# 96_Parallelism_Yamaichi_Rev1_2.net
KiCad netlist of a schematic drawn in EAGLE
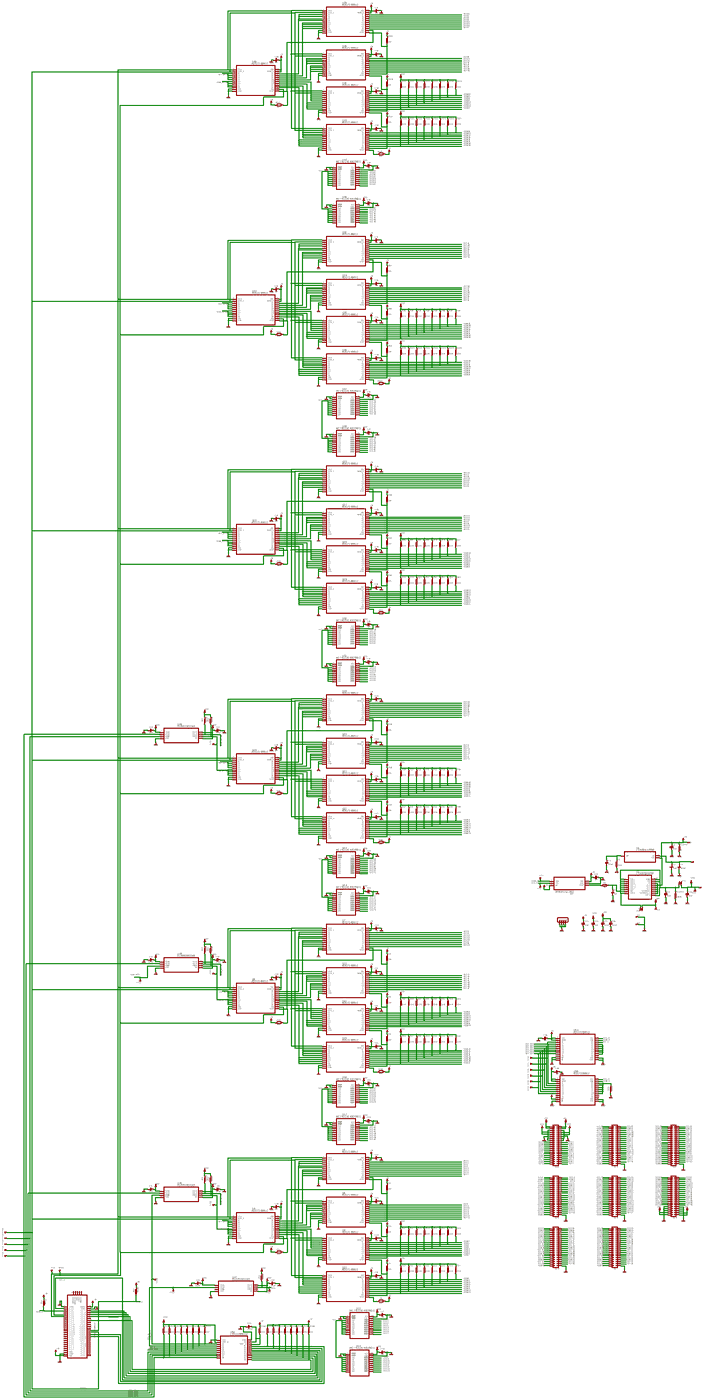
[diagram p0: schematic, sheet 1, overview]
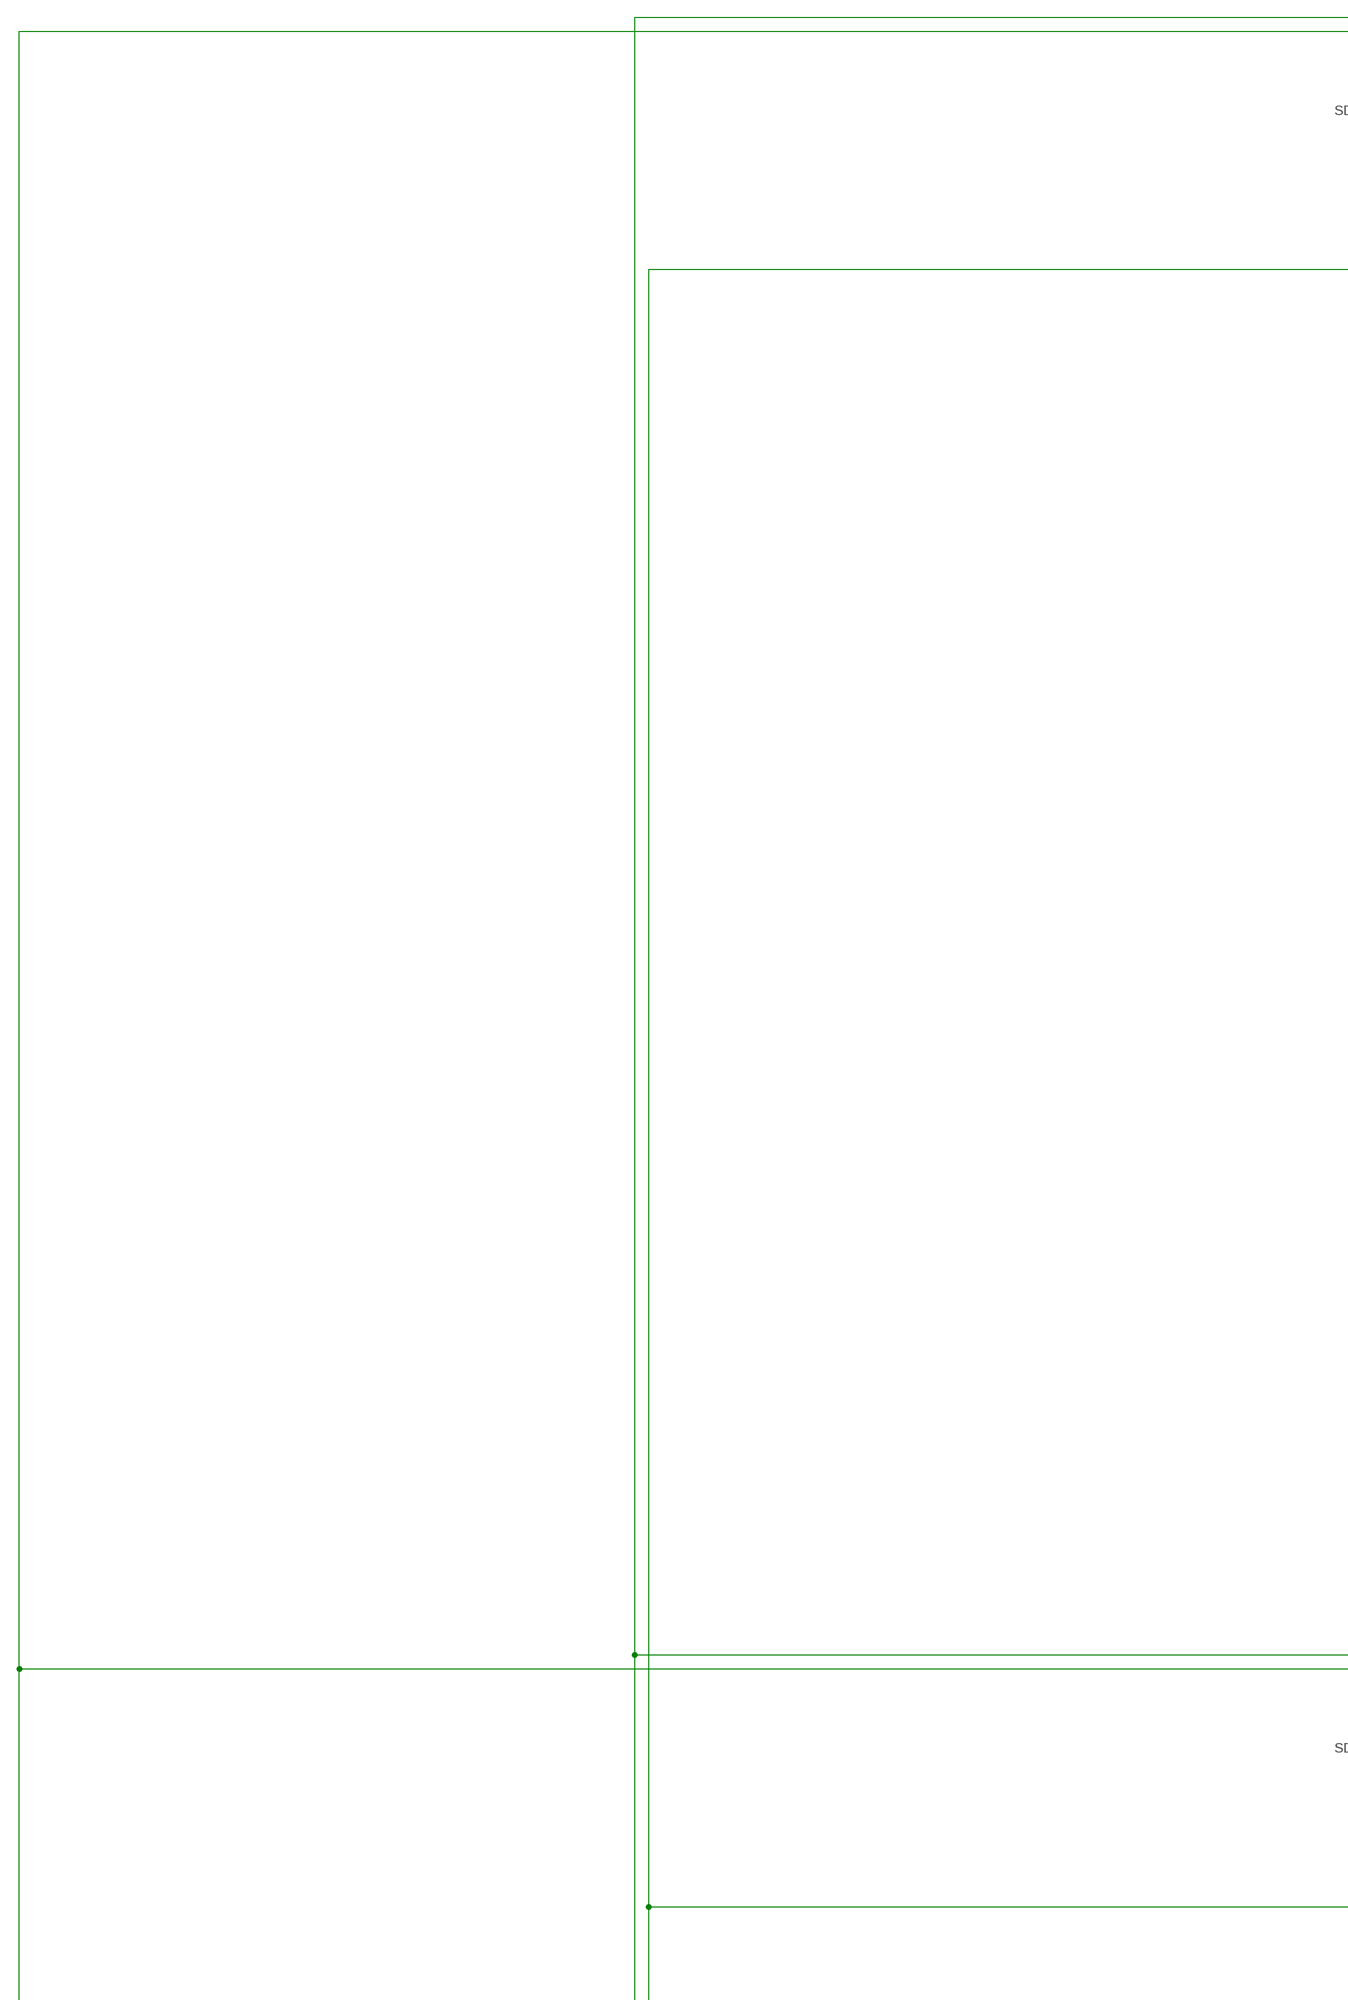
[diagram p1: schematic, sheet 1, part 1 of 8]
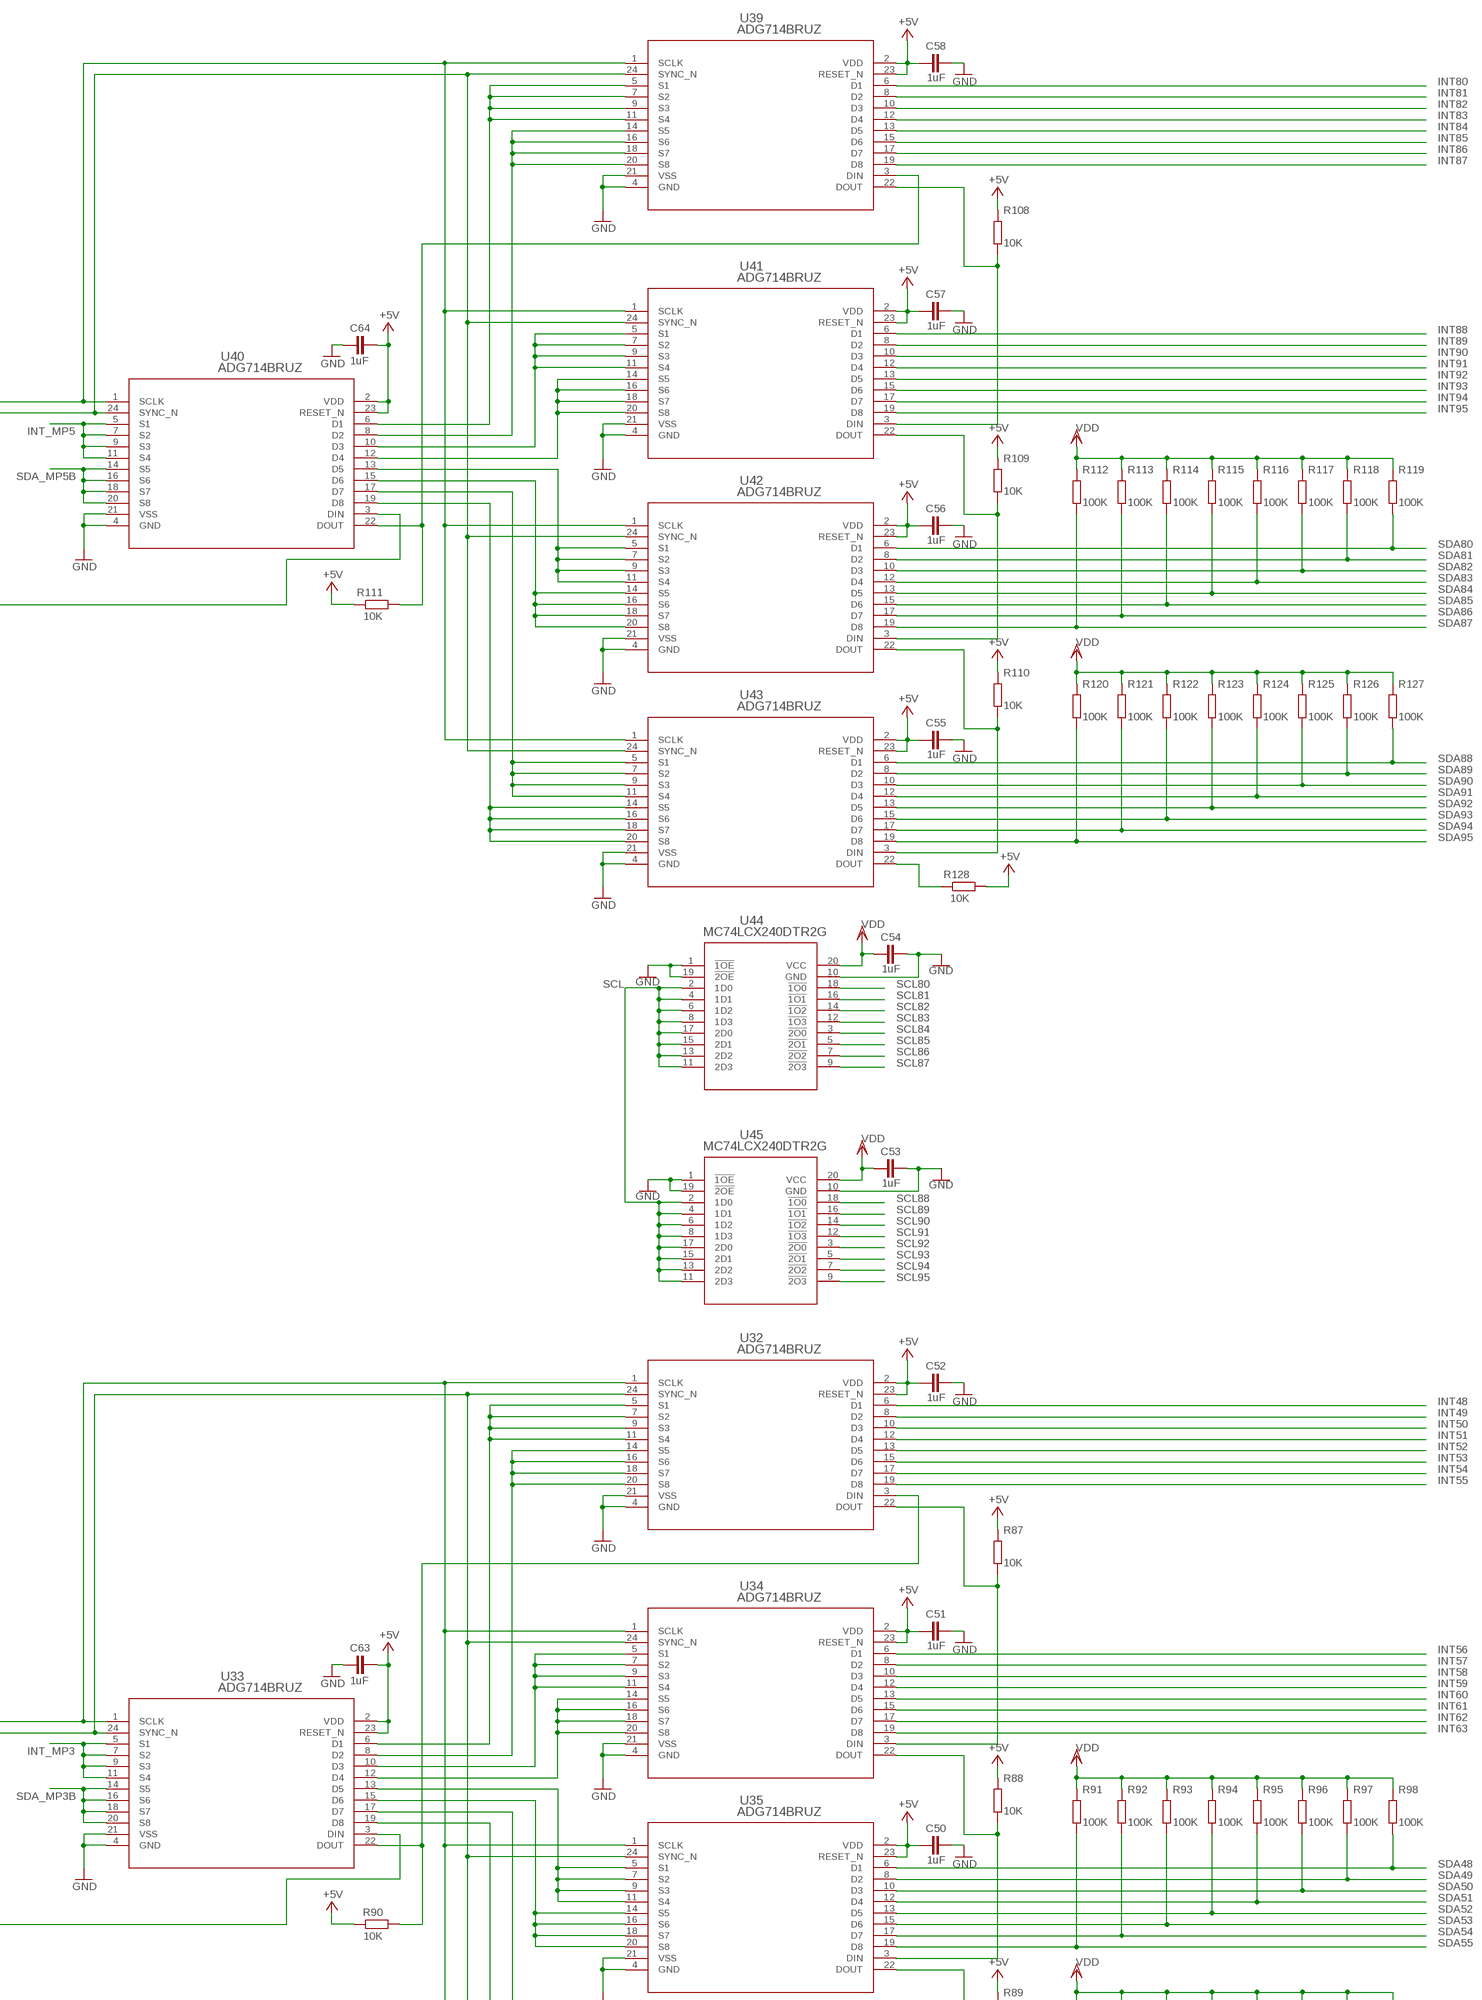
[diagram p2: schematic, sheet 1, part 2 of 8]
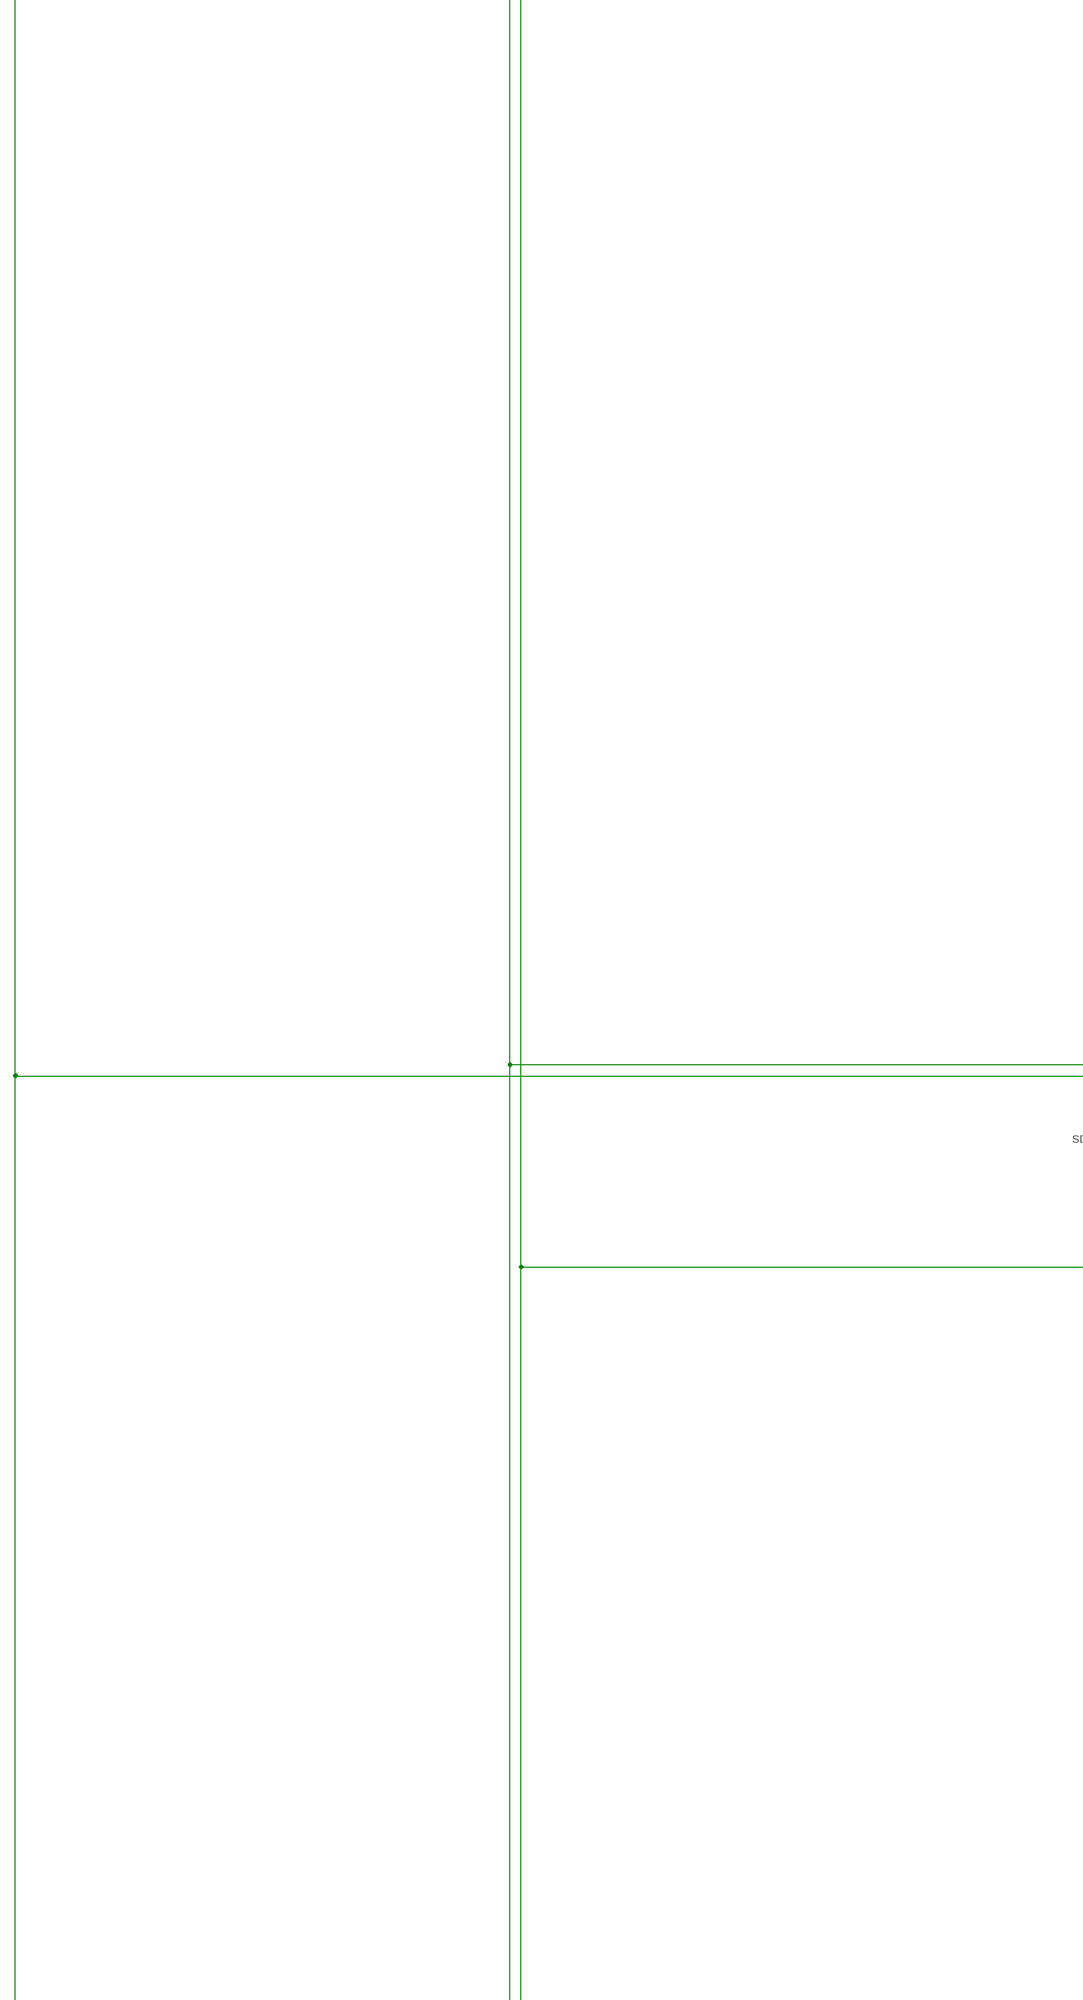
[diagram p3: schematic, sheet 1, part 3 of 8]
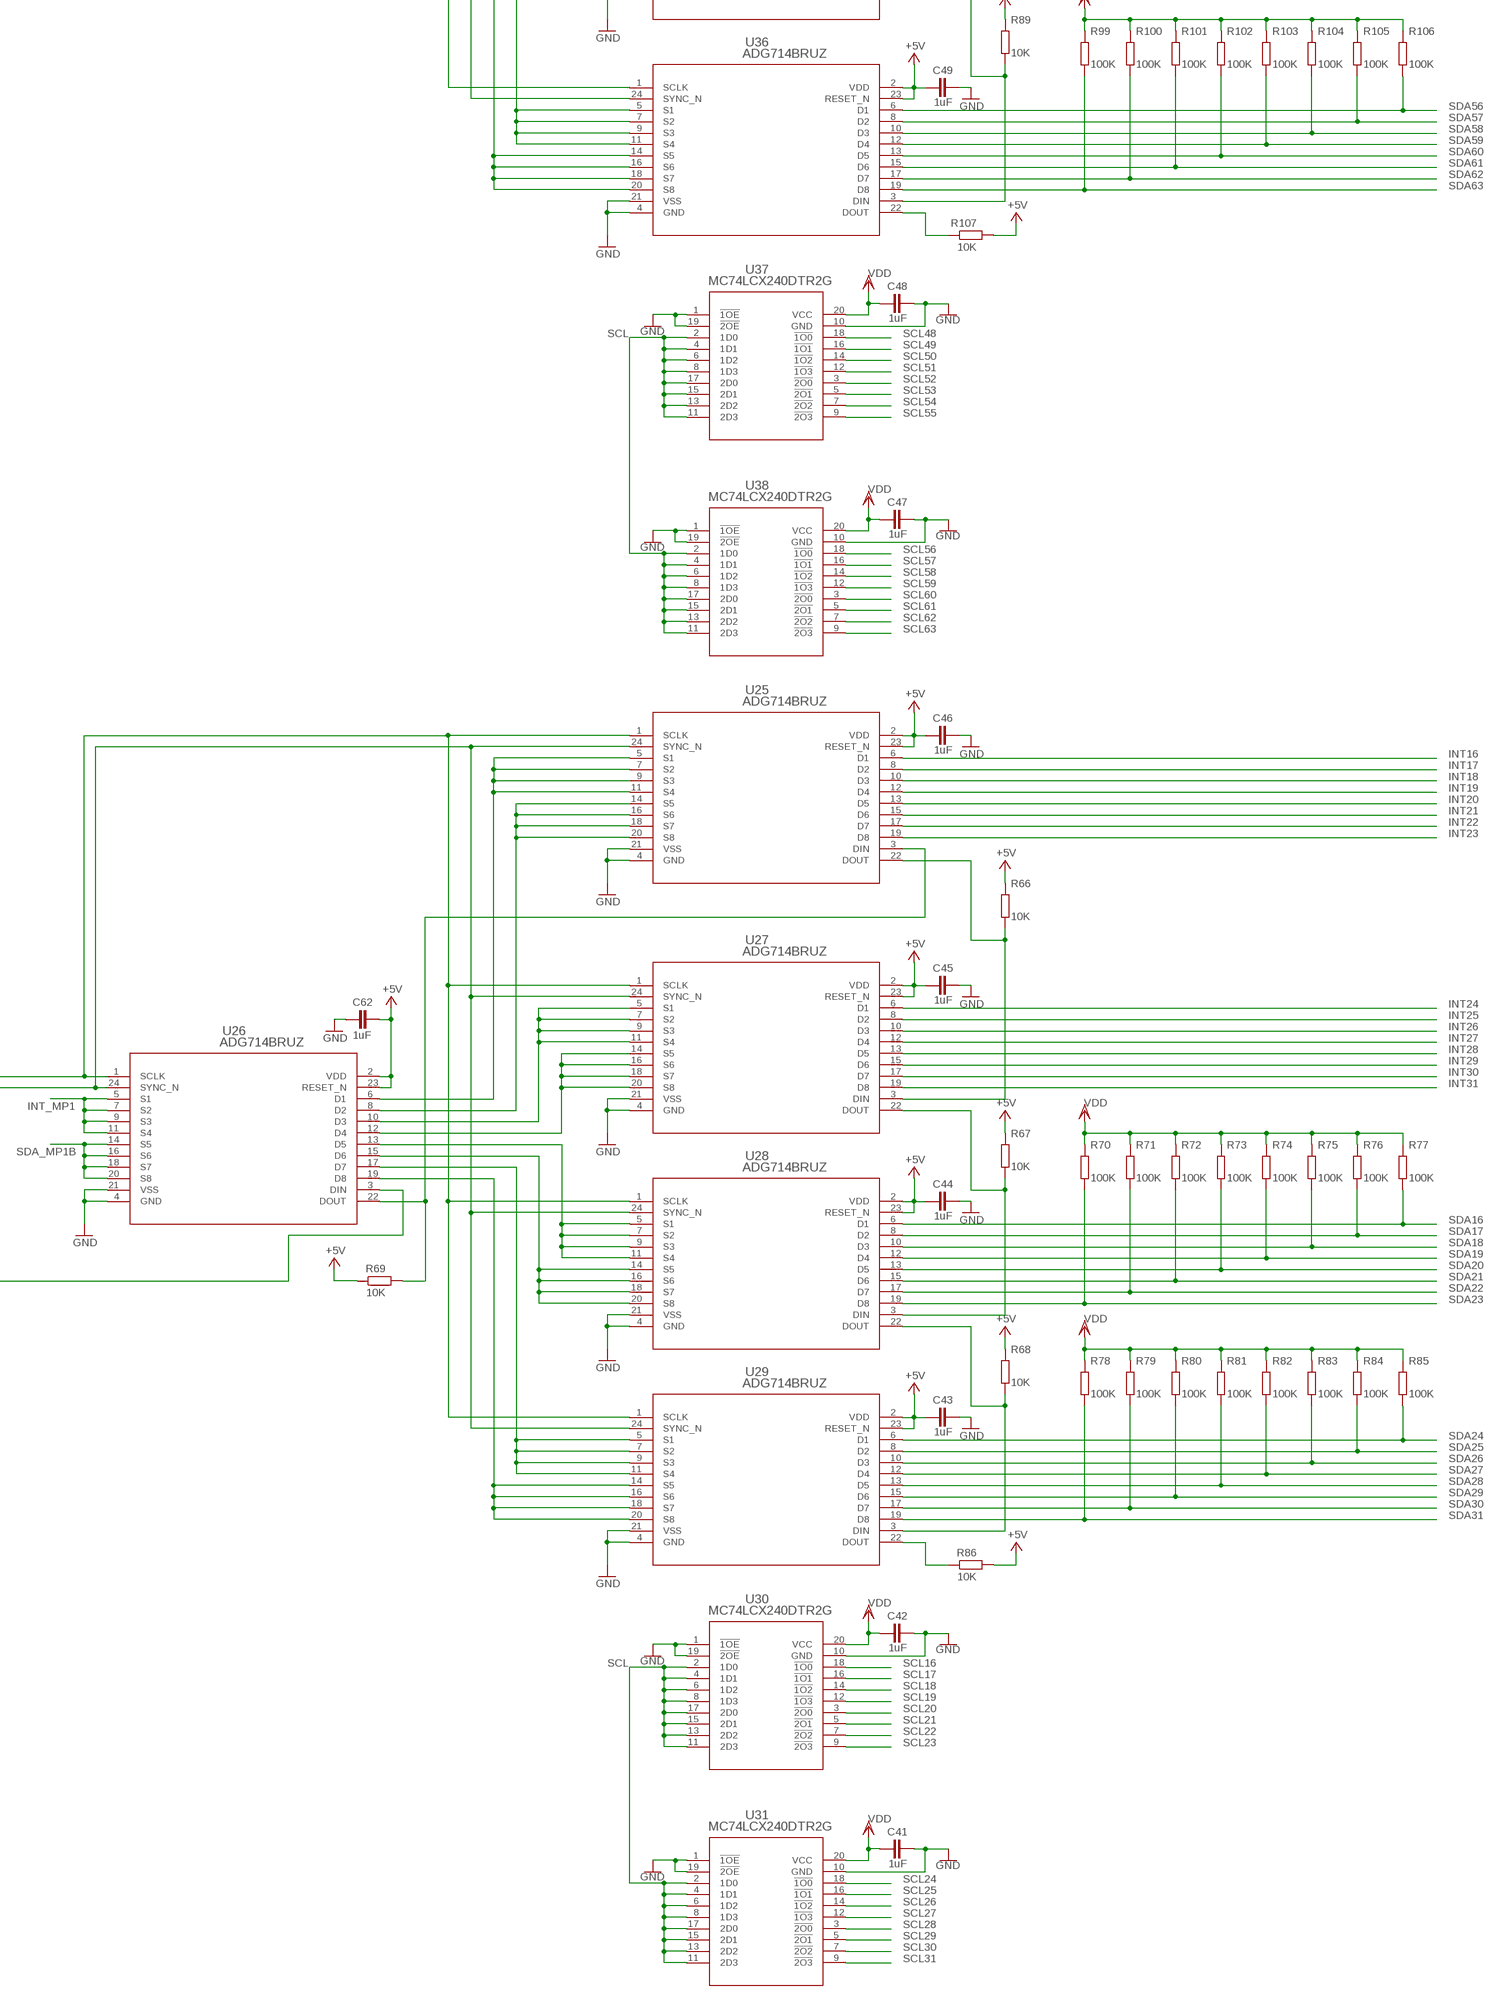
[diagram p4: schematic, sheet 1, part 4 of 8]
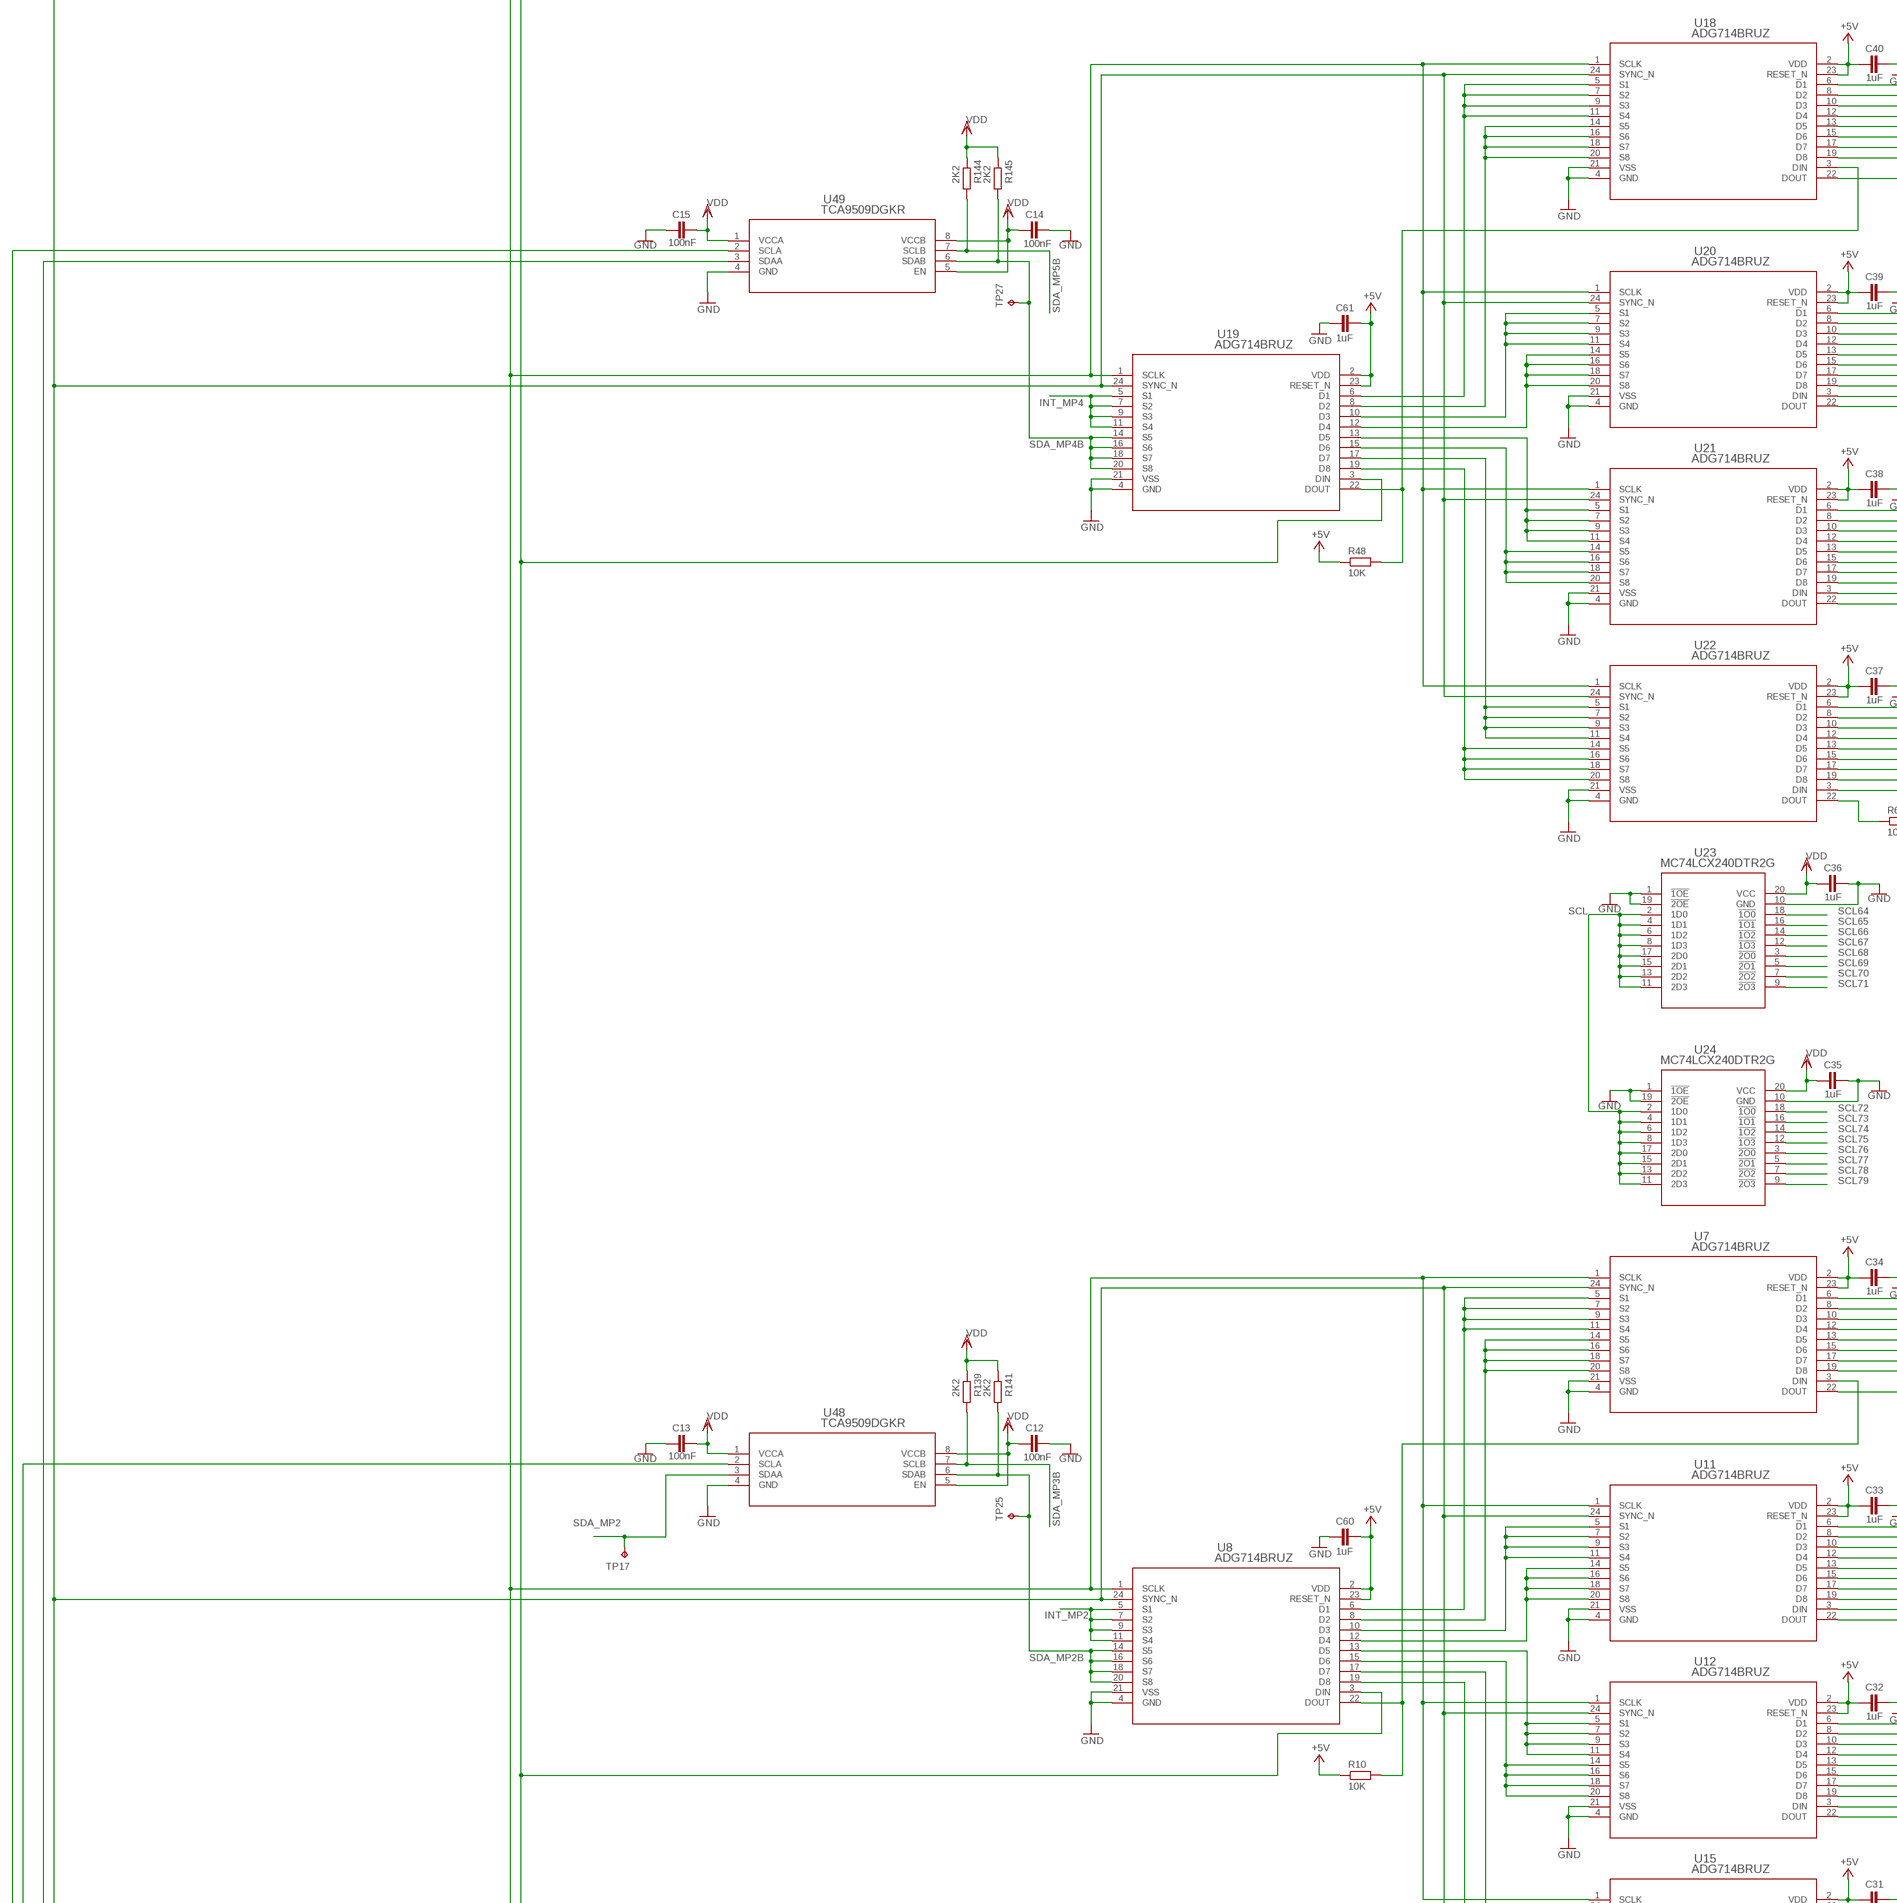
[diagram p5: schematic, sheet 1, part 5 of 8]
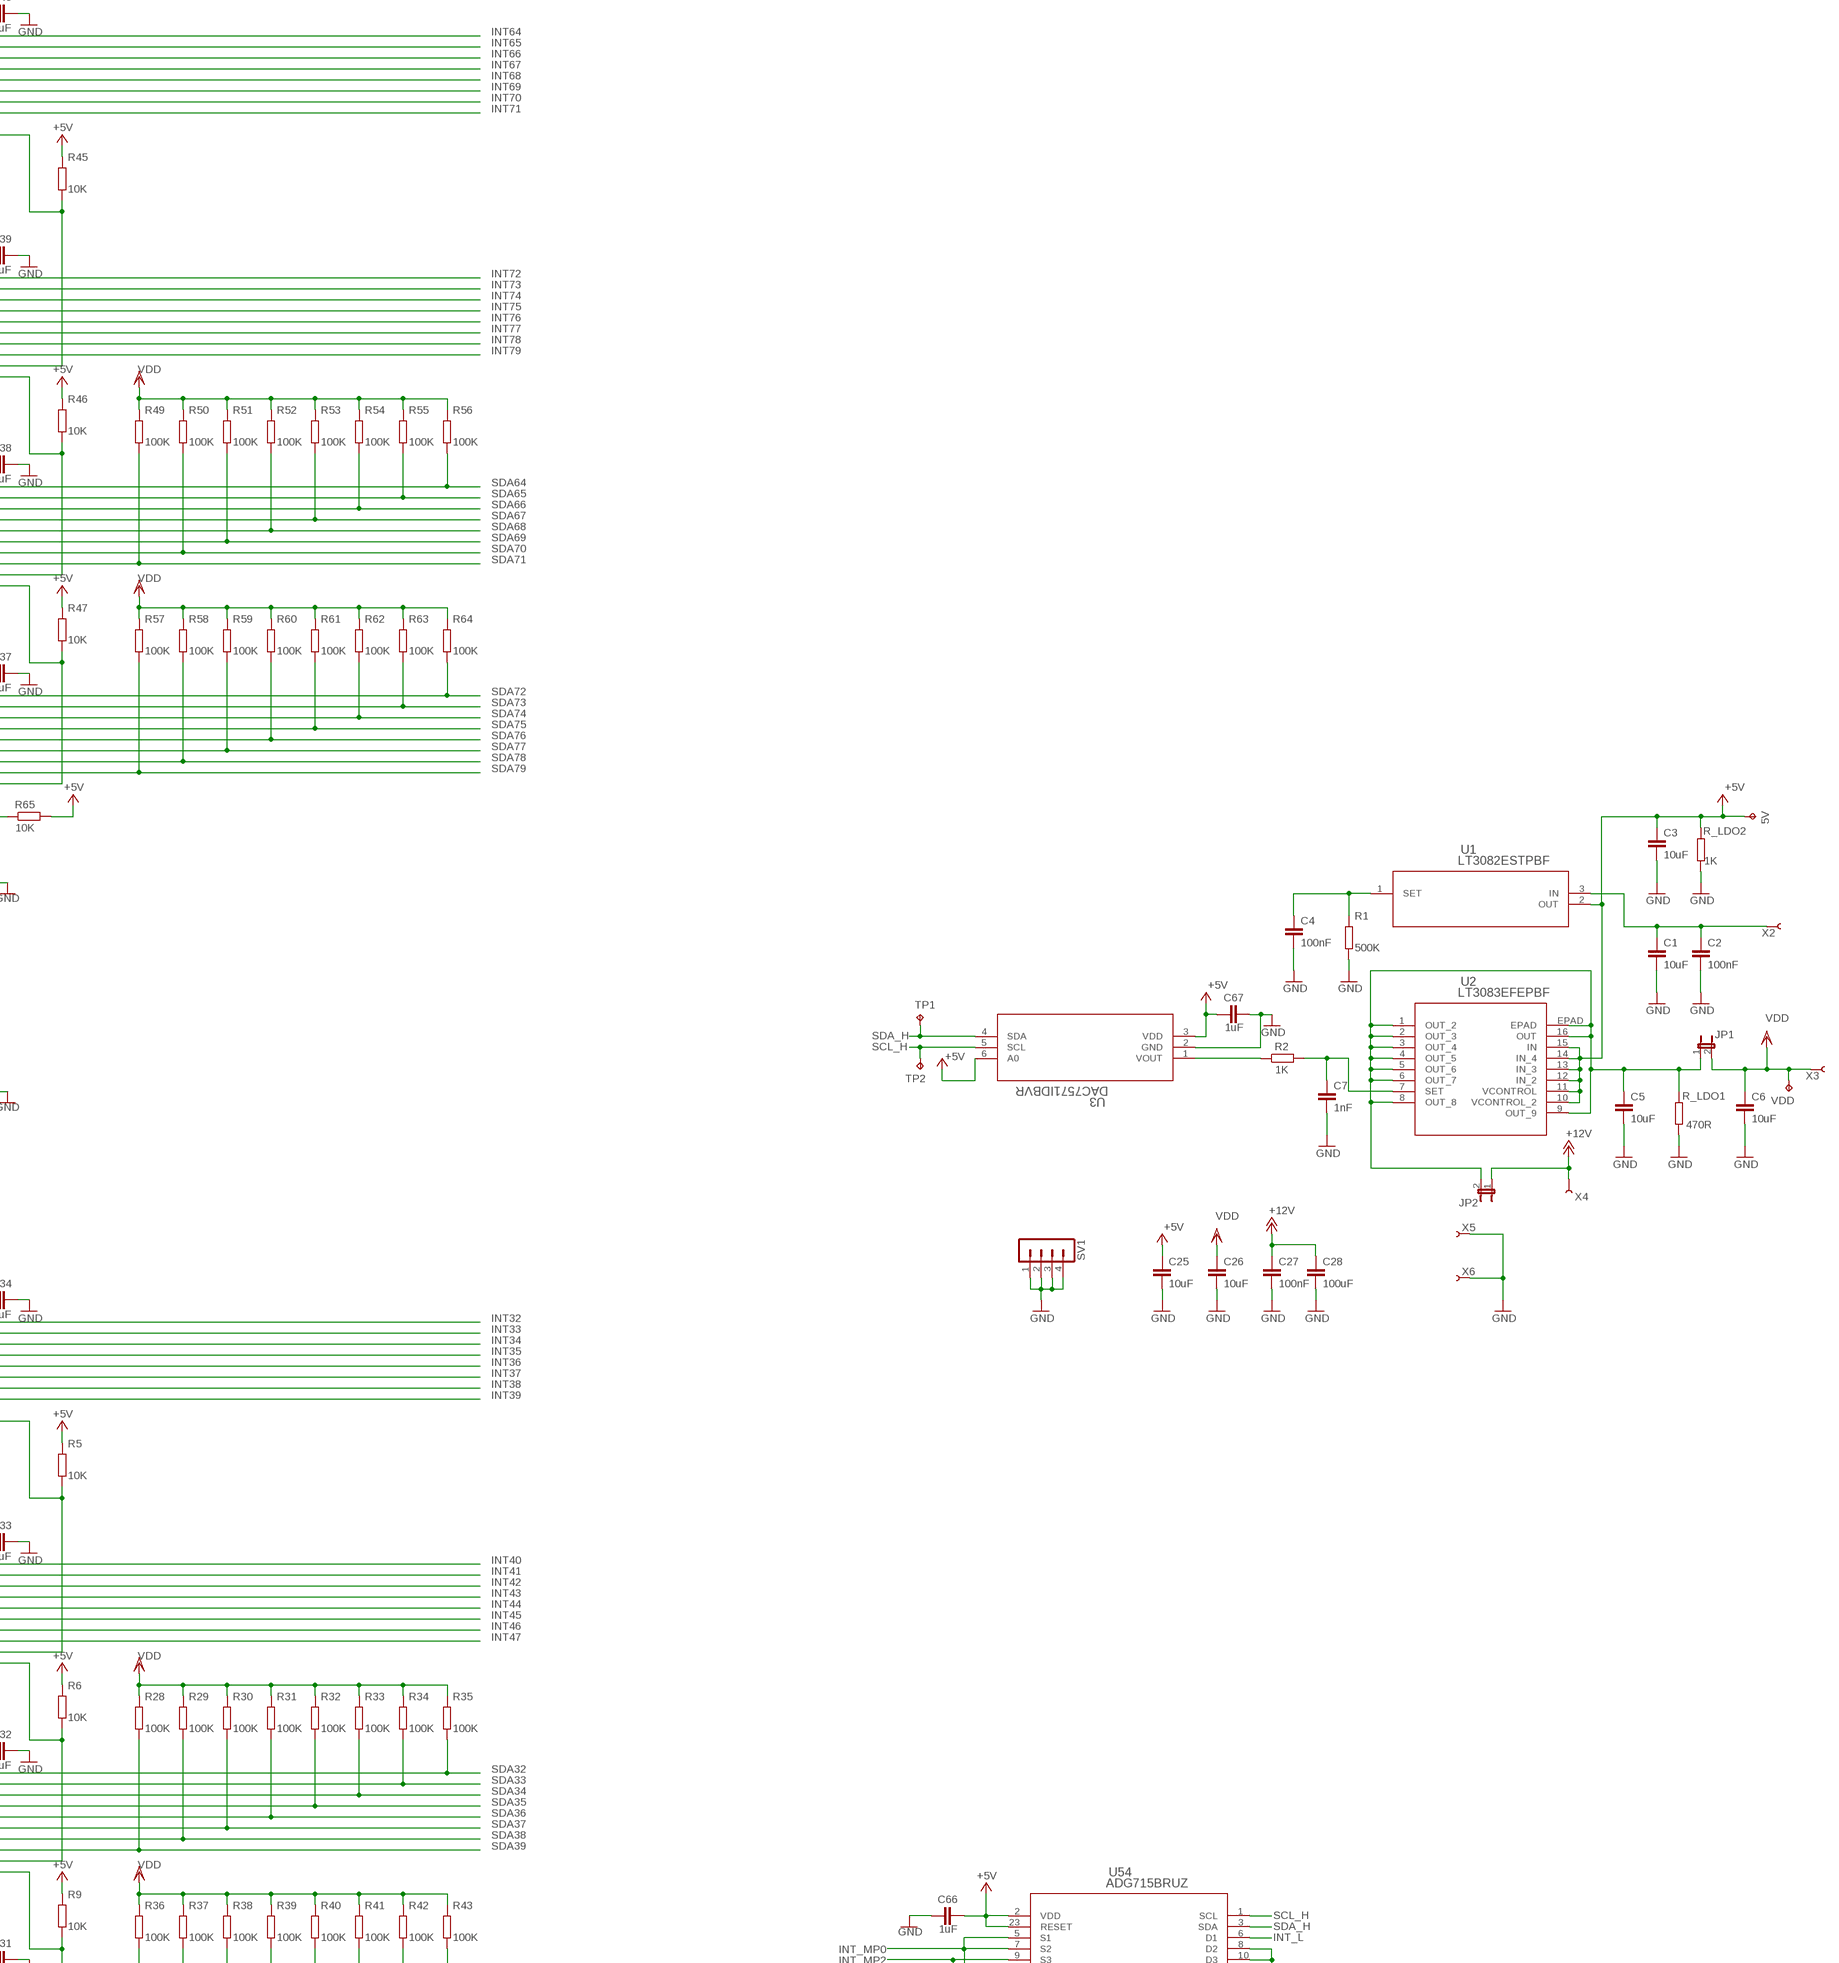
[diagram p6: schematic, sheet 1, part 6 of 8]
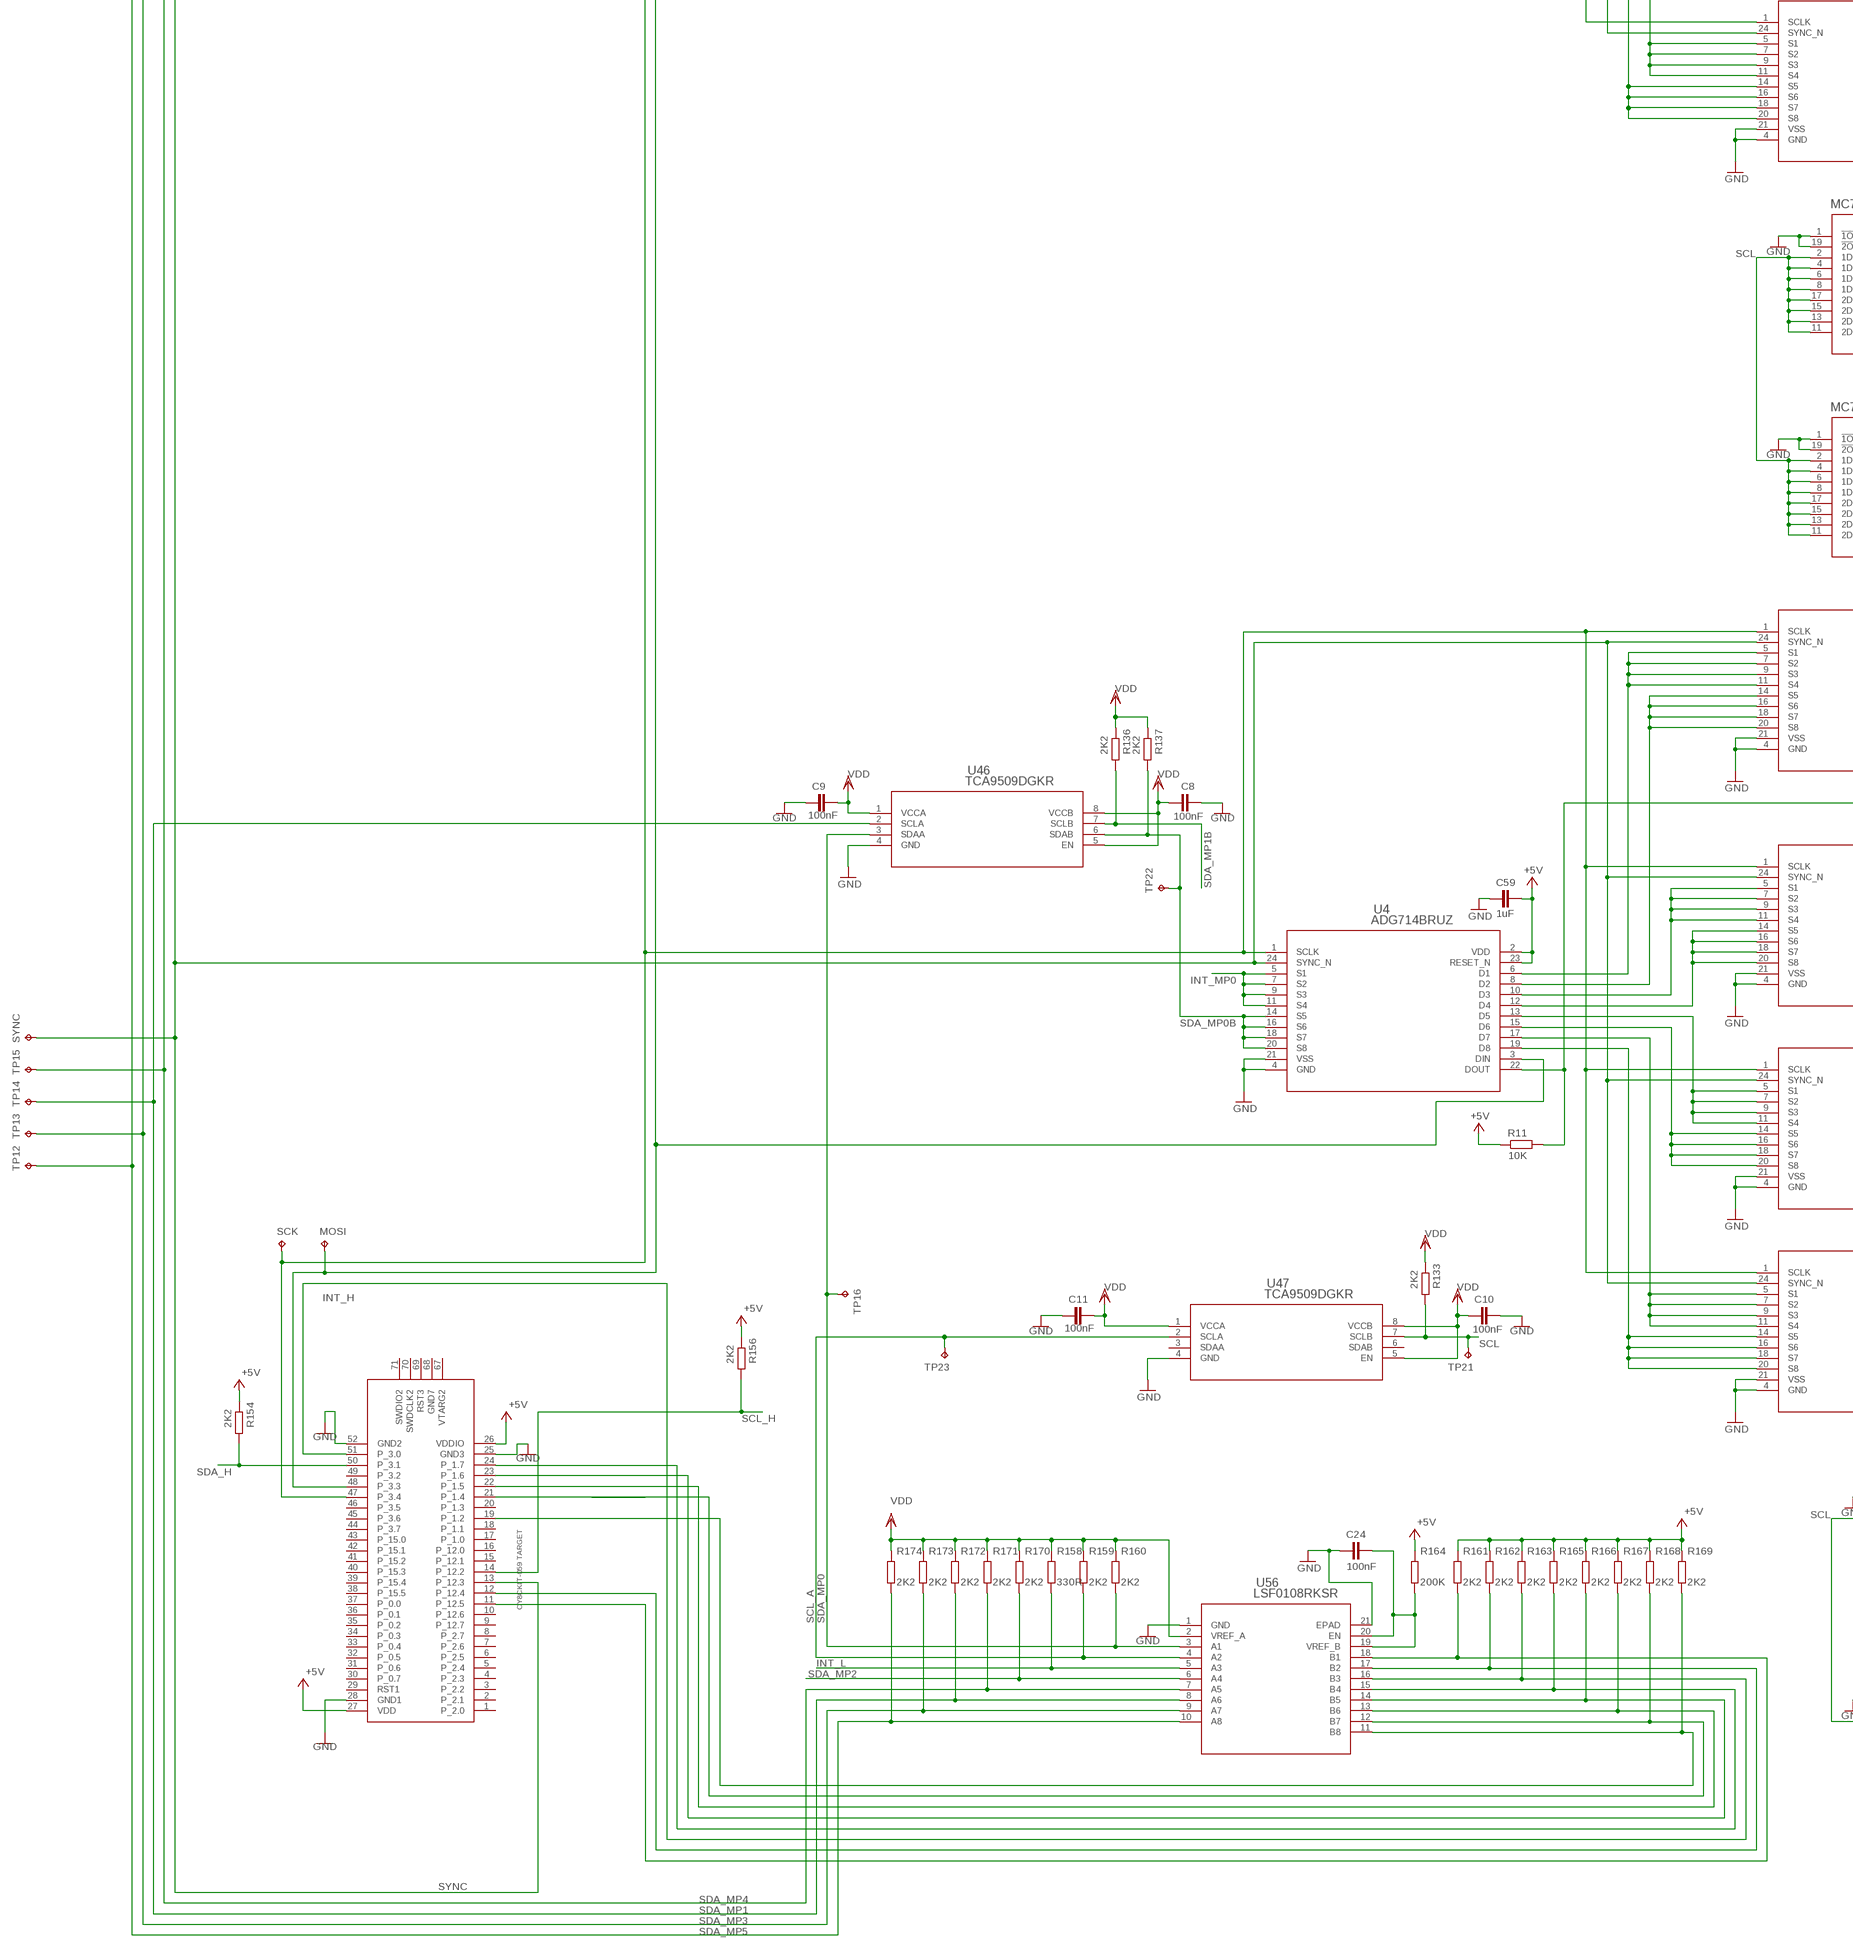
[diagram p7: schematic, sheet 1, part 7 of 8]
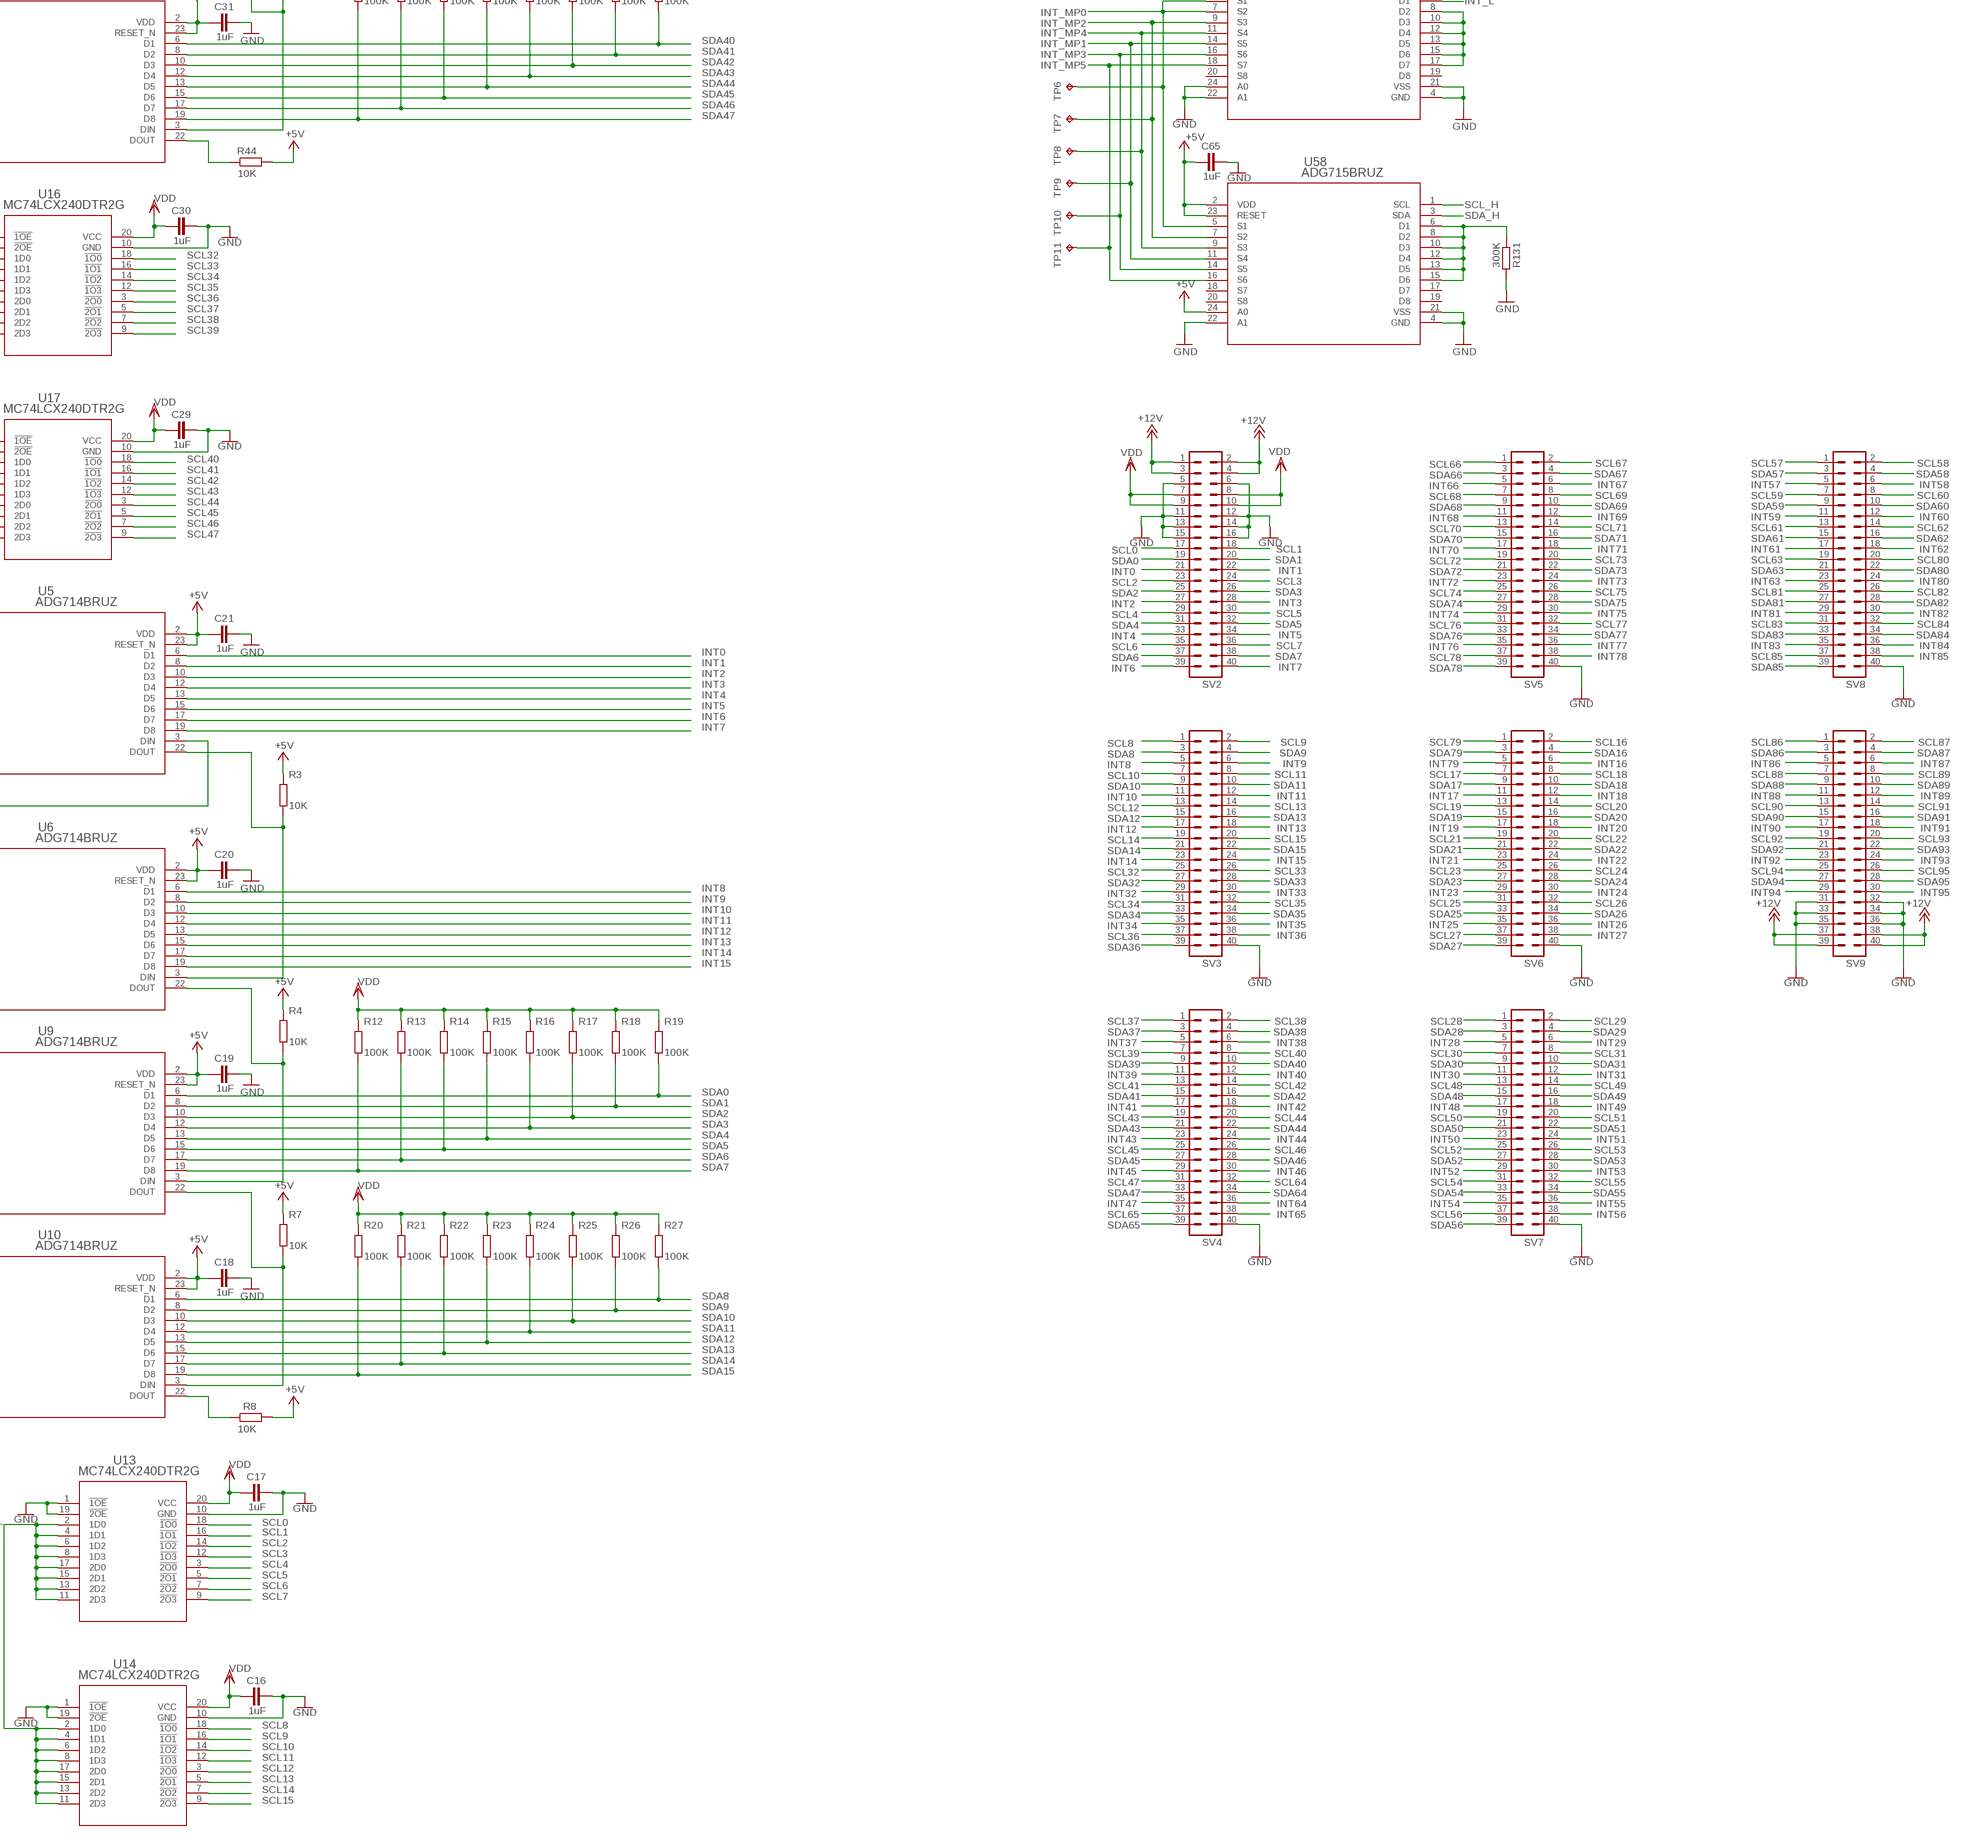
[diagram p8: schematic, sheet 1, part 8 of 8]

(export (version "E")
  (design (tool "Eeschema 10.0.6"))
  (components
    (comp (ref "5V")
      (value "TPB1,27")
      (footprint "eagle-import:B1,27")
      (libsource (lib "eagle-import") (part "TPB1,27"))
    )
    (comp (ref "C1")
      (value "10uF")
      (footprint "eagle-import:C0805")
      (libsource (lib "eagle-import") (part "C-EUC0805"))
    )
    (comp (ref "C2")
      (value "100nF")
      (footprint "eagle-import:C0805")
      (libsource (lib "eagle-import") (part "C-EUC0805"))
    )
    (comp (ref "C3")
      (value "10uF")
      (footprint "eagle-import:C0805")
      (libsource (lib "eagle-import") (part "C-EUC0805"))
    )
    (comp (ref "C4")
      (value "100nF")
      (footprint "eagle-import:C0805")
      (libsource (lib "eagle-import") (part "C-EUC0805"))
    )
    (comp (ref "C5")
      (value "10uF")
      (footprint "eagle-import:C0805")
      (libsource (lib "eagle-import") (part "C-EUC0805"))
    )
    (comp (ref "C6")
      (value "10uF")
      (footprint "eagle-import:C0805")
      (libsource (lib "eagle-import") (part "C-EUC0805"))
    )
    (comp (ref "C7")
      (value "1nF")
      (footprint "eagle-import:C0805")
      (libsource (lib "eagle-import") (part "C-EUC0805"))
    )
    (comp (ref "C8")
      (value "100nF")
      (footprint "eagle-import:C0805")
      (libsource (lib "eagle-import") (part "C-EUC0805"))
    )
    (comp (ref "C9")
      (value "100nF")
      (footprint "eagle-import:C0805")
      (libsource (lib "eagle-import") (part "C-EUC0805"))
    )
    (comp (ref "C10")
      (value "100nF")
      (footprint "eagle-import:C0805")
      (libsource (lib "eagle-import") (part "C-EUC0805"))
    )
    (comp (ref "C11")
      (value "100nF")
      (footprint "eagle-import:C0805")
      (libsource (lib "eagle-import") (part "C-EUC0805"))
    )
    (comp (ref "C12")
      (value "100nF")
      (footprint "eagle-import:C0805")
      (libsource (lib "eagle-import") (part "C-EUC0805"))
    )
    (comp (ref "C13")
      (value "100nF")
      (footprint "eagle-import:C0805")
      (libsource (lib "eagle-import") (part "C-EUC0805"))
    )
    (comp (ref "C14")
      (value "100nF")
      (footprint "eagle-import:C0805")
      (libsource (lib "eagle-import") (part "C-EUC0805"))
    )
    (comp (ref "C15")
      (value "100nF")
      (footprint "eagle-import:C0805")
      (libsource (lib "eagle-import") (part "C-EUC0805"))
    )
    (comp (ref "C16")
      (value "1uF")
      (footprint "eagle-import:C0805")
      (libsource (lib "eagle-import") (part "C-EUC0805"))
    )
    (comp (ref "C17")
      (value "1uF")
      (footprint "eagle-import:C0805")
      (libsource (lib "eagle-import") (part "C-EUC0805"))
    )
    (comp (ref "C18")
      (value "1uF")
      (footprint "eagle-import:C0805")
      (libsource (lib "eagle-import") (part "C-EUC0805"))
    )
    (comp (ref "C19")
      (value "1uF")
      (footprint "eagle-import:C0805")
      (libsource (lib "eagle-import") (part "C-EUC0805"))
    )
    (comp (ref "C20")
      (value "1uF")
      (footprint "eagle-import:C0805")
      (libsource (lib "eagle-import") (part "C-EUC0805"))
    )
    (comp (ref "C21")
      (value "1uF")
      (footprint "eagle-import:C0805")
      (libsource (lib "eagle-import") (part "C-EUC0805"))
    )
    (comp (ref "C24")
      (value "100nF")
      (footprint "eagle-import:C0805")
      (libsource (lib "eagle-import") (part "C-EUC0805"))
    )
    (comp (ref "C25")
      (value "10uF")
      (footprint "eagle-import:C0805")
      (libsource (lib "eagle-import") (part "C-EUC0805"))
    )
    (comp (ref "C26")
      (value "10uF")
      (footprint "eagle-import:C0805")
      (libsource (lib "eagle-import") (part "C-EUC0805"))
    )
    (comp (ref "C27")
      (value "100nF")
      (footprint "eagle-import:C0805")
      (libsource (lib "eagle-import") (part "C-EUC0805"))
    )
    (comp (ref "C28")
      (value "100uF")
      (footprint "eagle-import:C1210")
      (libsource (lib "eagle-import") (part "C-EUC1210"))
    )
    (comp (ref "C29")
      (value "1uF")
      (footprint "eagle-import:C0805")
      (libsource (lib "eagle-import") (part "C-EUC0805"))
    )
    (comp (ref "C30")
      (value "1uF")
      (footprint "eagle-import:C0805")
      (libsource (lib "eagle-import") (part "C-EUC0805"))
    )
    (comp (ref "C31")
      (value "1uF")
      (footprint "eagle-import:C0805")
      (libsource (lib "eagle-import") (part "C-EUC0805"))
    )
    (comp (ref "C32")
      (value "1uF")
      (footprint "eagle-import:C0805")
      (libsource (lib "eagle-import") (part "C-EUC0805"))
    )
    (comp (ref "C33")
      (value "1uF")
      (footprint "eagle-import:C0805")
      (libsource (lib "eagle-import") (part "C-EUC0805"))
    )
    (comp (ref "C34")
      (value "1uF")
      (footprint "eagle-import:C0805")
      (libsource (lib "eagle-import") (part "C-EUC0805"))
    )
    (comp (ref "C35")
      (value "1uF")
      (footprint "eagle-import:C0805")
      (libsource (lib "eagle-import") (part "C-EUC0805"))
    )
    (comp (ref "C36")
      (value "1uF")
      (footprint "eagle-import:C0805")
      (libsource (lib "eagle-import") (part "C-EUC0805"))
    )
    (comp (ref "C37")
      (value "1uF")
      (footprint "eagle-import:C0805")
      (libsource (lib "eagle-import") (part "C-EUC0805"))
    )
    (comp (ref "C38")
      (value "1uF")
      (footprint "eagle-import:C0805")
      (libsource (lib "eagle-import") (part "C-EUC0805"))
    )
    (comp (ref "C39")
      (value "1uF")
      (footprint "eagle-import:C0805")
      (libsource (lib "eagle-import") (part "C-EUC0805"))
    )
    (comp (ref "C40")
      (value "1uF")
      (footprint "eagle-import:C0805")
      (libsource (lib "eagle-import") (part "C-EUC0805"))
    )
    (comp (ref "C41")
      (value "1uF")
      (footprint "eagle-import:C0805")
      (libsource (lib "eagle-import") (part "C-EUC0805"))
    )
    (comp (ref "C42")
      (value "1uF")
      (footprint "eagle-import:C0805")
      (libsource (lib "eagle-import") (part "C-EUC0805"))
    )
    (comp (ref "C43")
      (value "1uF")
      (footprint "eagle-import:C0805")
      (libsource (lib "eagle-import") (part "C-EUC0805"))
    )
    (comp (ref "C44")
      (value "1uF")
      (footprint "eagle-import:C0805")
      (libsource (lib "eagle-import") (part "C-EUC0805"))
    )
    (comp (ref "C45")
      (value "1uF")
      (footprint "eagle-import:C0805")
      (libsource (lib "eagle-import") (part "C-EUC0805"))
    )
    (comp (ref "C46")
      (value "1uF")
      (footprint "eagle-import:C0805")
      (libsource (lib "eagle-import") (part "C-EUC0805"))
    )
    (comp (ref "C47")
      (value "1uF")
      (footprint "eagle-import:C0805")
      (libsource (lib "eagle-import") (part "C-EUC0805"))
    )
    (comp (ref "C48")
      (value "1uF")
      (footprint "eagle-import:C0805")
      (libsource (lib "eagle-import") (part "C-EUC0805"))
    )
    (comp (ref "C49")
      (value "1uF")
      (footprint "eagle-import:C0805")
      (libsource (lib "eagle-import") (part "C-EUC0805"))
    )
    (comp (ref "C50")
      (value "1uF")
      (footprint "eagle-import:C0805")
      (libsource (lib "eagle-import") (part "C-EUC0805"))
    )
    (comp (ref "C51")
      (value "1uF")
      (footprint "eagle-import:C0805")
      (libsource (lib "eagle-import") (part "C-EUC0805"))
    )
    (comp (ref "C52")
      (value "1uF")
      (footprint "eagle-import:C0805")
      (libsource (lib "eagle-import") (part "C-EUC0805"))
    )
    (comp (ref "C53")
      (value "1uF")
      (footprint "eagle-import:C0805")
      (libsource (lib "eagle-import") (part "C-EUC0805"))
    )
    (comp (ref "C54")
      (value "1uF")
      (footprint "eagle-import:C0805")
      (libsource (lib "eagle-import") (part "C-EUC0805"))
    )
    (comp (ref "C55")
      (value "1uF")
      (footprint "eagle-import:C0805")
      (libsource (lib "eagle-import") (part "C-EUC0805"))
    )
    (comp (ref "C56")
      (value "1uF")
      (footprint "eagle-import:C0805")
      (libsource (lib "eagle-import") (part "C-EUC0805"))
    )
    (comp (ref "C57")
      (value "1uF")
      (footprint "eagle-import:C0805")
      (libsource (lib "eagle-import") (part "C-EUC0805"))
    )
    (comp (ref "C58")
      (value "1uF")
      (footprint "eagle-import:C0805")
      (libsource (lib "eagle-import") (part "C-EUC0805"))
    )
    (comp (ref "C59")
      (value "1uF")
      (footprint "eagle-import:C0805")
      (libsource (lib "eagle-import") (part "C-EUC0805"))
    )
    (comp (ref "C60")
      (value "1uF")
      (footprint "eagle-import:C0805")
      (libsource (lib "eagle-import") (part "C-EUC0805"))
    )
    (comp (ref "C61")
      (value "1uF")
      (footprint "eagle-import:C0805")
      (libsource (lib "eagle-import") (part "C-EUC0805"))
    )
    (comp (ref "C62")
      (value "1uF")
      (footprint "eagle-import:C0805")
      (libsource (lib "eagle-import") (part "C-EUC0805"))
    )
    (comp (ref "C63")
      (value "1uF")
      (footprint "eagle-import:C0805")
      (libsource (lib "eagle-import") (part "C-EUC0805"))
    )
    (comp (ref "C64")
      (value "1uF")
      (footprint "eagle-import:C0805")
      (libsource (lib "eagle-import") (part "C-EUC0805"))
    )
    (comp (ref "C65")
      (value "1uF")
      (footprint "eagle-import:C0805")
      (libsource (lib "eagle-import") (part "C-EUC0805"))
    )
    (comp (ref "C66")
      (value "1uF")
      (footprint "eagle-import:C0805")
      (libsource (lib "eagle-import") (part "C-EUC0805"))
    )
    (comp (ref "C67")
      (value "1uF")
      (footprint "eagle-import:C0805")
      (libsource (lib "eagle-import") (part "C-EUC0805"))
    )
    (comp (ref "JP1")
      (value "JP1E")
      (footprint "eagle-import:JP1")
      (libsource (lib "eagle-import") (part "JP1E"))
    )
    (comp (ref "JP2")
      (value "JP1E")
      (footprint "eagle-import:JP1")
      (libsource (lib "eagle-import") (part "JP1E"))
    )
    (comp (ref "MOSI")
      (value "TPB1,27")
      (footprint "eagle-import:B1,27")
      (libsource (lib "eagle-import") (part "TPB1,27"))
    )
    (comp (ref "R1")
      (value "500K")
      (footprint "eagle-import:R0805")
      (libsource (lib "eagle-import") (part "R-EU_R0805"))
    )
    (comp (ref "R2")
      (value "1K")
      (footprint "eagle-import:R0805")
      (libsource (lib "eagle-import") (part "R-EU_R0805"))
    )
    (comp (ref "R3")
      (value "10K")
      (footprint "eagle-import:R0805")
      (libsource (lib "eagle-import") (part "R-EU_R0805"))
    )
    (comp (ref "R4")
      (value "10K")
      (footprint "eagle-import:R0805")
      (libsource (lib "eagle-import") (part "R-EU_R0805"))
    )
    (comp (ref "R5")
      (value "10K")
      (footprint "eagle-import:R0805")
      (libsource (lib "eagle-import") (part "R-EU_R0805"))
    )
    (comp (ref "R6")
      (value "10K")
      (footprint "eagle-import:R0805")
      (libsource (lib "eagle-import") (part "R-EU_R0805"))
    )
    (comp (ref "R7")
      (value "10K")
      (footprint "eagle-import:R0805")
      (libsource (lib "eagle-import") (part "R-EU_R0805"))
    )
    (comp (ref "R8")
      (value "10K")
      (footprint "eagle-import:R0805")
      (libsource (lib "eagle-import") (part "R-EU_R0805"))
    )
    (comp (ref "R9")
      (value "10K")
      (footprint "eagle-import:R0805")
      (libsource (lib "eagle-import") (part "R-EU_R0805"))
    )
    (comp (ref "R10")
      (value "10K")
      (footprint "eagle-import:R0805")
      (libsource (lib "eagle-import") (part "R-EU_R0805"))
    )
    (comp (ref "R11")
      (value "10K")
      (footprint "eagle-import:R0805")
      (libsource (lib "eagle-import") (part "R-EU_R0805"))
    )
    (comp (ref "R12")
      (value "100K")
      (footprint "eagle-import:R0805")
      (libsource (lib "eagle-import") (part "R-EU_R0805"))
    )
    (comp (ref "R13")
      (value "100K")
      (footprint "eagle-import:R0805")
      (libsource (lib "eagle-import") (part "R-EU_R0805"))
    )
    (comp (ref "R14")
      (value "100K")
      (footprint "eagle-import:R0805")
      (libsource (lib "eagle-import") (part "R-EU_R0805"))
    )
    (comp (ref "R15")
      (value "100K")
      (footprint "eagle-import:R0805")
      (libsource (lib "eagle-import") (part "R-EU_R0805"))
    )
    (comp (ref "R16")
      (value "100K")
      (footprint "eagle-import:R0805")
      (libsource (lib "eagle-import") (part "R-EU_R0805"))
    )
    (comp (ref "R17")
      (value "100K")
      (footprint "eagle-import:R0805")
      (libsource (lib "eagle-import") (part "R-EU_R0805"))
    )
    (comp (ref "R18")
      (value "100K")
      (footprint "eagle-import:R0805")
      (libsource (lib "eagle-import") (part "R-EU_R0805"))
    )
    (comp (ref "R19")
      (value "100K")
      (footprint "eagle-import:R0805")
      (libsource (lib "eagle-import") (part "R-EU_R0805"))
    )
    (comp (ref "R20")
      (value "100K")
      (footprint "eagle-import:R0805")
      (libsource (lib "eagle-import") (part "R-EU_R0805"))
    )
    (comp (ref "R21")
      (value "100K")
      (footprint "eagle-import:R0805")
      (libsource (lib "eagle-import") (part "R-EU_R0805"))
    )
    (comp (ref "R22")
      (value "100K")
      (footprint "eagle-import:R0805")
      (libsource (lib "eagle-import") (part "R-EU_R0805"))
    )
    (comp (ref "R23")
      (value "100K")
      (footprint "eagle-import:R0805")
      (libsource (lib "eagle-import") (part "R-EU_R0805"))
    )
    (comp (ref "R24")
      (value "100K")
      (footprint "eagle-import:R0805")
      (libsource (lib "eagle-import") (part "R-EU_R0805"))
    )
    (comp (ref "R25")
      (value "100K")
      (footprint "eagle-import:R0805")
      (libsource (lib "eagle-import") (part "R-EU_R0805"))
    )
    (comp (ref "R26")
      (value "100K")
      (footprint "eagle-import:R0805")
      (libsource (lib "eagle-import") (part "R-EU_R0805"))
    )
    (comp (ref "R27")
      (value "100K")
      (footprint "eagle-import:R0805")
      (libsource (lib "eagle-import") (part "R-EU_R0805"))
    )
    (comp (ref "R28")
      (value "100K")
      (footprint "eagle-import:R0805")
      (libsource (lib "eagle-import") (part "R-EU_R0805"))
    )
    (comp (ref "R29")
      (value "100K")
      (footprint "eagle-import:R0805")
      (libsource (lib "eagle-import") (part "R-EU_R0805"))
    )
    (comp (ref "R30")
      (value "100K")
      (footprint "eagle-import:R0805")
      (libsource (lib "eagle-import") (part "R-EU_R0805"))
    )
    (comp (ref "R31")
      (value "100K")
      (footprint "eagle-import:R0805")
      (libsource (lib "eagle-import") (part "R-EU_R0805"))
    )
    (comp (ref "R32")
      (value "100K")
      (footprint "eagle-import:R0805")
      (libsource (lib "eagle-import") (part "R-EU_R0805"))
    )
    (comp (ref "R33")
      (value "100K")
      (footprint "eagle-import:R0805")
      (libsource (lib "eagle-import") (part "R-EU_R0805"))
    )
    (comp (ref "R34")
      (value "100K")
      (footprint "eagle-import:R0805")
      (libsource (lib "eagle-import") (part "R-EU_R0805"))
    )
    (comp (ref "R35")
      (value "100K")
      (footprint "eagle-import:R0805")
      (libsource (lib "eagle-import") (part "R-EU_R0805"))
    )
    (comp (ref "R36")
      (value "100K")
      (footprint "eagle-import:R0805")
      (libsource (lib "eagle-import") (part "R-EU_R0805"))
    )
    (comp (ref "R37")
      (value "100K")
      (footprint "eagle-import:R0805")
      (libsource (lib "eagle-import") (part "R-EU_R0805"))
    )
    (comp (ref "R38")
      (value "100K")
      (footprint "eagle-import:R0805")
      (libsource (lib "eagle-import") (part "R-EU_R0805"))
    )
    (comp (ref "R39")
      (value "100K")
      (footprint "eagle-import:R0805")
      (libsource (lib "eagle-import") (part "R-EU_R0805"))
    )
    (comp (ref "R40")
      (value "100K")
      (footprint "eagle-import:R0805")
      (libsource (lib "eagle-import") (part "R-EU_R0805"))
    )
    (comp (ref "R41")
      (value "100K")
      (footprint "eagle-import:R0805")
      (libsource (lib "eagle-import") (part "R-EU_R0805"))
    )
    (comp (ref "R42")
      (value "100K")
      (footprint "eagle-import:R0805")
      (libsource (lib "eagle-import") (part "R-EU_R0805"))
    )
    (comp (ref "R43")
      (value "100K")
      (footprint "eagle-import:R0805")
      (libsource (lib "eagle-import") (part "R-EU_R0805"))
    )
    (comp (ref "R44")
      (value "10K")
      (footprint "eagle-import:R0805")
      (libsource (lib "eagle-import") (part "R-EU_R0805"))
    )
    (comp (ref "R45")
      (value "10K")
      (footprint "eagle-import:R0805")
      (libsource (lib "eagle-import") (part "R-EU_R0805"))
    )
    (comp (ref "R46")
      (value "10K")
      (footprint "eagle-import:R0805")
      (libsource (lib "eagle-import") (part "R-EU_R0805"))
    )
    (comp (ref "R47")
      (value "10K")
      (footprint "eagle-import:R0805")
      (libsource (lib "eagle-import") (part "R-EU_R0805"))
    )
    (comp (ref "R48")
      (value "10K")
      (footprint "eagle-import:R0805")
      (libsource (lib "eagle-import") (part "R-EU_R0805"))
    )
    (comp (ref "R49")
      (value "100K")
      (footprint "eagle-import:R0805")
      (libsource (lib "eagle-import") (part "R-EU_R0805"))
    )
    (comp (ref "R50")
      (value "100K")
      (footprint "eagle-import:R0805")
      (libsource (lib "eagle-import") (part "R-EU_R0805"))
    )
    (comp (ref "R51")
      (value "100K")
      (footprint "eagle-import:R0805")
      (libsource (lib "eagle-import") (part "R-EU_R0805"))
    )
    (comp (ref "R52")
      (value "100K")
      (footprint "eagle-import:R0805")
      (libsource (lib "eagle-import") (part "R-EU_R0805"))
    )
    (comp (ref "R53")
      (value "100K")
      (footprint "eagle-import:R0805")
      (libsource (lib "eagle-import") (part "R-EU_R0805"))
    )
    (comp (ref "R54")
      (value "100K")
      (footprint "eagle-import:R0805")
      (libsource (lib "eagle-import") (part "R-EU_R0805"))
    )
    (comp (ref "R55")
      (value "100K")
      (footprint "eagle-import:R0805")
      (libsource (lib "eagle-import") (part "R-EU_R0805"))
    )
    (comp (ref "R56")
      (value "100K")
      (footprint "eagle-import:R0805")
      (libsource (lib "eagle-import") (part "R-EU_R0805"))
    )
    (comp (ref "R57")
      (value "100K")
      (footprint "eagle-import:R0805")
      (libsource (lib "eagle-import") (part "R-EU_R0805"))
    )
    (comp (ref "R58")
      (value "100K")
      (footprint "eagle-import:R0805")
      (libsource (lib "eagle-import") (part "R-EU_R0805"))
    )
    (comp (ref "R59")
      (value "100K")
      (footprint "eagle-import:R0805")
      (libsource (lib "eagle-import") (part "R-EU_R0805"))
    )
    (comp (ref "R60")
      (value "100K")
      (footprint "eagle-import:R0805")
      (libsource (lib "eagle-import") (part "R-EU_R0805"))
    )
    (comp (ref "R61")
      (value "100K")
      (footprint "eagle-import:R0805")
      (libsource (lib "eagle-import") (part "R-EU_R0805"))
    )
    (comp (ref "R62")
      (value "100K")
      (footprint "eagle-import:R0805")
      (libsource (lib "eagle-import") (part "R-EU_R0805"))
    )
    (comp (ref "R63")
      (value "100K")
      (footprint "eagle-import:R0805")
      (libsource (lib "eagle-import") (part "R-EU_R0805"))
    )
    (comp (ref "R64")
      (value "100K")
      (footprint "eagle-import:R0805")
      (libsource (lib "eagle-import") (part "R-EU_R0805"))
    )
    (comp (ref "R65")
      (value "10K")
      (footprint "eagle-import:R0805")
      (libsource (lib "eagle-import") (part "R-EU_R0805"))
    )
    (comp (ref "R66")
      (value "10K")
      (footprint "eagle-import:R0805")
      (libsource (lib "eagle-import") (part "R-EU_R0805"))
    )
    (comp (ref "R67")
      (value "10K")
      (footprint "eagle-import:R0805")
      (libsource (lib "eagle-import") (part "R-EU_R0805"))
    )
    (comp (ref "R68")
      (value "10K")
      (footprint "eagle-import:R0805")
      (libsource (lib "eagle-import") (part "R-EU_R0805"))
    )
    (comp (ref "R69")
      (value "10K")
      (footprint "eagle-import:R0805")
      (libsource (lib "eagle-import") (part "R-EU_R0805"))
    )
    (comp (ref "R70")
      (value "100K")
      (footprint "eagle-import:R0805")
      (libsource (lib "eagle-import") (part "R-EU_R0805"))
    )
    (comp (ref "R71")
      (value "100K")
      (footprint "eagle-import:R0805")
      (libsource (lib "eagle-import") (part "R-EU_R0805"))
    )
    (comp (ref "R72")
      (value "100K")
      (footprint "eagle-import:R0805")
      (libsource (lib "eagle-import") (part "R-EU_R0805"))
    )
    (comp (ref "R73")
      (value "100K")
      (footprint "eagle-import:R0805")
      (libsource (lib "eagle-import") (part "R-EU_R0805"))
    )
    (comp (ref "R74")
      (value "100K")
      (footprint "eagle-import:R0805")
      (libsource (lib "eagle-import") (part "R-EU_R0805"))
    )
    (comp (ref "R75")
      (value "100K")
      (footprint "eagle-import:R0805")
      (libsource (lib "eagle-import") (part "R-EU_R0805"))
    )
    (comp (ref "R76")
      (value "100K")
      (footprint "eagle-import:R0805")
      (libsource (lib "eagle-import") (part "R-EU_R0805"))
    )
    (comp (ref "R77")
      (value "100K")
      (footprint "eagle-import:R0805")
      (libsource (lib "eagle-import") (part "R-EU_R0805"))
    )
    (comp (ref "R78")
      (value "100K")
      (footprint "eagle-import:R0805")
      (libsource (lib "eagle-import") (part "R-EU_R0805"))
    )
    (comp (ref "R79")
      (value "100K")
      (footprint "eagle-import:R0805")
      (libsource (lib "eagle-import") (part "R-EU_R0805"))
    )
    (comp (ref "R80")
      (value "100K")
      (footprint "eagle-import:R0805")
      (libsource (lib "eagle-import") (part "R-EU_R0805"))
    )
    (comp (ref "R81")
      (value "100K")
      (footprint "eagle-import:R0805")
      (libsource (lib "eagle-import") (part "R-EU_R0805"))
    )
    (comp (ref "R82")
      (value "100K")
      (footprint "eagle-import:R0805")
      (libsource (lib "eagle-import") (part "R-EU_R0805"))
    )
    (comp (ref "R83")
      (value "100K")
      (footprint "eagle-import:R0805")
      (libsource (lib "eagle-import") (part "R-EU_R0805"))
    )
    (comp (ref "R84")
      (value "100K")
      (footprint "eagle-import:R0805")
      (libsource (lib "eagle-import") (part "R-EU_R0805"))
    )
    (comp (ref "R85")
      (value "100K")
      (footprint "eagle-import:R0805")
      (libsource (lib "eagle-import") (part "R-EU_R0805"))
    )
    (comp (ref "R86")
      (value "10K")
      (footprint "eagle-import:R0805")
      (libsource (lib "eagle-import") (part "R-EU_R0805"))
    )
    (comp (ref "R87")
      (value "10K")
      (footprint "eagle-import:R0805")
      (libsource (lib "eagle-import") (part "R-EU_R0805"))
    )
    (comp (ref "R88")
      (value "10K")
      (footprint "eagle-import:R0805")
      (libsource (lib "eagle-import") (part "R-EU_R0805"))
    )
    (comp (ref "R89")
      (value "10K")
      (footprint "eagle-import:R0805")
      (libsource (lib "eagle-import") (part "R-EU_R0805"))
    )
    (comp (ref "R90")
      (value "10K")
      (footprint "eagle-import:R0805")
      (libsource (lib "eagle-import") (part "R-EU_R0805"))
    )
    (comp (ref "R91")
      (value "100K")
      (footprint "eagle-import:R0805")
      (libsource (lib "eagle-import") (part "R-EU_R0805"))
    )
    (comp (ref "R92")
      (value "100K")
      (footprint "eagle-import:R0805")
      (libsource (lib "eagle-import") (part "R-EU_R0805"))
    )
    (comp (ref "R93")
      (value "100K")
      (footprint "eagle-import:R0805")
      (libsource (lib "eagle-import") (part "R-EU_R0805"))
    )
    (comp (ref "R94")
      (value "100K")
      (footprint "eagle-import:R0805")
      (libsource (lib "eagle-import") (part "R-EU_R0805"))
    )
    (comp (ref "R95")
      (value "100K")
      (footprint "eagle-import:R0805")
      (libsource (lib "eagle-import") (part "R-EU_R0805"))
    )
    (comp (ref "R96")
      (value "100K")
      (footprint "eagle-import:R0805")
      (libsource (lib "eagle-import") (part "R-EU_R0805"))
    )
    (comp (ref "R97")
      (value "100K")
      (footprint "eagle-import:R0805")
      (libsource (lib "eagle-import") (part "R-EU_R0805"))
    )
    (comp (ref "R98")
      (value "100K")
      (footprint "eagle-import:R0805")
      (libsource (lib "eagle-import") (part "R-EU_R0805"))
    )
    (comp (ref "R99")
      (value "100K")
      (footprint "eagle-import:R0805")
      (libsource (lib "eagle-import") (part "R-EU_R0805"))
    )
    (comp (ref "R100")
      (value "100K")
      (footprint "eagle-import:R0805")
      (libsource (lib "eagle-import") (part "R-EU_R0805"))
    )
    (comp (ref "R101")
      (value "100K")
      (footprint "eagle-import:R0805")
      (libsource (lib "eagle-import") (part "R-EU_R0805"))
    )
    (comp (ref "R102")
      (value "100K")
      (footprint "eagle-import:R0805")
      (libsource (lib "eagle-import") (part "R-EU_R0805"))
    )
    (comp (ref "R103")
      (value "100K")
      (footprint "eagle-import:R0805")
      (libsource (lib "eagle-import") (part "R-EU_R0805"))
    )
    (comp (ref "R104")
      (value "100K")
      (footprint "eagle-import:R0805")
      (libsource (lib "eagle-import") (part "R-EU_R0805"))
    )
    (comp (ref "R105")
      (value "100K")
      (footprint "eagle-import:R0805")
      (libsource (lib "eagle-import") (part "R-EU_R0805"))
    )
    (comp (ref "R106")
      (value "100K")
      (footprint "eagle-import:R0805")
      (libsource (lib "eagle-import") (part "R-EU_R0805"))
    )
    (comp (ref "R107")
      (value "10K")
      (footprint "eagle-import:R0805")
      (libsource (lib "eagle-import") (part "R-EU_R0805"))
    )
    (comp (ref "R108")
      (value "10K")
      (footprint "eagle-import:R0805")
      (libsource (lib "eagle-import") (part "R-EU_R0805"))
    )
    (comp (ref "R109")
      (value "10K")
      (footprint "eagle-import:R0805")
      (libsource (lib "eagle-import") (part "R-EU_R0805"))
    )
    (comp (ref "R110")
      (value "10K")
      (footprint "eagle-import:R0805")
      (libsource (lib "eagle-import") (part "R-EU_R0805"))
    )
    (comp (ref "R111")
      (value "10K")
      (footprint "eagle-import:R0805")
      (libsource (lib "eagle-import") (part "R-EU_R0805"))
    )
    (comp (ref "R112")
      (value "100K")
      (footprint "eagle-import:R0805")
      (libsource (lib "eagle-import") (part "R-EU_R0805"))
    )
    (comp (ref "R113")
      (value "100K")
      (footprint "eagle-import:R0805")
      (libsource (lib "eagle-import") (part "R-EU_R0805"))
    )
    (comp (ref "R114")
      (value "100K")
      (footprint "eagle-import:R0805")
      (libsource (lib "eagle-import") (part "R-EU_R0805"))
    )
    (comp (ref "R115")
      (value "100K")
      (footprint "eagle-import:R0805")
      (libsource (lib "eagle-import") (part "R-EU_R0805"))
    )
    (comp (ref "R116")
      (value "100K")
      (footprint "eagle-import:R0805")
      (libsource (lib "eagle-import") (part "R-EU_R0805"))
    )
    (comp (ref "R117")
      (value "100K")
      (footprint "eagle-import:R0805")
      (libsource (lib "eagle-import") (part "R-EU_R0805"))
    )
    (comp (ref "R118")
      (value "100K")
      (footprint "eagle-import:R0805")
      (libsource (lib "eagle-import") (part "R-EU_R0805"))
    )
    (comp (ref "R119")
      (value "100K")
      (footprint "eagle-import:R0805")
      (libsource (lib "eagle-import") (part "R-EU_R0805"))
    )
    (comp (ref "R120")
      (value "100K")
      (footprint "eagle-import:R0805")
      (libsource (lib "eagle-import") (part "R-EU_R0805"))
    )
    (comp (ref "R121")
      (value "100K")
      (footprint "eagle-import:R0805")
      (libsource (lib "eagle-import") (part "R-EU_R0805"))
    )
    (comp (ref "R122")
      (value "100K")
      (footprint "eagle-import:R0805")
      (libsource (lib "eagle-import") (part "R-EU_R0805"))
    )
    (comp (ref "R123")
      (value "100K")
      (footprint "eagle-import:R0805")
      (libsource (lib "eagle-import") (part "R-EU_R0805"))
    )
    (comp (ref "R124")
      (value "100K")
      (footprint "eagle-import:R0805")
      (libsource (lib "eagle-import") (part "R-EU_R0805"))
    )
    (comp (ref "R125")
      (value "100K")
      (footprint "eagle-import:R0805")
      (libsource (lib "eagle-import") (part "R-EU_R0805"))
    )
    (comp (ref "R126")
      (value "100K")
      (footprint "eagle-import:R0805")
      (libsource (lib "eagle-import") (part "R-EU_R0805"))
    )
    (comp (ref "R127")
      (value "100K")
      (footprint "eagle-import:R0805")
      (libsource (lib "eagle-import") (part "R-EU_R0805"))
    )
    (comp (ref "R128")
      (value "10K")
      (footprint "eagle-import:R0805")
      (libsource (lib "eagle-import") (part "R-EU_R0805"))
    )
    (comp (ref "R131")
      (value "300K")
      (footprint "eagle-import:R0805")
      (libsource (lib "eagle-import") (part "R-EU_R0805"))
    )
    (comp (ref "R133")
      (value "2K2")
      (footprint "eagle-import:R0805")
      (libsource (lib "eagle-import") (part "R-EU_R0805"))
    )
    (comp (ref "R136")
      (value "2K2")
      (footprint "eagle-import:R0805")
      (libsource (lib "eagle-import") (part "R-EU_R0805"))
    )
    (comp (ref "R137")
      (value "2K2")
      (footprint "eagle-import:R0805")
      (libsource (lib "eagle-import") (part "R-EU_R0805"))
    )
    (comp (ref "R139")
      (value "2K2")
      (footprint "eagle-import:R0805")
      (libsource (lib "eagle-import") (part "R-EU_R0805"))
    )
    (comp (ref "R141")
      (value "2K2")
      (footprint "eagle-import:R0805")
      (libsource (lib "eagle-import") (part "R-EU_R0805"))
    )
    (comp (ref "R144")
      (value "2K2")
      (footprint "eagle-import:R0805")
      (libsource (lib "eagle-import") (part "R-EU_R0805"))
    )
    (comp (ref "R145")
      (value "2K2")
      (footprint "eagle-import:R0805")
      (libsource (lib "eagle-import") (part "R-EU_R0805"))
    )
    (comp (ref "R154")
      (value "2K2")
      (footprint "eagle-import:R0805")
      (libsource (lib "eagle-import") (part "R-EU_R0805"))
    )
    (comp (ref "R156")
      (value "2K2")
      (footprint "eagle-import:R0805")
      (libsource (lib "eagle-import") (part "R-EU_R0805"))
    )
    (comp (ref "R158")
      (value "330R")
      (footprint "eagle-import:R0805")
      (libsource (lib "eagle-import") (part "R-EU_R0805"))
    )
    (comp (ref "R159")
      (value "2K2")
      (footprint "eagle-import:R0805")
      (libsource (lib "eagle-import") (part "R-EU_R0805"))
    )
    (comp (ref "R160")
      (value "2K2")
      (footprint "eagle-import:R0805")
      (libsource (lib "eagle-import") (part "R-EU_R0805"))
    )
    (comp (ref "R161")
      (value "2K2")
      (footprint "eagle-import:R0805")
      (libsource (lib "eagle-import") (part "R-EU_R0805"))
    )
    (comp (ref "R162")
      (value "2K2")
      (footprint "eagle-import:R0805")
      (libsource (lib "eagle-import") (part "R-EU_R0805"))
    )
    (comp (ref "R163")
      (value "2K2")
      (footprint "eagle-import:R0805")
      (libsource (lib "eagle-import") (part "R-EU_R0805"))
    )
    (comp (ref "R164")
      (value "200K")
      (footprint "eagle-import:R0805")
      (libsource (lib "eagle-import") (part "R-EU_R0805"))
    )
    (comp (ref "R165")
      (value "2K2")
      (footprint "eagle-import:R0805")
      (libsource (lib "eagle-import") (part "R-EU_R0805"))
    )
    (comp (ref "R166")
      (value "2K2")
      (footprint "eagle-import:R0805")
      (libsource (lib "eagle-import") (part "R-EU_R0805"))
    )
    (comp (ref "R167")
      (value "2K2")
      (footprint "eagle-import:R0805")
      (libsource (lib "eagle-import") (part "R-EU_R0805"))
    )
    (comp (ref "R168")
      (value "2K2")
      (footprint "eagle-import:R0805")
      (libsource (lib "eagle-import") (part "R-EU_R0805"))
    )
    (comp (ref "R169")
      (value "2K2")
      (footprint "eagle-import:R0805")
      (libsource (lib "eagle-import") (part "R-EU_R0805"))
    )
    (comp (ref "R170")
      (value "2K2")
      (footprint "eagle-import:R0805")
      (libsource (lib "eagle-import") (part "R-EU_R0805"))
    )
    (comp (ref "R171")
      (value "2K2")
      (footprint "eagle-import:R0805")
      (libsource (lib "eagle-import") (part "R-EU_R0805"))
    )
    (comp (ref "R172")
      (value "2K2")
      (footprint "eagle-import:R0805")
      (libsource (lib "eagle-import") (part "R-EU_R0805"))
    )
    (comp (ref "R173")
      (value "2K2")
      (footprint "eagle-import:R0805")
      (libsource (lib "eagle-import") (part "R-EU_R0805"))
    )
    (comp (ref "R174")
      (value "2K2")
      (footprint "eagle-import:R0805")
      (libsource (lib "eagle-import") (part "R-EU_R0805"))
    )
    (comp (ref "R_LDO1")
      (value "470R")
      (footprint "eagle-import:R0805")
      (libsource (lib "eagle-import") (part "R-EU_R0805"))
    )
    (comp (ref "R_LDO2")
      (value "1K")
      (footprint "eagle-import:R0805")
      (libsource (lib "eagle-import") (part "R-EU_R0805"))
    )
    (comp (ref "SCK")
      (value "TPB1,27")
      (footprint "eagle-import:B1,27")
      (libsource (lib "eagle-import") (part "TPB1,27"))
    )
    (comp (ref "SV1")
      (value "MA04-1")
      (footprint "eagle-import:MA04-1")
      (libsource (lib "eagle-import") (part "MA04-1"))
    )
    (comp (ref "SV2")
      (value "MA20-2")
      (footprint "eagle-import:MA20-2")
      (libsource (lib "eagle-import") (part "MA20-2"))
    )
    (comp (ref "SV3")
      (value "MA20-2")
      (footprint "eagle-import:MA20-2")
      (libsource (lib "eagle-import") (part "MA20-2"))
    )
    (comp (ref "SV4")
      (value "MA20-2")
      (footprint "eagle-import:MA20-2")
      (libsource (lib "eagle-import") (part "MA20-2"))
    )
    (comp (ref "SV5")
      (value "MA20-2")
      (footprint "eagle-import:MA20-2")
      (libsource (lib "eagle-import") (part "MA20-2"))
    )
    (comp (ref "SV6")
      (value "MA20-2")
      (footprint "eagle-import:MA20-2")
      (libsource (lib "eagle-import") (part "MA20-2"))
    )
    (comp (ref "SV7")
      (value "MA20-2")
      (footprint "eagle-import:MA20-2")
      (libsource (lib "eagle-import") (part "MA20-2"))
    )
    (comp (ref "SV8")
      (value "MA20-2")
      (footprint "eagle-import:MA20-2")
      (libsource (lib "eagle-import") (part "MA20-2"))
    )
    (comp (ref "SV9")
      (value "MA20-2")
      (footprint "eagle-import:MA20-2")
      (libsource (lib "eagle-import") (part "MA20-2"))
    )
    (comp (ref "SYNC")
      (value "TPB1,27")
      (footprint "eagle-import:B1,27")
      (libsource (lib "eagle-import") (part "TPB1,27"))
    )
    (comp (ref "TP1")
      (value "TPB1,27")
      (footprint "eagle-import:B1,27")
      (libsource (lib "eagle-import") (part "TPB1,27"))
    )
    (comp (ref "TP2")
      (value "TPB1,27")
      (footprint "eagle-import:B1,27")
      (libsource (lib "eagle-import") (part "TPB1,27"))
    )
    (comp (ref "TP6")
      (value "TPB1,27")
      (footprint "eagle-import:B1,27")
      (libsource (lib "eagle-import") (part "TPB1,27"))
    )
    (comp (ref "TP7")
      (value "TPB1,27")
      (footprint "eagle-import:B1,27")
      (libsource (lib "eagle-import") (part "TPB1,27"))
    )
    (comp (ref "TP8")
      (value "TPB1,27")
      (footprint "eagle-import:B1,27")
      (libsource (lib "eagle-import") (part "TPB1,27"))
    )
    (comp (ref "TP9")
      (value "TPB1,27")
      (footprint "eagle-import:B1,27")
      (libsource (lib "eagle-import") (part "TPB1,27"))
    )
    (comp (ref "TP10")
      (value "TPB1,27")
      (footprint "eagle-import:B1,27")
      (libsource (lib "eagle-import") (part "TPB1,27"))
    )
    (comp (ref "TP11")
      (value "TPB1,27")
      (footprint "eagle-import:B1,27")
      (libsource (lib "eagle-import") (part "TPB1,27"))
    )
    (comp (ref "TP12")
      (value "TPB1,27")
      (footprint "eagle-import:B1,27")
      (libsource (lib "eagle-import") (part "TPB1,27"))
    )
    (comp (ref "TP13")
      (value "TPB1,27")
      (footprint "eagle-import:B1,27")
      (libsource (lib "eagle-import") (part "TPB1,27"))
    )
    (comp (ref "TP14")
      (value "TPB1,27")
      (footprint "eagle-import:B1,27")
      (libsource (lib "eagle-import") (part "TPB1,27"))
    )
    (comp (ref "TP15")
      (value "TPB1,27")
      (footprint "eagle-import:B1,27")
      (libsource (lib "eagle-import") (part "TPB1,27"))
    )
    (comp (ref "TP16")
      (value "TPB1,27")
      (footprint "eagle-import:B1,27")
      (libsource (lib "eagle-import") (part "TPB1,27"))
    )
    (comp (ref "TP17")
      (value "TPB1,27")
      (footprint "eagle-import:B1,27")
      (libsource (lib "eagle-import") (part "TPB1,27"))
    )
    (comp (ref "TP21")
      (value "TPB1,27")
      (footprint "eagle-import:B1,27")
      (libsource (lib "eagle-import") (part "TPB1,27"))
    )
    (comp (ref "TP22")
      (value "TPB1,27")
      (footprint "eagle-import:B1,27")
      (libsource (lib "eagle-import") (part "TPB1,27"))
    )
    (comp (ref "TP23")
      (value "TPB1,27")
      (footprint "eagle-import:B1,27")
      (libsource (lib "eagle-import") (part "TPB1,27"))
    )
    (comp (ref "TP25")
      (value "TPB1,27")
      (footprint "eagle-import:B1,27")
      (libsource (lib "eagle-import") (part "TPB1,27"))
    )
    (comp (ref "TP27")
      (value "TPB1,27")
      (footprint "eagle-import:B1,27")
      (libsource (lib "eagle-import") (part "TPB1,27"))
    )
    (comp (ref "U$1")
      (value "CY8CKIT-059_TARGET")
      (footprint "eagle-import:CY8CKIT-059_TARGET")
      (libsource (lib "eagle-import") (part "CY8CKIT-059_TARGET"))
    )
    (comp (ref "U1")
      (value "LT3082ESTPBF")
      (footprint "eagle-import:SOT-223_ST_LIT")
      (fields (field (name "MANUFACTURER_PART_NUMBER") "LT3082EST#PBF"))
      (libsource (lib "eagle-import") (part "LT3082ESTPBF"))
    )
    (comp (ref "U2")
      (value "LT3083EFEPBF")
      (footprint "eagle-import:TSSOP-16_FE_BB_LIT")
      (fields (field (name "MANUFACTURER_PART_NUMBER") "LT3083EFE#PBF"))
      (libsource (lib "eagle-import") (part "LT3083EFEPBF"))
    )
    (comp (ref "U3")
      (value "DAC7571IDBVR")
      (footprint "eagle-import:DBV6")
      (fields
        (field (name "GENERIC_PART_NUMBER") "DAC7571")
        (field (name "MANUFACTURER") "Texas Instruments")
      )
      (libsource (lib "eagle-import") (part "DAC7571IDBVR"))
    )
    (comp (ref "U4")
      (value "ADG714BRUZ")
      (footprint "eagle-import:RU_24_ADI")
      (libsource (lib "eagle-import") (part "ADG714BRUZ"))
    )
    (comp (ref "U5")
      (value "ADG714BRUZ")
      (footprint "eagle-import:RU_24_ADI")
      (libsource (lib "eagle-import") (part "ADG714BRUZ"))
    )
    (comp (ref "U6")
      (value "ADG714BRUZ")
      (footprint "eagle-import:RU_24_ADI")
      (libsource (lib "eagle-import") (part "ADG714BRUZ"))
    )
    (comp (ref "U7")
      (value "ADG714BRUZ")
      (footprint "eagle-import:RU_24_ADI")
      (libsource (lib "eagle-import") (part "ADG714BRUZ"))
    )
    (comp (ref "U8")
      (value "ADG714BRUZ")
      (footprint "eagle-import:RU_24_ADI")
      (libsource (lib "eagle-import") (part "ADG714BRUZ"))
    )
    (comp (ref "U9")
      (value "ADG714BRUZ")
      (footprint "eagle-import:RU_24_ADI")
      (libsource (lib "eagle-import") (part "ADG714BRUZ"))
    )
    (comp (ref "U10")
      (value "ADG714BRUZ")
      (footprint "eagle-import:RU_24_ADI")
      (libsource (lib "eagle-import") (part "ADG714BRUZ"))
    )
    (comp (ref "U11")
      (value "ADG714BRUZ")
      (footprint "eagle-import:RU_24_ADI")
      (libsource (lib "eagle-import") (part "ADG714BRUZ"))
    )
    (comp (ref "U12")
      (value "ADG714BRUZ")
      (footprint "eagle-import:RU_24_ADI")
      (libsource (lib "eagle-import") (part "ADG714BRUZ"))
    )
    (comp (ref "U13")
      (value "MC74LCX240DTR2G")
      (footprint "eagle-import:TSSOP20_4P50X6P60_ONS")
      (fields (field (name "COPYRIGHT") "Copyright (C) 2016 Accelerated Designs. All rights reserved"))
      (libsource (lib "eagle-import") (part "MC74LCX240DTR2G"))
    )
    (comp (ref "U14")
      (value "MC74LCX240DTR2G")
      (footprint "eagle-import:TSSOP20_4P50X6P60_ONS")
      (fields (field (name "COPYRIGHT") "Copyright (C) 2016 Accelerated Designs. All rights reserved"))
      (libsource (lib "eagle-import") (part "MC74LCX240DTR2G"))
    )
    (comp (ref "U15")
      (value "ADG714BRUZ")
      (footprint "eagle-import:RU_24_ADI")
      (libsource (lib "eagle-import") (part "ADG714BRUZ"))
    )
    (comp (ref "U16")
      (value "MC74LCX240DTR2G")
      (footprint "eagle-import:TSSOP20_4P50X6P60_ONS")
      (fields (field (name "COPYRIGHT") "Copyright (C) 2016 Accelerated Designs. All rights reserved"))
      (libsource (lib "eagle-import") (part "MC74LCX240DTR2G"))
    )
    (comp (ref "U17")
      (value "MC74LCX240DTR2G")
      (footprint "eagle-import:TSSOP20_4P50X6P60_ONS")
      (fields (field (name "COPYRIGHT") "Copyright (C) 2016 Accelerated Designs. All rights reserved"))
      (libsource (lib "eagle-import") (part "MC74LCX240DTR2G"))
    )
    (comp (ref "U18")
      (value "ADG714BRUZ")
      (footprint "eagle-import:RU_24_ADI")
      (libsource (lib "eagle-import") (part "ADG714BRUZ"))
    )
    (comp (ref "U19")
      (value "ADG714BRUZ")
      (footprint "eagle-import:RU_24_ADI")
      (libsource (lib "eagle-import") (part "ADG714BRUZ"))
    )
    (comp (ref "U20")
      (value "ADG714BRUZ")
      (footprint "eagle-import:RU_24_ADI")
      (libsource (lib "eagle-import") (part "ADG714BRUZ"))
    )
    (comp (ref "U21")
      (value "ADG714BRUZ")
      (footprint "eagle-import:RU_24_ADI")
      (libsource (lib "eagle-import") (part "ADG714BRUZ"))
    )
    (comp (ref "U22")
      (value "ADG714BRUZ")
      (footprint "eagle-import:RU_24_ADI")
      (libsource (lib "eagle-import") (part "ADG714BRUZ"))
    )
    (comp (ref "U23")
      (value "MC74LCX240DTR2G")
      (footprint "eagle-import:TSSOP20_4P50X6P60_ONS")
      (fields (field (name "COPYRIGHT") "Copyright (C) 2016 Accelerated Designs. All rights reserved"))
      (libsource (lib "eagle-import") (part "MC74LCX240DTR2G"))
    )
    (comp (ref "U24")
      (value "MC74LCX240DTR2G")
      (footprint "eagle-import:TSSOP20_4P50X6P60_ONS")
      (fields (field (name "COPYRIGHT") "Copyright (C) 2016 Accelerated Designs. All rights reserved"))
      (libsource (lib "eagle-import") (part "MC74LCX240DTR2G"))
    )
    (comp (ref "U25")
      (value "ADG714BRUZ")
      (footprint "eagle-import:RU_24_ADI")
      (libsource (lib "eagle-import") (part "ADG714BRUZ"))
    )
    (comp (ref "U26")
      (value "ADG714BRUZ")
      (footprint "eagle-import:RU_24_ADI")
      (libsource (lib "eagle-import") (part "ADG714BRUZ"))
    )
    (comp (ref "U27")
      (value "ADG714BRUZ")
      (footprint "eagle-import:RU_24_ADI")
      (libsource (lib "eagle-import") (part "ADG714BRUZ"))
    )
    (comp (ref "U28")
      (value "ADG714BRUZ")
      (footprint "eagle-import:RU_24_ADI")
      (libsource (lib "eagle-import") (part "ADG714BRUZ"))
    )
    (comp (ref "U29")
      (value "ADG714BRUZ")
      (footprint "eagle-import:RU_24_ADI")
      (libsource (lib "eagle-import") (part "ADG714BRUZ"))
    )
    (comp (ref "U30")
      (value "MC74LCX240DTR2G")
      (footprint "eagle-import:TSSOP20_4P50X6P60_ONS")
      (fields (field (name "COPYRIGHT") "Copyright (C) 2016 Accelerated Designs. All rights reserved"))
      (libsource (lib "eagle-import") (part "MC74LCX240DTR2G"))
    )
    (comp (ref "U31")
      (value "MC74LCX240DTR2G")
      (footprint "eagle-import:TSSOP20_4P50X6P60_ONS")
      (fields (field (name "COPYRIGHT") "Copyright (C) 2016 Accelerated Designs. All rights reserved"))
      (libsource (lib "eagle-import") (part "MC74LCX240DTR2G"))
    )
    (comp (ref "U32")
      (value "ADG714BRUZ")
      (footprint "eagle-import:RU_24_ADI")
      (libsource (lib "eagle-import") (part "ADG714BRUZ"))
    )
    (comp (ref "U33")
      (value "ADG714BRUZ")
      (footprint "eagle-import:RU_24_ADI")
      (libsource (lib "eagle-import") (part "ADG714BRUZ"))
    )
    (comp (ref "U34")
      (value "ADG714BRUZ")
      (footprint "eagle-import:RU_24_ADI")
      (libsource (lib "eagle-import") (part "ADG714BRUZ"))
    )
    (comp (ref "U35")
      (value "ADG714BRUZ")
      (footprint "eagle-import:RU_24_ADI")
      (libsource (lib "eagle-import") (part "ADG714BRUZ"))
    )
    (comp (ref "U36")
      (value "ADG714BRUZ")
      (footprint "eagle-import:RU_24_ADI")
      (libsource (lib "eagle-import") (part "ADG714BRUZ"))
    )
    (comp (ref "U37")
      (value "MC74LCX240DTR2G")
      (footprint "eagle-import:TSSOP20_4P50X6P60_ONS")
      (fields (field (name "COPYRIGHT") "Copyright (C) 2016 Accelerated Designs. All rights reserved"))
      (libsource (lib "eagle-import") (part "MC74LCX240DTR2G"))
    )
    (comp (ref "U38")
      (value "MC74LCX240DTR2G")
      (footprint "eagle-import:TSSOP20_4P50X6P60_ONS")
      (fields (field (name "COPYRIGHT") "Copyright (C) 2016 Accelerated Designs. All rights reserved"))
      (libsource (lib "eagle-import") (part "MC74LCX240DTR2G"))
    )
    (comp (ref "U39")
      (value "ADG714BRUZ")
      (footprint "eagle-import:RU_24_ADI")
      (libsource (lib "eagle-import") (part "ADG714BRUZ"))
    )
    (comp (ref "U40")
      (value "ADG714BRUZ")
      (footprint "eagle-import:RU_24_ADI")
      (libsource (lib "eagle-import") (part "ADG714BRUZ"))
    )
    (comp (ref "U41")
      (value "ADG714BRUZ")
      (footprint "eagle-import:RU_24_ADI")
      (libsource (lib "eagle-import") (part "ADG714BRUZ"))
    )
    (comp (ref "U42")
      (value "ADG714BRUZ")
      (footprint "eagle-import:RU_24_ADI")
      (libsource (lib "eagle-import") (part "ADG714BRUZ"))
    )
    (comp (ref "U43")
      (value "ADG714BRUZ")
      (footprint "eagle-import:RU_24_ADI")
      (libsource (lib "eagle-import") (part "ADG714BRUZ"))
    )
    (comp (ref "U44")
      (value "MC74LCX240DTR2G")
      (footprint "eagle-import:TSSOP20_4P50X6P60_ONS")
      (fields (field (name "COPYRIGHT") "Copyright (C) 2016 Accelerated Designs. All rights reserved"))
      (libsource (lib "eagle-import") (part "MC74LCX240DTR2G"))
    )
    (comp (ref "U45")
      (value "MC74LCX240DTR2G")
      (footprint "eagle-import:TSSOP20_4P50X6P60_ONS")
      (fields (field (name "COPYRIGHT") "Copyright (C) 2016 Accelerated Designs. All rights reserved"))
      (libsource (lib "eagle-import") (part "MC74LCX240DTR2G"))
    )
    (comp (ref "U46")
      (value "TCA9509DGKR")
      (footprint "eagle-import:DGK8")
      (fields
        (field (name "GENERIC_PART_NUMBER") "TCA9509")
        (field (name "MANUFACTURER") "Texas Instruments")
      )
      (libsource (lib "eagle-import") (part "TCA9509DGKR"))
    )
    (comp (ref "U47")
      (value "TCA9509DGKR")
      (footprint "eagle-import:DGK8")
      (fields
        (field (name "GENERIC_PART_NUMBER") "TCA9509")
        (field (name "MANUFACTURER") "Texas Instruments")
      )
      (libsource (lib "eagle-import") (part "TCA9509DGKR"))
    )
    (comp (ref "U48")
      (value "TCA9509DGKR")
      (footprint "eagle-import:DGK8")
      (fields
        (field (name "GENERIC_PART_NUMBER") "TCA9509")
        (field (name "MANUFACTURER") "Texas Instruments")
      )
      (libsource (lib "eagle-import") (part "TCA9509DGKR"))
    )
    (comp (ref "U49")
      (value "TCA9509DGKR")
      (footprint "eagle-import:DGK8")
      (fields
        (field (name "GENERIC_PART_NUMBER") "TCA9509")
        (field (name "MANUFACTURER") "Texas Instruments")
      )
      (libsource (lib "eagle-import") (part "TCA9509DGKR"))
    )
    (comp (ref "U54")
      (value "ADG715BRUZ")
      (footprint "eagle-import:RU_24_ADI")
      (libsource (lib "eagle-import") (part "ADG715BRUZ"))
    )
    (comp (ref "U56")
      (value "LSF0108RKSR")
      (footprint "eagle-import:RKS20_1P1X3P1_TEX")
      (libsource (lib "eagle-import") (part "LSF0108RKSR"))
    )
    (comp (ref "U58")
      (value "ADG715BRUZ")
      (footprint "eagle-import:RU_24_ADI")
      (libsource (lib "eagle-import") (part "ADG715BRUZ"))
    )
    (comp (ref "VDD")
      (value "TPB1,27")
      (footprint "eagle-import:B1,27")
      (libsource (lib "eagle-import") (part "TPB1,27"))
    )
    (comp (ref "X2")
      (value "MPB2M")
      (footprint "eagle-import:MPB2M")
      (libsource (lib "eagle-import") (part "MPB2M"))
    )
    (comp (ref "X3")
      (value "MPB2M")
      (footprint "eagle-import:MPB2M")
      (libsource (lib "eagle-import") (part "MPB2M"))
    )
    (comp (ref "X4")
      (value "MPB2M")
      (footprint "eagle-import:MPB2M")
      (libsource (lib "eagle-import") (part "MPB2M"))
    )
    (comp (ref "X5")
      (value "MPB2M")
      (footprint "eagle-import:MPB2M")
      (libsource (lib "eagle-import") (part "MPB2M"))
    )
    (comp (ref "X6")
      (value "MPB2M")
      (footprint "eagle-import:MPB2M")
      (libsource (lib "eagle-import") (part "MPB2M"))
    )
  )
  (nets
    (net (code "1") (name "+5V") (class "Default")
      (node (ref "5V") (pin "TP") (pinfunction "TP_TP") (pintype "input"))
      (node (ref "C18") (pin "1") (pinfunction "1_1") (pintype "passive"))
      (node (ref "C19") (pin "1") (pinfunction "1_1") (pintype "passive"))
      (node (ref "C20") (pin "1") (pinfunction "1_1") (pintype "passive"))
      (node (ref "C21") (pin "1") (pinfunction "1_1") (pintype "passive"))
      (node (ref "C25") (pin "1") (pinfunction "1_1") (pintype "passive"))
      (node (ref "C3") (pin "1") (pinfunction "1_1") (pintype "passive"))
      (node (ref "C31") (pin "1") (pinfunction "1_1") (pintype "passive"))
      (node (ref "C32") (pin "1") (pinfunction "1_1") (pintype "passive"))
      (node (ref "C33") (pin "1") (pinfunction "1_1") (pintype "passive"))
      (node (ref "C34") (pin "1") (pinfunction "1_1") (pintype "passive"))
      (node (ref "C37") (pin "1") (pinfunction "1_1") (pintype "passive"))
      (node (ref "C38") (pin "1") (pinfunction "1_1") (pintype "passive"))
      (node (ref "C39") (pin "1") (pinfunction "1_1") (pintype "passive"))
      (node (ref "C40") (pin "1") (pinfunction "1_1") (pintype "passive"))
      (node (ref "C43") (pin "1") (pinfunction "1_1") (pintype "passive"))
      (node (ref "C44") (pin "1") (pinfunction "1_1") (pintype "passive"))
      (node (ref "C45") (pin "1") (pinfunction "1_1") (pintype "passive"))
      (node (ref "C46") (pin "1") (pinfunction "1_1") (pintype "passive"))
      (node (ref "C49") (pin "1") (pinfunction "1_1") (pintype "passive"))
      (node (ref "C50") (pin "1") (pinfunction "1_1") (pintype "passive"))
      (node (ref "C51") (pin "1") (pinfunction "1_1") (pintype "passive"))
      (node (ref "C52") (pin "1") (pinfunction "1_1") (pintype "passive"))
      (node (ref "C55") (pin "1") (pinfunction "1_1") (pintype "passive"))
      (node (ref "C56") (pin "1") (pinfunction "1_1") (pintype "passive"))
      (node (ref "C57") (pin "1") (pinfunction "1_1") (pintype "passive"))
      (node (ref "C58") (pin "1") (pinfunction "1_1") (pintype "passive"))
      (node (ref "C59") (pin "1") (pinfunction "1_1") (pintype "passive"))
      (node (ref "C60") (pin "1") (pinfunction "1_1") (pintype "passive"))
      (node (ref "C61") (pin "1") (pinfunction "1_1") (pintype "passive"))
      (node (ref "C62") (pin "1") (pinfunction "1_1") (pintype "passive"))
      (node (ref "C63") (pin "1") (pinfunction "1_1") (pintype "passive"))
      (node (ref "C64") (pin "1") (pinfunction "1_1") (pintype "passive"))
      (node (ref "C65") (pin "1") (pinfunction "1_1") (pintype "passive"))
      (node (ref "C66") (pin "1") (pinfunction "1_1") (pintype "passive"))
      (node (ref "C67") (pin "2") (pinfunction "2_2") (pintype "passive"))
      (node (ref "R10") (pin "1") (pinfunction "1_1") (pintype "passive"))
      (node (ref "R107") (pin "2") (pinfunction "2_2") (pintype "passive"))
      (node (ref "R108") (pin "1") (pinfunction "1_1") (pintype "passive"))
      (node (ref "R109") (pin "1") (pinfunction "1_1") (pintype "passive"))
      (node (ref "R11") (pin "1") (pinfunction "1_1") (pintype "passive"))
      (node (ref "R110") (pin "1") (pinfunction "1_1") (pintype "passive"))
      (node (ref "R111") (pin "1") (pinfunction "1_1") (pintype "passive"))
      (node (ref "R128") (pin "2") (pinfunction "2_2") (pintype "passive"))
      (node (ref "R154") (pin "1") (pinfunction "1_1") (pintype "passive"))
      (node (ref "R156") (pin "1") (pinfunction "1_1") (pintype "passive"))
      (node (ref "R161") (pin "1") (pinfunction "1_1") (pintype "passive"))
      (node (ref "R162") (pin "1") (pinfunction "1_1") (pintype "passive"))
      (node (ref "R163") (pin "1") (pinfunction "1_1") (pintype "passive"))
      (node (ref "R164") (pin "1") (pinfunction "1_1") (pintype "passive"))
      (node (ref "R165") (pin "1") (pinfunction "1_1") (pintype "passive"))
      (node (ref "R166") (pin "1") (pinfunction "1_1") (pintype "passive"))
      (node (ref "R167") (pin "1") (pinfunction "1_1") (pintype "passive"))
      (node (ref "R168") (pin "1") (pinfunction "1_1") (pintype "passive"))
      (node (ref "R169") (pin "1") (pinfunction "1_1") (pintype "passive"))
      (node (ref "R3") (pin "1") (pinfunction "1_1") (pintype "passive"))
      (node (ref "R4") (pin "1") (pinfunction "1_1") (pintype "passive"))
      (node (ref "R44") (pin "2") (pinfunction "2_2") (pintype "passive"))
      (node (ref "R45") (pin "1") (pinfunction "1_1") (pintype "passive"))
      (node (ref "R46") (pin "1") (pinfunction "1_1") (pintype "passive"))
      (node (ref "R47") (pin "1") (pinfunction "1_1") (pintype "passive"))
      (node (ref "R48") (pin "1") (pinfunction "1_1") (pintype "passive"))
      (node (ref "R5") (pin "1") (pinfunction "1_1") (pintype "passive"))
      (node (ref "R6") (pin "1") (pinfunction "1_1") (pintype "passive"))
      (node (ref "R65") (pin "2") (pinfunction "2_2") (pintype "passive"))
      (node (ref "R66") (pin "1") (pinfunction "1_1") (pintype "passive"))
      (node (ref "R67") (pin "1") (pinfunction "1_1") (pintype "passive"))
      (node (ref "R68") (pin "1") (pinfunction "1_1") (pintype "passive"))
      (node (ref "R69") (pin "1") (pinfunction "1_1") (pintype "passive"))
      (node (ref "R7") (pin "1") (pinfunction "1_1") (pintype "passive"))
      (node (ref "R8") (pin "2") (pinfunction "2_2") (pintype "passive"))
      (node (ref "R86") (pin "2") (pinfunction "2_2") (pintype "passive"))
      (node (ref "R87") (pin "1") (pinfunction "1_1") (pintype "passive"))
      (node (ref "R88") (pin "1") (pinfunction "1_1") (pintype "passive"))
      (node (ref "R89") (pin "1") (pinfunction "1_1") (pintype "passive"))
      (node (ref "R9") (pin "1") (pinfunction "1_1") (pintype "passive"))
      (node (ref "R90") (pin "1") (pinfunction "1_1") (pintype "passive"))
      (node (ref "R_LDO2") (pin "1") (pinfunction "1_1") (pintype "passive"))
      (node (ref "U$1") (pin "26") (pinfunction "VDDIO_26") (pintype "bidirectional"))
      (node (ref "U$1") (pin "27") (pinfunction "VDD_27") (pintype "bidirectional"))
      (node (ref "U1") (pin "2") (pinfunction "OUT_2") (pintype "output"))
      (node (ref "U10") (pin "2") (pinfunction "VDD_2") (pintype "power_in"))
      (node (ref "U10") (pin "23") (pinfunction "RESET_N_23") (pintype "passive"))
      (node (ref "U11") (pin "2") (pinfunction "VDD_2") (pintype "power_in"))
      (node (ref "U11") (pin "23") (pinfunction "RESET_N_23") (pintype "passive"))
      (node (ref "U12") (pin "2") (pinfunction "VDD_2") (pintype "power_in"))
      (node (ref "U12") (pin "23") (pinfunction "RESET_N_23") (pintype "passive"))
      (node (ref "U15") (pin "2") (pinfunction "VDD_2") (pintype "power_in"))
      (node (ref "U15") (pin "23") (pinfunction "RESET_N_23") (pintype "passive"))
      (node (ref "U18") (pin "2") (pinfunction "VDD_2") (pintype "power_in"))
      (node (ref "U18") (pin "23") (pinfunction "RESET_N_23") (pintype "passive"))
      (node (ref "U19") (pin "2") (pinfunction "VDD_2") (pintype "power_in"))
      (node (ref "U19") (pin "23") (pinfunction "RESET_N_23") (pintype "passive"))
      (node (ref "U2") (pin "10") (pinfunction "VCONTROL_2_10") (pintype "passive"))
      (node (ref "U2") (pin "11") (pinfunction "VCONTROL_11") (pintype "passive"))
      (node (ref "U2") (pin "12") (pinfunction "IN_2_12") (pintype "input"))
      (node (ref "U2") (pin "13") (pinfunction "IN_3_13") (pintype "input"))
      (node (ref "U2") (pin "14") (pinfunction "IN_4_14") (pintype "input"))
      (node (ref "U2") (pin "15") (pinfunction "IN_15") (pintype "input"))
      (node (ref "U20") (pin "2") (pinfunction "VDD_2") (pintype "power_in"))
      (node (ref "U20") (pin "23") (pinfunction "RESET_N_23") (pintype "passive"))
      (node (ref "U21") (pin "2") (pinfunction "VDD_2") (pintype "power_in"))
      (node (ref "U21") (pin "23") (pinfunction "RESET_N_23") (pintype "passive"))
      (node (ref "U22") (pin "2") (pinfunction "VDD_2") (pintype "power_in"))
      (node (ref "U22") (pin "23") (pinfunction "RESET_N_23") (pintype "passive"))
      (node (ref "U25") (pin "2") (pinfunction "VDD_2") (pintype "power_in"))
      (node (ref "U25") (pin "23") (pinfunction "RESET_N_23") (pintype "passive"))
      (node (ref "U26") (pin "2") (pinfunction "VDD_2") (pintype "power_in"))
      (node (ref "U26") (pin "23") (pinfunction "RESET_N_23") (pintype "passive"))
      (node (ref "U27") (pin "2") (pinfunction "VDD_2") (pintype "power_in"))
      (node (ref "U27") (pin "23") (pinfunction "RESET_N_23") (pintype "passive"))
      (node (ref "U28") (pin "2") (pinfunction "VDD_2") (pintype "power_in"))
      (node (ref "U28") (pin "23") (pinfunction "RESET_N_23") (pintype "passive"))
      (node (ref "U29") (pin "2") (pinfunction "VDD_2") (pintype "power_in"))
      (node (ref "U29") (pin "23") (pinfunction "RESET_N_23") (pintype "passive"))
      (node (ref "U3") (pin "3") (pinfunction "VDD_3") (pintype "power_in"))
      (node (ref "U3") (pin "6") (pinfunction "A0_6") (pintype "passive"))
      (node (ref "U32") (pin "2") (pinfunction "VDD_2") (pintype "power_in"))
      (node (ref "U32") (pin "23") (pinfunction "RESET_N_23") (pintype "passive"))
      (node (ref "U33") (pin "2") (pinfunction "VDD_2") (pintype "power_in"))
      (node (ref "U33") (pin "23") (pinfunction "RESET_N_23") (pintype "passive"))
      (node (ref "U34") (pin "2") (pinfunction "VDD_2") (pintype "power_in"))
      (node (ref "U34") (pin "23") (pinfunction "RESET_N_23") (pintype "passive"))
      (node (ref "U35") (pin "2") (pinfunction "VDD_2") (pintype "power_in"))
      (node (ref "U35") (pin "23") (pinfunction "RESET_N_23") (pintype "passive"))
      (node (ref "U36") (pin "2") (pinfunction "VDD_2") (pintype "power_in"))
      (node (ref "U36") (pin "23") (pinfunction "RESET_N_23") (pintype "passive"))
      (node (ref "U39") (pin "2") (pinfunction "VDD_2") (pintype "power_in"))
      (node (ref "U39") (pin "23") (pinfunction "RESET_N_23") (pintype "passive"))
      (node (ref "U4") (pin "2") (pinfunction "VDD_2") (pintype "power_in"))
      (node (ref "U4") (pin "23") (pinfunction "RESET_N_23") (pintype "passive"))
      (node (ref "U40") (pin "2") (pinfunction "VDD_2") (pintype "power_in"))
      (node (ref "U40") (pin "23") (pinfunction "RESET_N_23") (pintype "passive"))
      (node (ref "U41") (pin "2") (pinfunction "VDD_2") (pintype "power_in"))
      (node (ref "U41") (pin "23") (pinfunction "RESET_N_23") (pintype "passive"))
      (node (ref "U42") (pin "2") (pinfunction "VDD_2") (pintype "power_in"))
      (node (ref "U42") (pin "23") (pinfunction "RESET_N_23") (pintype "passive"))
      (node (ref "U43") (pin "2") (pinfunction "VDD_2") (pintype "power_in"))
      (node (ref "U43") (pin "23") (pinfunction "RESET_N_23") (pintype "passive"))
      (node (ref "U5") (pin "2") (pinfunction "VDD_2") (pintype "power_in"))
      (node (ref "U5") (pin "23") (pinfunction "RESET_N_23") (pintype "passive"))
      (node (ref "U54") (pin "2") (pinfunction "VDD_2") (pintype "power_in"))
      (node (ref "U54") (pin "23") (pinfunction "RESET_23") (pintype "passive"))
      (node (ref "U58") (pin "2") (pinfunction "VDD_2") (pintype "power_in"))
      (node (ref "U58") (pin "23") (pinfunction "RESET_23") (pintype "passive"))
      (node (ref "U58") (pin "24") (pinfunction "A0_24") (pintype "passive"))
      (node (ref "U6") (pin "2") (pinfunction "VDD_2") (pintype "power_in"))
      (node (ref "U6") (pin "23") (pinfunction "RESET_N_23") (pintype "passive"))
      (node (ref "U7") (pin "2") (pinfunction "VDD_2") (pintype "power_in"))
      (node (ref "U7") (pin "23") (pinfunction "RESET_N_23") (pintype "passive"))
      (node (ref "U8") (pin "2") (pinfunction "VDD_2") (pintype "power_in"))
      (node (ref "U8") (pin "23") (pinfunction "RESET_N_23") (pintype "passive"))
      (node (ref "U9") (pin "2") (pinfunction "VDD_2") (pintype "power_in"))
      (node (ref "U9") (pin "23") (pinfunction "RESET_N_23") (pintype "passive"))
    )
    (net (code "2") (name "+12V") (class "Default")
      (node (ref "C27") (pin "1") (pinfunction "1_1") (pintype "passive"))
      (node (ref "C28") (pin "1") (pinfunction "1_1") (pintype "passive"))
      (node (ref "JP2") (pin "1") (pinfunction "1_1") (pintype "passive"))
      (node (ref "SV2") (pin "1") (pinfunction "1_1") (pintype "passive"))
      (node (ref "SV2") (pin "2") (pinfunction "2_2") (pintype "passive"))
      (node (ref "SV2") (pin "3") (pinfunction "3_3") (pintype "passive"))
      (node (ref "SV2") (pin "4") (pinfunction "4_4") (pintype "passive"))
      (node (ref "SV9") (pin "37") (pinfunction "37_37") (pintype "passive"))
      (node (ref "SV9") (pin "38") (pinfunction "38_38") (pintype "passive"))
      (node (ref "SV9") (pin "39") (pinfunction "39_39") (pintype "passive"))
      (node (ref "SV9") (pin "40") (pinfunction "40_40") (pintype "passive"))
      (node (ref "X4") (pin "1") (pinfunction "1_1") (pintype "passive"))
      (node (ref "X4") (pin "1@1") (pinfunction "1_1@1") (pintype "passive"))
    )
    (net (code "3") (name "/INT0") (class "Default")
      (node (ref "SV2") (pin "21") (pinfunction "21_21") (pintype "passive"))
      (node (ref "U5") (pin "6") (pinfunction "D1_6") (pintype "passive"))
    )
    (net (code "4") (name "/INT1") (class "Default")
      (node (ref "SV2") (pin "22") (pinfunction "22_22") (pintype "passive"))
      (node (ref "U5") (pin "8") (pinfunction "D2_8") (pintype "passive"))
    )
    (net (code "5") (name "/INT2") (class "Default")
      (node (ref "SV2") (pin "27") (pinfunction "27_27") (pintype "passive"))
      (node (ref "U5") (pin "10") (pinfunction "D3_10") (pintype "passive"))
    )
    (net (code "6") (name "/INT3") (class "Default")
      (node (ref "SV2") (pin "28") (pinfunction "28_28") (pintype "passive"))
      (node (ref "U5") (pin "12") (pinfunction "D4_12") (pintype "passive"))
    )
    (net (code "7") (name "/INT4") (class "Default")
      (node (ref "SV2") (pin "33") (pinfunction "33_33") (pintype "passive"))
      (node (ref "U5") (pin "13") (pinfunction "D5_13") (pintype "passive"))
    )
    (net (code "8") (name "/INT5") (class "Default")
      (node (ref "SV2") (pin "34") (pinfunction "34_34") (pintype "passive"))
      (node (ref "U5") (pin "15") (pinfunction "D6_15") (pintype "passive"))
    )
    (net (code "9") (name "/INT6") (class "Default")
      (node (ref "SV2") (pin "39") (pinfunction "39_39") (pintype "passive"))
      (node (ref "U5") (pin "17") (pinfunction "D7_17") (pintype "passive"))
    )
    (net (code "10") (name "/INT7") (class "Default")
      (node (ref "SV2") (pin "40") (pinfunction "40_40") (pintype "passive"))
      (node (ref "U5") (pin "19") (pinfunction "D8_19") (pintype "passive"))
    )
    (net (code "11") (name "/INT8") (class "Default")
      (node (ref "SV3") (pin "5") (pinfunction "5_5") (pintype "passive"))
      (node (ref "U6") (pin "6") (pinfunction "D1_6") (pintype "passive"))
    )
    (net (code "12") (name "/INT9") (class "Default")
      (node (ref "SV3") (pin "6") (pinfunction "6_6") (pintype "passive"))
      (node (ref "U6") (pin "8") (pinfunction "D2_8") (pintype "passive"))
    )
    (net (code "13") (name "/INT10") (class "Default")
      (node (ref "SV3") (pin "11") (pinfunction "11_11") (pintype "passive"))
      (node (ref "U6") (pin "10") (pinfunction "D3_10") (pintype "passive"))
    )
    (net (code "14") (name "/INT11") (class "Default")
      (node (ref "SV3") (pin "12") (pinfunction "12_12") (pintype "passive"))
      (node (ref "U6") (pin "12") (pinfunction "D4_12") (pintype "passive"))
    )
    (net (code "15") (name "/INT12") (class "Default")
      (node (ref "SV3") (pin "17") (pinfunction "17_17") (pintype "passive"))
      (node (ref "U6") (pin "13") (pinfunction "D5_13") (pintype "passive"))
    )
    (net (code "16") (name "/INT13") (class "Default")
      (node (ref "SV3") (pin "18") (pinfunction "18_18") (pintype "passive"))
      (node (ref "U6") (pin "15") (pinfunction "D6_15") (pintype "passive"))
    )
    (net (code "17") (name "/INT14") (class "Default")
      (node (ref "SV3") (pin "23") (pinfunction "23_23") (pintype "passive"))
      (node (ref "U6") (pin "17") (pinfunction "D7_17") (pintype "passive"))
    )
    (net (code "18") (name "/INT15") (class "Default")
      (node (ref "SV3") (pin "24") (pinfunction "24_24") (pintype "passive"))
      (node (ref "U6") (pin "19") (pinfunction "D8_19") (pintype "passive"))
    )
    (net (code "19") (name "/INT16") (class "Default")
      (node (ref "SV6") (pin "6") (pinfunction "6_6") (pintype "passive"))
      (node (ref "U25") (pin "6") (pinfunction "D1_6") (pintype "passive"))
    )
    (net (code "20") (name "/INT17") (class "Default")
      (node (ref "SV6") (pin "11") (pinfunction "11_11") (pintype "passive"))
      (node (ref "U25") (pin "8") (pinfunction "D2_8") (pintype "passive"))
    )
    (net (code "21") (name "/INT18") (class "Default")
      (node (ref "SV6") (pin "12") (pinfunction "12_12") (pintype "passive"))
      (node (ref "U25") (pin "10") (pinfunction "D3_10") (pintype "passive"))
    )
    (net (code "22") (name "/INT19") (class "Default")
      (node (ref "SV6") (pin "17") (pinfunction "17_17") (pintype "passive"))
      (node (ref "U25") (pin "12") (pinfunction "D4_12") (pintype "passive"))
    )
    (net (code "23") (name "/INT20") (class "Default")
      (node (ref "SV6") (pin "18") (pinfunction "18_18") (pintype "passive"))
      (node (ref "U25") (pin "13") (pinfunction "D5_13") (pintype "passive"))
    )
    (net (code "24") (name "/INT21") (class "Default")
      (node (ref "SV6") (pin "23") (pinfunction "23_23") (pintype "passive"))
      (node (ref "U25") (pin "15") (pinfunction "D6_15") (pintype "passive"))
    )
    (net (code "25") (name "/INT22") (class "Default")
      (node (ref "SV6") (pin "24") (pinfunction "24_24") (pintype "passive"))
      (node (ref "U25") (pin "17") (pinfunction "D7_17") (pintype "passive"))
    )
    (net (code "26") (name "/INT23") (class "Default")
      (node (ref "SV6") (pin "29") (pinfunction "29_29") (pintype "passive"))
      (node (ref "U25") (pin "19") (pinfunction "D8_19") (pintype "passive"))
    )
    (net (code "27") (name "/INT24") (class "Default")
      (node (ref "SV6") (pin "30") (pinfunction "30_30") (pintype "passive"))
      (node (ref "U27") (pin "6") (pinfunction "D1_6") (pintype "passive"))
    )
    (net (code "28") (name "/INT25") (class "Default")
      (node (ref "SV6") (pin "35") (pinfunction "35_35") (pintype "passive"))
      (node (ref "U27") (pin "8") (pinfunction "D2_8") (pintype "passive"))
    )
    (net (code "29") (name "/INT26") (class "Default")
      (node (ref "SV6") (pin "36") (pinfunction "36_36") (pintype "passive"))
      (node (ref "U27") (pin "10") (pinfunction "D3_10") (pintype "passive"))
    )
    (net (code "30") (name "/INT27") (class "Default")
      (node (ref "SV6") (pin "38") (pinfunction "38_38") (pintype "passive"))
      (node (ref "U27") (pin "12") (pinfunction "D4_12") (pintype "passive"))
    )
    (net (code "31") (name "/INT28") (class "Default")
      (node (ref "SV7") (pin "5") (pinfunction "5_5") (pintype "passive"))
      (node (ref "U27") (pin "13") (pinfunction "D5_13") (pintype "passive"))
    )
    (net (code "32") (name "/INT29") (class "Default")
      (node (ref "SV7") (pin "6") (pinfunction "6_6") (pintype "passive"))
      (node (ref "U27") (pin "15") (pinfunction "D6_15") (pintype "passive"))
    )
    (net (code "33") (name "/INT30") (class "Default")
      (node (ref "SV7") (pin "11") (pinfunction "11_11") (pintype "passive"))
      (node (ref "U27") (pin "17") (pinfunction "D7_17") (pintype "passive"))
    )
    (net (code "34") (name "/INT31") (class "Default")
      (node (ref "SV7") (pin "12") (pinfunction "12_12") (pintype "passive"))
      (node (ref "U27") (pin "19") (pinfunction "D8_19") (pintype "passive"))
    )
    (net (code "35") (name "/INT32") (class "Default")
      (node (ref "SV3") (pin "29") (pinfunction "29_29") (pintype "passive"))
      (node (ref "U7") (pin "6") (pinfunction "D1_6") (pintype "passive"))
    )
    (net (code "36") (name "/INT33") (class "Default")
      (node (ref "SV3") (pin "30") (pinfunction "30_30") (pintype "passive"))
      (node (ref "U7") (pin "8") (pinfunction "D2_8") (pintype "passive"))
    )
    (net (code "37") (name "/INT34") (class "Default")
      (node (ref "SV3") (pin "35") (pinfunction "35_35") (pintype "passive"))
      (node (ref "U7") (pin "10") (pinfunction "D3_10") (pintype "passive"))
    )
    (net (code "38") (name "/INT35") (class "Default")
      (node (ref "SV3") (pin "36") (pinfunction "36_36") (pintype "passive"))
      (node (ref "U7") (pin "12") (pinfunction "D4_12") (pintype "passive"))
    )
    (net (code "39") (name "/INT36") (class "Default")
      (node (ref "SV3") (pin "38") (pinfunction "38_38") (pintype "passive"))
      (node (ref "U7") (pin "13") (pinfunction "D5_13") (pintype "passive"))
    )
    (net (code "40") (name "/INT37") (class "Default")
      (node (ref "SV4") (pin "5") (pinfunction "5_5") (pintype "passive"))
      (node (ref "U7") (pin "15") (pinfunction "D6_15") (pintype "passive"))
    )
    (net (code "41") (name "/INT38") (class "Default")
      (node (ref "SV4") (pin "6") (pinfunction "6_6") (pintype "passive"))
      (node (ref "U7") (pin "17") (pinfunction "D7_17") (pintype "passive"))
    )
    (net (code "42") (name "/INT39") (class "Default")
      (node (ref "SV4") (pin "11") (pinfunction "11_11") (pintype "passive"))
      (node (ref "U7") (pin "19") (pinfunction "D8_19") (pintype "passive"))
    )
    (net (code "43") (name "/INT40") (class "Default")
      (node (ref "SV4") (pin "12") (pinfunction "12_12") (pintype "passive"))
      (node (ref "U11") (pin "6") (pinfunction "D1_6") (pintype "passive"))
    )
    (net (code "44") (name "/INT41") (class "Default")
      (node (ref "SV4") (pin "17") (pinfunction "17_17") (pintype "passive"))
      (node (ref "U11") (pin "8") (pinfunction "D2_8") (pintype "passive"))
    )
    (net (code "45") (name "/INT42") (class "Default")
      (node (ref "SV4") (pin "18") (pinfunction "18_18") (pintype "passive"))
      (node (ref "U11") (pin "10") (pinfunction "D3_10") (pintype "passive"))
    )
    (net (code "46") (name "/INT43") (class "Default")
      (node (ref "SV4") (pin "23") (pinfunction "23_23") (pintype "passive"))
      (node (ref "U11") (pin "12") (pinfunction "D4_12") (pintype "passive"))
    )
    (net (code "47") (name "/INT44") (class "Default")
      (node (ref "SV4") (pin "24") (pinfunction "24_24") (pintype "passive"))
      (node (ref "U11") (pin "13") (pinfunction "D5_13") (pintype "passive"))
    )
    (net (code "48") (name "/INT45") (class "Default")
      (node (ref "SV4") (pin "29") (pinfunction "29_29") (pintype "passive"))
      (node (ref "U11") (pin "15") (pinfunction "D6_15") (pintype "passive"))
    )
    (net (code "49") (name "/INT46") (class "Default")
      (node (ref "SV4") (pin "30") (pinfunction "30_30") (pintype "passive"))
      (node (ref "U11") (pin "17") (pinfunction "D7_17") (pintype "passive"))
    )
    (net (code "50") (name "/INT47") (class "Default")
      (node (ref "SV4") (pin "35") (pinfunction "35_35") (pintype "passive"))
      (node (ref "U11") (pin "19") (pinfunction "D8_19") (pintype "passive"))
    )
    (net (code "51") (name "/INT48") (class "Default")
      (node (ref "SV7") (pin "17") (pinfunction "17_17") (pintype "passive"))
      (node (ref "U32") (pin "6") (pinfunction "D1_6") (pintype "passive"))
    )
    (net (code "52") (name "/INT49") (class "Default")
      (node (ref "SV7") (pin "18") (pinfunction "18_18") (pintype "passive"))
      (node (ref "U32") (pin "8") (pinfunction "D2_8") (pintype "passive"))
    )
    (net (code "53") (name "/INT50") (class "Default")
      (node (ref "SV7") (pin "23") (pinfunction "23_23") (pintype "passive"))
      (node (ref "U32") (pin "10") (pinfunction "D3_10") (pintype "passive"))
    )
    (net (code "54") (name "/INT51") (class "Default")
      (node (ref "SV7") (pin "24") (pinfunction "24_24") (pintype "passive"))
      (node (ref "U32") (pin "12") (pinfunction "D4_12") (pintype "passive"))
    )
    (net (code "55") (name "/INT52") (class "Default")
      (node (ref "SV7") (pin "29") (pinfunction "29_29") (pintype "passive"))
      (node (ref "U32") (pin "13") (pinfunction "D5_13") (pintype "passive"))
    )
    (net (code "56") (name "/INT53") (class "Default")
      (node (ref "SV7") (pin "30") (pinfunction "30_30") (pintype "passive"))
      (node (ref "U32") (pin "15") (pinfunction "D6_15") (pintype "passive"))
    )
    (net (code "57") (name "/INT54") (class "Default")
      (node (ref "SV7") (pin "35") (pinfunction "35_35") (pintype "passive"))
      (node (ref "U32") (pin "17") (pinfunction "D7_17") (pintype "passive"))
    )
    (net (code "58") (name "/INT55") (class "Default")
      (node (ref "SV7") (pin "36") (pinfunction "36_36") (pintype "passive"))
      (node (ref "U32") (pin "19") (pinfunction "D8_19") (pintype "passive"))
    )
    (net (code "59") (name "/INT56") (class "Default")
      (node (ref "SV7") (pin "38") (pinfunction "38_38") (pintype "passive"))
      (node (ref "U34") (pin "6") (pinfunction "D1_6") (pintype "passive"))
    )
    (net (code "60") (name "/INT57") (class "Default")
      (node (ref "SV8") (pin "5") (pinfunction "5_5") (pintype "passive"))
      (node (ref "U34") (pin "8") (pinfunction "D2_8") (pintype "passive"))
    )
    (net (code "61") (name "/INT58") (class "Default")
      (node (ref "SV8") (pin "6") (pinfunction "6_6") (pintype "passive"))
      (node (ref "U34") (pin "10") (pinfunction "D3_10") (pintype "passive"))
    )
    (net (code "62") (name "/INT59") (class "Default")
      (node (ref "SV8") (pin "11") (pinfunction "11_11") (pintype "passive"))
      (node (ref "U34") (pin "12") (pinfunction "D4_12") (pintype "passive"))
    )
    (net (code "63") (name "/INT60") (class "Default")
      (node (ref "SV8") (pin "12") (pinfunction "12_12") (pintype "passive"))
      (node (ref "U34") (pin "13") (pinfunction "D5_13") (pintype "passive"))
    )
    (net (code "64") (name "/INT61") (class "Default")
      (node (ref "SV8") (pin "17") (pinfunction "17_17") (pintype "passive"))
      (node (ref "U34") (pin "15") (pinfunction "D6_15") (pintype "passive"))
    )
    (net (code "65") (name "/INT62") (class "Default")
      (node (ref "SV8") (pin "18") (pinfunction "18_18") (pintype "passive"))
      (node (ref "U34") (pin "17") (pinfunction "D7_17") (pintype "passive"))
    )
    (net (code "66") (name "/INT63") (class "Default")
      (node (ref "SV8") (pin "23") (pinfunction "23_23") (pintype "passive"))
      (node (ref "U34") (pin "19") (pinfunction "D8_19") (pintype "passive"))
    )
    (net (code "67") (name "/INT64") (class "Default")
      (node (ref "SV4") (pin "36") (pinfunction "36_36") (pintype "passive"))
      (node (ref "U18") (pin "6") (pinfunction "D1_6") (pintype "passive"))
    )
    (net (code "68") (name "/INT65") (class "Default")
      (node (ref "SV4") (pin "38") (pinfunction "38_38") (pintype "passive"))
      (node (ref "U18") (pin "8") (pinfunction "D2_8") (pintype "passive"))
    )
    (net (code "69") (name "/INT66") (class "Default")
      (node (ref "SV5") (pin "5") (pinfunction "5_5") (pintype "passive"))
      (node (ref "U18") (pin "10") (pinfunction "D3_10") (pintype "passive"))
    )
    (net (code "70") (name "/INT67") (class "Default")
      (node (ref "SV5") (pin "6") (pinfunction "6_6") (pintype "passive"))
      (node (ref "U18") (pin "12") (pinfunction "D4_12") (pintype "passive"))
    )
    (net (code "71") (name "/INT68") (class "Default")
      (node (ref "SV5") (pin "11") (pinfunction "11_11") (pintype "passive"))
      (node (ref "U18") (pin "13") (pinfunction "D5_13") (pintype "passive"))
    )
    (net (code "72") (name "/INT69") (class "Default")
      (node (ref "SV5") (pin "12") (pinfunction "12_12") (pintype "passive"))
      (node (ref "U18") (pin "15") (pinfunction "D6_15") (pintype "passive"))
    )
    (net (code "73") (name "/INT70") (class "Default")
      (node (ref "SV5") (pin "17") (pinfunction "17_17") (pintype "passive"))
      (node (ref "U18") (pin "17") (pinfunction "D7_17") (pintype "passive"))
    )
    (net (code "74") (name "/INT71") (class "Default")
      (node (ref "SV5") (pin "18") (pinfunction "18_18") (pintype "passive"))
      (node (ref "U18") (pin "19") (pinfunction "D8_19") (pintype "passive"))
    )
    (net (code "75") (name "/INT72") (class "Default")
      (node (ref "SV5") (pin "23") (pinfunction "23_23") (pintype "passive"))
      (node (ref "U20") (pin "6") (pinfunction "D1_6") (pintype "passive"))
    )
    (net (code "76") (name "/INT73") (class "Default")
      (node (ref "SV5") (pin "24") (pinfunction "24_24") (pintype "passive"))
      (node (ref "U20") (pin "8") (pinfunction "D2_8") (pintype "passive"))
    )
    (net (code "77") (name "/INT74") (class "Default")
      (node (ref "SV5") (pin "29") (pinfunction "29_29") (pintype "passive"))
      (node (ref "U20") (pin "10") (pinfunction "D3_10") (pintype "passive"))
    )
    (net (code "78") (name "/INT75") (class "Default")
      (node (ref "SV5") (pin "30") (pinfunction "30_30") (pintype "passive"))
      (node (ref "U20") (pin "12") (pinfunction "D4_12") (pintype "passive"))
    )
    (net (code "79") (name "/INT76") (class "Default")
      (node (ref "SV5") (pin "35") (pinfunction "35_35") (pintype "passive"))
      (node (ref "U20") (pin "13") (pinfunction "D5_13") (pintype "passive"))
    )
    (net (code "80") (name "/INT77") (class "Default")
      (node (ref "SV5") (pin "36") (pinfunction "36_36") (pintype "passive"))
      (node (ref "U20") (pin "15") (pinfunction "D6_15") (pintype "passive"))
    )
    (net (code "81") (name "/INT78") (class "Default")
      (node (ref "SV5") (pin "38") (pinfunction "38_38") (pintype "passive"))
      (node (ref "U20") (pin "17") (pinfunction "D7_17") (pintype "passive"))
    )
    (net (code "82") (name "/INT79") (class "Default")
      (node (ref "SV6") (pin "5") (pinfunction "5_5") (pintype "passive"))
      (node (ref "U20") (pin "19") (pinfunction "D8_19") (pintype "passive"))
    )
    (net (code "83") (name "/INT80") (class "Default")
      (node (ref "SV8") (pin "24") (pinfunction "24_24") (pintype "passive"))
      (node (ref "U39") (pin "6") (pinfunction "D1_6") (pintype "passive"))
    )
    (net (code "84") (name "/INT81") (class "Default")
      (node (ref "SV8") (pin "29") (pinfunction "29_29") (pintype "passive"))
      (node (ref "U39") (pin "8") (pinfunction "D2_8") (pintype "passive"))
    )
    (net (code "85") (name "/INT82") (class "Default")
      (node (ref "SV8") (pin "30") (pinfunction "30_30") (pintype "passive"))
      (node (ref "U39") (pin "10") (pinfunction "D3_10") (pintype "passive"))
    )
    (net (code "86") (name "/INT83") (class "Default")
      (node (ref "SV8") (pin "35") (pinfunction "35_35") (pintype "passive"))
      (node (ref "U39") (pin "12") (pinfunction "D4_12") (pintype "passive"))
    )
    (net (code "87") (name "/INT84") (class "Default")
      (node (ref "SV8") (pin "36") (pinfunction "36_36") (pintype "passive"))
      (node (ref "U39") (pin "13") (pinfunction "D5_13") (pintype "passive"))
    )
    (net (code "88") (name "/INT85") (class "Default")
      (node (ref "SV8") (pin "38") (pinfunction "38_38") (pintype "passive"))
      (node (ref "U39") (pin "15") (pinfunction "D6_15") (pintype "passive"))
    )
    (net (code "89") (name "/INT86") (class "Default")
      (node (ref "SV9") (pin "5") (pinfunction "5_5") (pintype "passive"))
      (node (ref "U39") (pin "17") (pinfunction "D7_17") (pintype "passive"))
    )
    (net (code "90") (name "/INT87") (class "Default")
      (node (ref "SV9") (pin "6") (pinfunction "6_6") (pintype "passive"))
      (node (ref "U39") (pin "19") (pinfunction "D8_19") (pintype "passive"))
    )
    (net (code "91") (name "/INT88") (class "Default")
      (node (ref "SV9") (pin "11") (pinfunction "11_11") (pintype "passive"))
      (node (ref "U41") (pin "6") (pinfunction "D1_6") (pintype "passive"))
    )
    (net (code "92") (name "/INT89") (class "Default")
      (node (ref "SV9") (pin "12") (pinfunction "12_12") (pintype "passive"))
      (node (ref "U41") (pin "8") (pinfunction "D2_8") (pintype "passive"))
    )
    (net (code "93") (name "/INT90") (class "Default")
      (node (ref "SV9") (pin "17") (pinfunction "17_17") (pintype "passive"))
      (node (ref "U41") (pin "10") (pinfunction "D3_10") (pintype "passive"))
    )
    (net (code "94") (name "/INT91") (class "Default")
      (node (ref "SV9") (pin "18") (pinfunction "18_18") (pintype "passive"))
      (node (ref "U41") (pin "12") (pinfunction "D4_12") (pintype "passive"))
    )
    (net (code "95") (name "/INT92") (class "Default")
      (node (ref "SV9") (pin "23") (pinfunction "23_23") (pintype "passive"))
      (node (ref "U41") (pin "13") (pinfunction "D5_13") (pintype "passive"))
    )
    (net (code "96") (name "/INT93") (class "Default")
      (node (ref "SV9") (pin "24") (pinfunction "24_24") (pintype "passive"))
      (node (ref "U41") (pin "15") (pinfunction "D6_15") (pintype "passive"))
    )
    (net (code "97") (name "/INT94") (class "Default")
      (node (ref "SV9") (pin "29") (pinfunction "29_29") (pintype "passive"))
      (node (ref "U41") (pin "17") (pinfunction "D7_17") (pintype "passive"))
    )
    (net (code "98") (name "/INT95") (class "Default")
      (node (ref "SV9") (pin "30") (pinfunction "30_30") (pintype "passive"))
      (node (ref "U41") (pin "19") (pinfunction "D8_19") (pintype "passive"))
    )
    (net (code "99") (name "/INT_H") (class "Default")
      (node (ref "R163") (pin "2") (pinfunction "2_2") (pintype "passive"))
      (node (ref "U$1") (pin "51") (pinfunction "P_3.0_51") (pintype "bidirectional"))
      (node (ref "U56") (pin "16") (pinfunction "B3_16") (pintype "passive"))
    )
    (net (code "100") (name "/INT_L") (class "Default")
      (node (ref "R158") (pin "2") (pinfunction "2_2") (pintype "passive"))
      (node (ref "U54") (pin "6") (pinfunction "D1_6") (pintype "passive"))
      (node (ref "U56") (pin "5") (pinfunction "A3_5") (pintype "passive"))
    )
    (net (code "101") (name "/INT_MP0") (class "Default")
      (node (ref "TP6") (pin "TP") (pinfunction "TP_TP") (pintype "input"))
      (node (ref "U4") (pin "11") (pinfunction "S4_11") (pintype "passive"))
      (node (ref "U4") (pin "5") (pinfunction "S1_5") (pintype "passive"))
      (node (ref "U4") (pin "7") (pinfunction "S2_7") (pintype "passive"))
      (node (ref "U4") (pin "9") (pinfunction "S3_9") (pintype "passive"))
      (node (ref "U54") (pin "5") (pinfunction "S1_5") (pintype "passive"))
      (node (ref "U54") (pin "7") (pinfunction "S2_7") (pintype "passive"))
      (node (ref "U58") (pin "5") (pinfunction "S1_5") (pintype "passive"))
    )
    (net (code "102") (name "/INT_MP1") (class "Default")
      (node (ref "TP9") (pin "TP") (pinfunction "TP_TP") (pintype "input"))
      (node (ref "U26") (pin "11") (pinfunction "S4_11") (pintype "passive"))
      (node (ref "U26") (pin "5") (pinfunction "S1_5") (pintype "passive"))
      (node (ref "U26") (pin "7") (pinfunction "S2_7") (pintype "passive"))
      (node (ref "U26") (pin "9") (pinfunction "S3_9") (pintype "passive"))
      (node (ref "U54") (pin "14") (pinfunction "S5_14") (pintype "passive"))
      (node (ref "U58") (pin "11") (pinfunction "S4_11") (pintype "passive"))
    )
    (net (code "103") (name "/INT_MP2") (class "Default")
      (node (ref "TP7") (pin "TP") (pinfunction "TP_TP") (pintype "input"))
      (node (ref "U54") (pin "9") (pinfunction "S3_9") (pintype "passive"))
      (node (ref "U58") (pin "7") (pinfunction "S2_7") (pintype "passive"))
      (node (ref "U8") (pin "11") (pinfunction "S4_11") (pintype "passive"))
      (node (ref "U8") (pin "5") (pinfunction "S1_5") (pintype "passive"))
      (node (ref "U8") (pin "7") (pinfunction "S2_7") (pintype "passive"))
      (node (ref "U8") (pin "9") (pinfunction "S3_9") (pintype "passive"))
    )
    (net (code "104") (name "/INT_MP3") (class "Default")
      (node (ref "TP10") (pin "TP") (pinfunction "TP_TP") (pintype "input"))
      (node (ref "U33") (pin "11") (pinfunction "S4_11") (pintype "passive"))
      (node (ref "U33") (pin "5") (pinfunction "S1_5") (pintype "passive"))
      (node (ref "U33") (pin "7") (pinfunction "S2_7") (pintype "passive"))
      (node (ref "U33") (pin "9") (pinfunction "S3_9") (pintype "passive"))
      (node (ref "U54") (pin "16") (pinfunction "S6_16") (pintype "passive"))
      (node (ref "U58") (pin "14") (pinfunction "S5_14") (pintype "passive"))
    )
    (net (code "105") (name "/INT_MP4") (class "Default")
      (node (ref "TP8") (pin "TP") (pinfunction "TP_TP") (pintype "input"))
      (node (ref "U19") (pin "11") (pinfunction "S4_11") (pintype "passive"))
      (node (ref "U19") (pin "5") (pinfunction "S1_5") (pintype "passive"))
      (node (ref "U19") (pin "7") (pinfunction "S2_7") (pintype "passive"))
      (node (ref "U19") (pin "9") (pinfunction "S3_9") (pintype "passive"))
      (node (ref "U54") (pin "11") (pinfunction "S4_11") (pintype "passive"))
      (node (ref "U58") (pin "9") (pinfunction "S3_9") (pintype "passive"))
    )
    (net (code "106") (name "/INT_MP5") (class "Default")
      (node (ref "TP11") (pin "TP") (pinfunction "TP_TP") (pintype "input"))
      (node (ref "U40") (pin "11") (pinfunction "S4_11") (pintype "passive"))
      (node (ref "U40") (pin "5") (pinfunction "S1_5") (pintype "passive"))
      (node (ref "U40") (pin "7") (pinfunction "S2_7") (pintype "passive"))
      (node (ref "U40") (pin "9") (pinfunction "S3_9") (pintype "passive"))
      (node (ref "U54") (pin "18") (pinfunction "S7_18") (pintype "passive"))
      (node (ref "U58") (pin "16") (pinfunction "S6_16") (pintype "passive"))
    )
    (net (code "107") (name "/SCL") (class "Default")
      (node (ref "R133") (pin "2") (pinfunction "2_2") (pintype "passive"))
      (node (ref "TP21") (pin "TP") (pinfunction "TP_TP") (pintype "input"))
      (node (ref "U13") (pin "11") (pinfunction "2D3_11") (pintype "input"))
      (node (ref "U13") (pin "13") (pinfunction "2D2_13") (pintype "input"))
      (node (ref "U13") (pin "15") (pinfunction "2D1_15") (pintype "input"))
      (node (ref "U13") (pin "17") (pinfunction "2D0_17") (pintype "input"))
      (node (ref "U13") (pin "2") (pinfunction "1D0_2") (pintype "input"))
      (node (ref "U13") (pin "4") (pinfunction "1D1_4") (pintype "input"))
      (node (ref "U13") (pin "6") (pinfunction "1D2_6") (pintype "input"))
      (node (ref "U13") (pin "8") (pinfunction "1D3_8") (pintype "input"))
      (node (ref "U14") (pin "11") (pinfunction "2D3_11") (pintype "input"))
      (node (ref "U14") (pin "13") (pinfunction "2D2_13") (pintype "input"))
      (node (ref "U14") (pin "15") (pinfunction "2D1_15") (pintype "input"))
      (node (ref "U14") (pin "17") (pinfunction "2D0_17") (pintype "input"))
      (node (ref "U14") (pin "2") (pinfunction "1D0_2") (pintype "input"))
      (node (ref "U14") (pin "4") (pinfunction "1D1_4") (pintype "input"))
      (node (ref "U14") (pin "6") (pinfunction "1D2_6") (pintype "input"))
      (node (ref "U14") (pin "8") (pinfunction "1D3_8") (pintype "input"))
      (node (ref "U16") (pin "11") (pinfunction "2D3_11") (pintype "input"))
      (node (ref "U16") (pin "13") (pinfunction "2D2_13") (pintype "input"))
      (node (ref "U16") (pin "15") (pinfunction "2D1_15") (pintype "input"))
      (node (ref "U16") (pin "17") (pinfunction "2D0_17") (pintype "input"))
      (node (ref "U16") (pin "2") (pinfunction "1D0_2") (pintype "input"))
      (node (ref "U16") (pin "4") (pinfunction "1D1_4") (pintype "input"))
      (node (ref "U16") (pin "6") (pinfunction "1D2_6") (pintype "input"))
      (node (ref "U16") (pin "8") (pinfunction "1D3_8") (pintype "input"))
      (node (ref "U17") (pin "11") (pinfunction "2D3_11") (pintype "input"))
      (node (ref "U17") (pin "13") (pinfunction "2D2_13") (pintype "input"))
      (node (ref "U17") (pin "15") (pinfunction "2D1_15") (pintype "input"))
      (node (ref "U17") (pin "17") (pinfunction "2D0_17") (pintype "input"))
      (node (ref "U17") (pin "2") (pinfunction "1D0_2") (pintype "input"))
      (node (ref "U17") (pin "4") (pinfunction "1D1_4") (pintype "input"))
      (node (ref "U17") (pin "6") (pinfunction "1D2_6") (pintype "input"))
      (node (ref "U17") (pin "8") (pinfunction "1D3_8") (pintype "input"))
      (node (ref "U23") (pin "11") (pinfunction "2D3_11") (pintype "input"))
      (node (ref "U23") (pin "13") (pinfunction "2D2_13") (pintype "input"))
      (node (ref "U23") (pin "15") (pinfunction "2D1_15") (pintype "input"))
      (node (ref "U23") (pin "17") (pinfunction "2D0_17") (pintype "input"))
      (node (ref "U23") (pin "2") (pinfunction "1D0_2") (pintype "input"))
      (node (ref "U23") (pin "4") (pinfunction "1D1_4") (pintype "input"))
      (node (ref "U23") (pin "6") (pinfunction "1D2_6") (pintype "input"))
      (node (ref "U23") (pin "8") (pinfunction "1D3_8") (pintype "input"))
      (node (ref "U24") (pin "11") (pinfunction "2D3_11") (pintype "input"))
      (node (ref "U24") (pin "13") (pinfunction "2D2_13") (pintype "input"))
      (node (ref "U24") (pin "15") (pinfunction "2D1_15") (pintype "input"))
      (node (ref "U24") (pin "17") (pinfunction "2D0_17") (pintype "input"))
      (node (ref "U24") (pin "2") (pinfunction "1D0_2") (pintype "input"))
      (node (ref "U24") (pin "4") (pinfunction "1D1_4") (pintype "input"))
      (node (ref "U24") (pin "6") (pinfunction "1D2_6") (pintype "input"))
      (node (ref "U24") (pin "8") (pinfunction "1D3_8") (pintype "input"))
      (node (ref "U30") (pin "11") (pinfunction "2D3_11") (pintype "input"))
      (node (ref "U30") (pin "13") (pinfunction "2D2_13") (pintype "input"))
      (node (ref "U30") (pin "15") (pinfunction "2D1_15") (pintype "input"))
      (node (ref "U30") (pin "17") (pinfunction "2D0_17") (pintype "input"))
      (node (ref "U30") (pin "2") (pinfunction "1D0_2") (pintype "input"))
      (node (ref "U30") (pin "4") (pinfunction "1D1_4") (pintype "input"))
      (node (ref "U30") (pin "6") (pinfunction "1D2_6") (pintype "input"))
      (node (ref "U30") (pin "8") (pinfunction "1D3_8") (pintype "input"))
      (node (ref "U31") (pin "11") (pinfunction "2D3_11") (pintype "input"))
      (node (ref "U31") (pin "13") (pinfunction "2D2_13") (pintype "input"))
      (node (ref "U31") (pin "15") (pinfunction "2D1_15") (pintype "input"))
      (node (ref "U31") (pin "17") (pinfunction "2D0_17") (pintype "input"))
      (node (ref "U31") (pin "2") (pinfunction "1D0_2") (pintype "input"))
      (node (ref "U31") (pin "4") (pinfunction "1D1_4") (pintype "input"))
      (node (ref "U31") (pin "6") (pinfunction "1D2_6") (pintype "input"))
      (node (ref "U31") (pin "8") (pinfunction "1D3_8") (pintype "input"))
      (node (ref "U37") (pin "11") (pinfunction "2D3_11") (pintype "input"))
      (node (ref "U37") (pin "13") (pinfunction "2D2_13") (pintype "input"))
      (node (ref "U37") (pin "15") (pinfunction "2D1_15") (pintype "input"))
      (node (ref "U37") (pin "17") (pinfunction "2D0_17") (pintype "input"))
      (node (ref "U37") (pin "2") (pinfunction "1D0_2") (pintype "input"))
      (node (ref "U37") (pin "4") (pinfunction "1D1_4") (pintype "input"))
      (node (ref "U37") (pin "6") (pinfunction "1D2_6") (pintype "input"))
      (node (ref "U37") (pin "8") (pinfunction "1D3_8") (pintype "input"))
      (node (ref "U38") (pin "11") (pinfunction "2D3_11") (pintype "input"))
      (node (ref "U38") (pin "13") (pinfunction "2D2_13") (pintype "input"))
      (node (ref "U38") (pin "15") (pinfunction "2D1_15") (pintype "input"))
      (node (ref "U38") (pin "17") (pinfunction "2D0_17") (pintype "input"))
      (node (ref "U38") (pin "2") (pinfunction "1D0_2") (pintype "input"))
      (node (ref "U38") (pin "4") (pinfunction "1D1_4") (pintype "input"))
      (node (ref "U38") (pin "6") (pinfunction "1D2_6") (pintype "input"))
      (node (ref "U38") (pin "8") (pinfunction "1D3_8") (pintype "input"))
      (node (ref "U44") (pin "11") (pinfunction "2D3_11") (pintype "input"))
      (node (ref "U44") (pin "13") (pinfunction "2D2_13") (pintype "input"))
      (node (ref "U44") (pin "15") (pinfunction "2D1_15") (pintype "input"))
      (node (ref "U44") (pin "17") (pinfunction "2D0_17") (pintype "input"))
      (node (ref "U44") (pin "2") (pinfunction "1D0_2") (pintype "input"))
      (node (ref "U44") (pin "4") (pinfunction "1D1_4") (pintype "input"))
      (node (ref "U44") (pin "6") (pinfunction "1D2_6") (pintype "input"))
      (node (ref "U44") (pin "8") (pinfunction "1D3_8") (pintype "input"))
      (node (ref "U45") (pin "11") (pinfunction "2D3_11") (pintype "input"))
      (node (ref "U45") (pin "13") (pinfunction "2D2_13") (pintype "input"))
      (node (ref "U45") (pin "15") (pinfunction "2D1_15") (pintype "input"))
      (node (ref "U45") (pin "17") (pinfunction "2D0_17") (pintype "input"))
      (node (ref "U45") (pin "2") (pinfunction "1D0_2") (pintype "input"))
      (node (ref "U45") (pin "4") (pinfunction "1D1_4") (pintype "input"))
      (node (ref "U45") (pin "6") (pinfunction "1D2_6") (pintype "input"))
      (node (ref "U45") (pin "8") (pinfunction "1D3_8") (pintype "input"))
      (node (ref "U47") (pin "7") (pinfunction "SCLB_7") (pintype "bidirectional"))
    )
    (net (code "108") (name "/SCL0") (class "Default")
      (node (ref "SV2") (pin "17") (pinfunction "17_17") (pintype "passive"))
      (node (ref "U13") (pin "18") (pinfunction "~{1O0}_18") (pintype "output"))
    )
    (net (code "109") (name "/SCL1") (class "Default")
      (node (ref "SV2") (pin "18") (pinfunction "18_18") (pintype "passive"))
      (node (ref "U13") (pin "16") (pinfunction "~{1O1}_16") (pintype "output"))
    )
    (net (code "110") (name "/SCL2") (class "Default")
      (node (ref "SV2") (pin "23") (pinfunction "23_23") (pintype "passive"))
      (node (ref "U13") (pin "14") (pinfunction "~{1O2}_14") (pintype "output"))
    )
    (net (code "111") (name "/SCL3") (class "Default")
      (node (ref "SV2") (pin "24") (pinfunction "24_24") (pintype "passive"))
      (node (ref "U13") (pin "12") (pinfunction "~{1O3}_12") (pintype "output"))
    )
    (net (code "112") (name "/SCL4") (class "Default")
      (node (ref "SV2") (pin "29") (pinfunction "29_29") (pintype "passive"))
      (node (ref "U13") (pin "3") (pinfunction "~{2O0}_3") (pintype "output"))
    )
    (net (code "113") (name "/SCL5") (class "Default")
      (node (ref "SV2") (pin "30") (pinfunction "30_30") (pintype "passive"))
      (node (ref "U13") (pin "5") (pinfunction "~{2O1}_5") (pintype "output"))
    )
    (net (code "114") (name "/SCL6") (class "Default")
      (node (ref "SV2") (pin "35") (pinfunction "35_35") (pintype "passive"))
      (node (ref "U13") (pin "7") (pinfunction "~{2O2}_7") (pintype "output"))
    )
    (net (code "115") (name "/SCL7") (class "Default")
      (node (ref "SV2") (pin "36") (pinfunction "36_36") (pintype "passive"))
      (node (ref "U13") (pin "9") (pinfunction "~{2O3}_9") (pintype "output"))
    )
    (net (code "116") (name "/SCL8") (class "Default")
      (node (ref "SV3") (pin "1") (pinfunction "1_1") (pintype "passive"))
      (node (ref "U14") (pin "18") (pinfunction "~{1O0}_18") (pintype "output"))
    )
    (net (code "117") (name "/SCL9") (class "Default")
      (node (ref "SV3") (pin "2") (pinfunction "2_2") (pintype "passive"))
      (node (ref "U14") (pin "16") (pinfunction "~{1O1}_16") (pintype "output"))
    )
    (net (code "118") (name "/SCL10") (class "Default")
      (node (ref "SV3") (pin "7") (pinfunction "7_7") (pintype "passive"))
      (node (ref "U14") (pin "14") (pinfunction "~{1O2}_14") (pintype "output"))
    )
    (net (code "119") (name "/SCL11") (class "Default")
      (node (ref "SV3") (pin "8") (pinfunction "8_8") (pintype "passive"))
      (node (ref "U14") (pin "12") (pinfunction "~{1O3}_12") (pintype "output"))
    )
    (net (code "120") (name "/SCL12") (class "Default")
      (node (ref "SV3") (pin "13") (pinfunction "13_13") (pintype "passive"))
      (node (ref "U14") (pin "3") (pinfunction "~{2O0}_3") (pintype "output"))
    )
    (net (code "121") (name "/SCL13") (class "Default")
      (node (ref "SV3") (pin "14") (pinfunction "14_14") (pintype "passive"))
      (node (ref "U14") (pin "5") (pinfunction "~{2O1}_5") (pintype "output"))
    )
    (net (code "122") (name "/SCL14") (class "Default")
      (node (ref "SV3") (pin "19") (pinfunction "19_19") (pintype "passive"))
      (node (ref "U14") (pin "7") (pinfunction "~{2O2}_7") (pintype "output"))
    )
    (net (code "123") (name "/SCL15") (class "Default")
      (node (ref "SV3") (pin "20") (pinfunction "20_20") (pintype "passive"))
      (node (ref "U14") (pin "9") (pinfunction "~{2O3}_9") (pintype "output"))
    )
    (net (code "124") (name "/SCL16") (class "Default")
      (node (ref "SV6") (pin "2") (pinfunction "2_2") (pintype "passive"))
      (node (ref "U30") (pin "18") (pinfunction "~{1O0}_18") (pintype "output"))
    )
    (net (code "125") (name "/SCL17") (class "Default")
      (node (ref "SV6") (pin "7") (pinfunction "7_7") (pintype "passive"))
      (node (ref "U30") (pin "16") (pinfunction "~{1O1}_16") (pintype "output"))
    )
    (net (code "126") (name "/SCL18") (class "Default")
      (node (ref "SV6") (pin "8") (pinfunction "8_8") (pintype "passive"))
      (node (ref "U30") (pin "14") (pinfunction "~{1O2}_14") (pintype "output"))
    )
    (net (code "127") (name "/SCL19") (class "Default")
      (node (ref "SV6") (pin "13") (pinfunction "13_13") (pintype "passive"))
      (node (ref "U30") (pin "12") (pinfunction "~{1O3}_12") (pintype "output"))
    )
    (net (code "128") (name "/SCL20") (class "Default")
      (node (ref "SV6") (pin "14") (pinfunction "14_14") (pintype "passive"))
      (node (ref "U30") (pin "3") (pinfunction "~{2O0}_3") (pintype "output"))
    )
    (net (code "129") (name "/SCL21") (class "Default")
      (node (ref "SV6") (pin "19") (pinfunction "19_19") (pintype "passive"))
      (node (ref "U30") (pin "5") (pinfunction "~{2O1}_5") (pintype "output"))
    )
    (net (code "130") (name "/SCL22") (class "Default")
      (node (ref "SV6") (pin "20") (pinfunction "20_20") (pintype "passive"))
      (node (ref "U30") (pin "7") (pinfunction "~{2O2}_7") (pintype "output"))
    )
    (net (code "131") (name "/SCL23") (class "Default")
      (node (ref "SV6") (pin "25") (pinfunction "25_25") (pintype "passive"))
      (node (ref "U30") (pin "9") (pinfunction "~{2O3}_9") (pintype "output"))
    )
    (net (code "132") (name "/SCL24") (class "Default")
      (node (ref "SV6") (pin "26") (pinfunction "26_26") (pintype "passive"))
      (node (ref "U31") (pin "18") (pinfunction "~{1O0}_18") (pintype "output"))
    )
    (net (code "133") (name "/SCL25") (class "Default")
      (node (ref "SV6") (pin "31") (pinfunction "31_31") (pintype "passive"))
      (node (ref "U31") (pin "16") (pinfunction "~{1O1}_16") (pintype "output"))
    )
    (net (code "134") (name "/SCL26") (class "Default")
      (node (ref "SV6") (pin "32") (pinfunction "32_32") (pintype "passive"))
      (node (ref "U31") (pin "14") (pinfunction "~{1O2}_14") (pintype "output"))
    )
    (net (code "135") (name "/SCL27") (class "Default")
      (node (ref "SV6") (pin "37") (pinfunction "37_37") (pintype "passive"))
      (node (ref "U31") (pin "12") (pinfunction "~{1O3}_12") (pintype "output"))
    )
    (net (code "136") (name "/SCL28") (class "Default")
      (node (ref "SV7") (pin "1") (pinfunction "1_1") (pintype "passive"))
      (node (ref "U31") (pin "3") (pinfunction "~{2O0}_3") (pintype "output"))
    )
    (net (code "137") (name "/SCL29") (class "Default")
      (node (ref "SV7") (pin "2") (pinfunction "2_2") (pintype "passive"))
      (node (ref "U31") (pin "5") (pinfunction "~{2O1}_5") (pintype "output"))
    )
    (net (code "138") (name "/SCL30") (class "Default")
      (node (ref "SV7") (pin "7") (pinfunction "7_7") (pintype "passive"))
      (node (ref "U31") (pin "7") (pinfunction "~{2O2}_7") (pintype "output"))
    )
    (net (code "139") (name "/SCL31") (class "Default")
      (node (ref "SV7") (pin "8") (pinfunction "8_8") (pintype "passive"))
      (node (ref "U31") (pin "9") (pinfunction "~{2O3}_9") (pintype "output"))
    )
    (net (code "140") (name "/SCL32") (class "Default")
      (node (ref "SV3") (pin "25") (pinfunction "25_25") (pintype "passive"))
      (node (ref "U16") (pin "18") (pinfunction "~{1O0}_18") (pintype "output"))
    )
    (net (code "141") (name "/SCL33") (class "Default")
      (node (ref "SV3") (pin "26") (pinfunction "26_26") (pintype "passive"))
      (node (ref "U16") (pin "16") (pinfunction "~{1O1}_16") (pintype "output"))
    )
    (net (code "142") (name "/SCL34") (class "Default")
      (node (ref "SV3") (pin "31") (pinfunction "31_31") (pintype "passive"))
      (node (ref "U16") (pin "14") (pinfunction "~{1O2}_14") (pintype "output"))
    )
    (net (code "143") (name "/SCL35") (class "Default")
      (node (ref "SV3") (pin "32") (pinfunction "32_32") (pintype "passive"))
      (node (ref "U16") (pin "12") (pinfunction "~{1O3}_12") (pintype "output"))
    )
    (net (code "144") (name "/SCL36") (class "Default")
      (node (ref "SV3") (pin "37") (pinfunction "37_37") (pintype "passive"))
      (node (ref "U16") (pin "3") (pinfunction "~{2O0}_3") (pintype "output"))
    )
    (net (code "145") (name "/SCL37") (class "Default")
      (node (ref "SV4") (pin "1") (pinfunction "1_1") (pintype "passive"))
      (node (ref "U16") (pin "5") (pinfunction "~{2O1}_5") (pintype "output"))
    )
    (net (code "146") (name "/SCL38") (class "Default")
      (node (ref "SV4") (pin "2") (pinfunction "2_2") (pintype "passive"))
      (node (ref "U16") (pin "7") (pinfunction "~{2O2}_7") (pintype "output"))
    )
    (net (code "147") (name "/SCL39") (class "Default")
      (node (ref "SV4") (pin "7") (pinfunction "7_7") (pintype "passive"))
      (node (ref "U16") (pin "9") (pinfunction "~{2O3}_9") (pintype "output"))
    )
    (net (code "148") (name "/SCL40") (class "Default")
      (node (ref "SV4") (pin "8") (pinfunction "8_8") (pintype "passive"))
      (node (ref "U17") (pin "18") (pinfunction "~{1O0}_18") (pintype "output"))
    )
    (net (code "149") (name "/SCL41") (class "Default")
      (node (ref "SV4") (pin "13") (pinfunction "13_13") (pintype "passive"))
      (node (ref "U17") (pin "16") (pinfunction "~{1O1}_16") (pintype "output"))
    )
    (net (code "150") (name "/SCL42") (class "Default")
      (node (ref "SV4") (pin "14") (pinfunction "14_14") (pintype "passive"))
      (node (ref "U17") (pin "14") (pinfunction "~{1O2}_14") (pintype "output"))
    )
    (net (code "151") (name "/SCL43") (class "Default")
      (node (ref "SV4") (pin "19") (pinfunction "19_19") (pintype "passive"))
      (node (ref "U17") (pin "12") (pinfunction "~{1O3}_12") (pintype "output"))
    )
    (net (code "152") (name "/SCL44") (class "Default")
      (node (ref "SV4") (pin "20") (pinfunction "20_20") (pintype "passive"))
      (node (ref "U17") (pin "3") (pinfunction "~{2O0}_3") (pintype "output"))
    )
    (net (code "153") (name "/SCL45") (class "Default")
      (node (ref "SV4") (pin "25") (pinfunction "25_25") (pintype "passive"))
      (node (ref "U17") (pin "5") (pinfunction "~{2O1}_5") (pintype "output"))
    )
    (net (code "154") (name "/SCL46") (class "Default")
      (node (ref "SV4") (pin "26") (pinfunction "26_26") (pintype "passive"))
      (node (ref "U17") (pin "7") (pinfunction "~{2O2}_7") (pintype "output"))
    )
    (net (code "155") (name "/SCL47") (class "Default")
      (node (ref "SV4") (pin "31") (pinfunction "31_31") (pintype "passive"))
      (node (ref "U17") (pin "9") (pinfunction "~{2O3}_9") (pintype "output"))
    )
    (net (code "156") (name "/SCL48") (class "Default")
      (node (ref "SV7") (pin "13") (pinfunction "13_13") (pintype "passive"))
      (node (ref "U37") (pin "18") (pinfunction "~{1O0}_18") (pintype "output"))
    )
    (net (code "157") (name "/SCL49") (class "Default")
      (node (ref "SV7") (pin "14") (pinfunction "14_14") (pintype "passive"))
      (node (ref "U37") (pin "16") (pinfunction "~{1O1}_16") (pintype "output"))
    )
    (net (code "158") (name "/SCL50") (class "Default")
      (node (ref "SV7") (pin "19") (pinfunction "19_19") (pintype "passive"))
      (node (ref "U37") (pin "14") (pinfunction "~{1O2}_14") (pintype "output"))
    )
    (net (code "159") (name "/SCL51") (class "Default")
      (node (ref "SV7") (pin "20") (pinfunction "20_20") (pintype "passive"))
      (node (ref "U37") (pin "12") (pinfunction "~{1O3}_12") (pintype "output"))
    )
    (net (code "160") (name "/SCL52") (class "Default")
      (node (ref "SV7") (pin "25") (pinfunction "25_25") (pintype "passive"))
      (node (ref "U37") (pin "3") (pinfunction "~{2O0}_3") (pintype "output"))
    )
    (net (code "161") (name "/SCL53") (class "Default")
      (node (ref "SV7") (pin "26") (pinfunction "26_26") (pintype "passive"))
      (node (ref "U37") (pin "5") (pinfunction "~{2O1}_5") (pintype "output"))
    )
    (net (code "162") (name "/SCL54") (class "Default")
      (node (ref "SV7") (pin "31") (pinfunction "31_31") (pintype "passive"))
      (node (ref "U37") (pin "7") (pinfunction "~{2O2}_7") (pintype "output"))
    )
    (net (code "163") (name "/SCL55") (class "Default")
      (node (ref "SV7") (pin "32") (pinfunction "32_32") (pintype "passive"))
      (node (ref "U37") (pin "9") (pinfunction "~{2O3}_9") (pintype "output"))
    )
    (net (code "164") (name "/SCL56") (class "Default")
      (node (ref "SV7") (pin "37") (pinfunction "37_37") (pintype "passive"))
      (node (ref "U38") (pin "18") (pinfunction "~{1O0}_18") (pintype "output"))
    )
    (net (code "165") (name "/SCL57") (class "Default")
      (node (ref "SV8") (pin "1") (pinfunction "1_1") (pintype "passive"))
      (node (ref "U38") (pin "16") (pinfunction "~{1O1}_16") (pintype "output"))
    )
    (net (code "166") (name "/SCL58") (class "Default")
      (node (ref "SV8") (pin "2") (pinfunction "2_2") (pintype "passive"))
      (node (ref "U38") (pin "14") (pinfunction "~{1O2}_14") (pintype "output"))
    )
    (net (code "167") (name "/SCL59") (class "Default")
      (node (ref "SV8") (pin "7") (pinfunction "7_7") (pintype "passive"))
      (node (ref "U38") (pin "12") (pinfunction "~{1O3}_12") (pintype "output"))
    )
    (net (code "168") (name "/SCL60") (class "Default")
      (node (ref "SV8") (pin "8") (pinfunction "8_8") (pintype "passive"))
      (node (ref "U38") (pin "3") (pinfunction "~{2O0}_3") (pintype "output"))
    )
    (net (code "169") (name "/SCL61") (class "Default")
      (node (ref "SV8") (pin "13") (pinfunction "13_13") (pintype "passive"))
      (node (ref "U38") (pin "5") (pinfunction "~{2O1}_5") (pintype "output"))
    )
    (net (code "170") (name "/SCL62") (class "Default")
      (node (ref "SV8") (pin "14") (pinfunction "14_14") (pintype "passive"))
      (node (ref "U38") (pin "7") (pinfunction "~{2O2}_7") (pintype "output"))
    )
    (net (code "171") (name "/SCL63") (class "Default")
      (node (ref "SV8") (pin "19") (pinfunction "19_19") (pintype "passive"))
      (node (ref "U38") (pin "9") (pinfunction "~{2O3}_9") (pintype "output"))
    )
    (net (code "172") (name "/SCL64") (class "Default")
      (node (ref "SV4") (pin "32") (pinfunction "32_32") (pintype "passive"))
      (node (ref "U23") (pin "18") (pinfunction "~{1O0}_18") (pintype "output"))
    )
    (net (code "173") (name "/SCL65") (class "Default")
      (node (ref "SV4") (pin "37") (pinfunction "37_37") (pintype "passive"))
      (node (ref "U23") (pin "16") (pinfunction "~{1O1}_16") (pintype "output"))
    )
    (net (code "174") (name "/SCL66") (class "Default")
      (node (ref "SV5") (pin "1") (pinfunction "1_1") (pintype "passive"))
      (node (ref "U23") (pin "14") (pinfunction "~{1O2}_14") (pintype "output"))
    )
    (net (code "175") (name "/SCL67") (class "Default")
      (node (ref "SV5") (pin "2") (pinfunction "2_2") (pintype "passive"))
      (node (ref "U23") (pin "12") (pinfunction "~{1O3}_12") (pintype "output"))
    )
    (net (code "176") (name "/SCL68") (class "Default")
      (node (ref "SV5") (pin "7") (pinfunction "7_7") (pintype "passive"))
      (node (ref "U23") (pin "3") (pinfunction "~{2O0}_3") (pintype "output"))
    )
    (net (code "177") (name "/SCL69") (class "Default")
      (node (ref "SV5") (pin "8") (pinfunction "8_8") (pintype "passive"))
      (node (ref "U23") (pin "5") (pinfunction "~{2O1}_5") (pintype "output"))
    )
    (net (code "178") (name "/SCL70") (class "Default")
      (node (ref "SV5") (pin "13") (pinfunction "13_13") (pintype "passive"))
      (node (ref "U23") (pin "7") (pinfunction "~{2O2}_7") (pintype "output"))
    )
    (net (code "179") (name "/SCL71") (class "Default")
      (node (ref "SV5") (pin "14") (pinfunction "14_14") (pintype "passive"))
      (node (ref "U23") (pin "9") (pinfunction "~{2O3}_9") (pintype "output"))
    )
    (net (code "180") (name "/SCL72") (class "Default")
      (node (ref "SV5") (pin "19") (pinfunction "19_19") (pintype "passive"))
      (node (ref "U24") (pin "18") (pinfunction "~{1O0}_18") (pintype "output"))
    )
    (net (code "181") (name "/SCL73") (class "Default")
      (node (ref "SV5") (pin "20") (pinfunction "20_20") (pintype "passive"))
      (node (ref "U24") (pin "16") (pinfunction "~{1O1}_16") (pintype "output"))
    )
    (net (code "182") (name "/SCL74") (class "Default")
      (node (ref "SV5") (pin "25") (pinfunction "25_25") (pintype "passive"))
      (node (ref "U24") (pin "14") (pinfunction "~{1O2}_14") (pintype "output"))
    )
    (net (code "183") (name "/SCL75") (class "Default")
      (node (ref "SV5") (pin "26") (pinfunction "26_26") (pintype "passive"))
      (node (ref "U24") (pin "12") (pinfunction "~{1O3}_12") (pintype "output"))
    )
    (net (code "184") (name "/SCL76") (class "Default")
      (node (ref "SV5") (pin "31") (pinfunction "31_31") (pintype "passive"))
      (node (ref "U24") (pin "3") (pinfunction "~{2O0}_3") (pintype "output"))
    )
    (net (code "185") (name "/SCL77") (class "Default")
      (node (ref "SV5") (pin "32") (pinfunction "32_32") (pintype "passive"))
      (node (ref "U24") (pin "5") (pinfunction "~{2O1}_5") (pintype "output"))
    )
    (net (code "186") (name "/SCL78") (class "Default")
      (node (ref "SV5") (pin "37") (pinfunction "37_37") (pintype "passive"))
      (node (ref "U24") (pin "7") (pinfunction "~{2O2}_7") (pintype "output"))
    )
    (net (code "187") (name "/SCL79") (class "Default")
      (node (ref "SV6") (pin "1") (pinfunction "1_1") (pintype "passive"))
      (node (ref "U24") (pin "9") (pinfunction "~{2O3}_9") (pintype "output"))
    )
    (net (code "188") (name "/SCL80") (class "Default")
      (node (ref "SV8") (pin "20") (pinfunction "20_20") (pintype "passive"))
      (node (ref "U44") (pin "18") (pinfunction "~{1O0}_18") (pintype "output"))
    )
    (net (code "189") (name "/SCL81") (class "Default")
      (node (ref "SV8") (pin "25") (pinfunction "25_25") (pintype "passive"))
      (node (ref "U44") (pin "16") (pinfunction "~{1O1}_16") (pintype "output"))
    )
    (net (code "190") (name "/SCL82") (class "Default")
      (node (ref "SV8") (pin "26") (pinfunction "26_26") (pintype "passive"))
      (node (ref "U44") (pin "14") (pinfunction "~{1O2}_14") (pintype "output"))
    )
    (net (code "191") (name "/SCL83") (class "Default")
      (node (ref "SV8") (pin "31") (pinfunction "31_31") (pintype "passive"))
      (node (ref "U44") (pin "12") (pinfunction "~{1O3}_12") (pintype "output"))
    )
    (net (code "192") (name "/SCL84") (class "Default")
      (node (ref "SV8") (pin "32") (pinfunction "32_32") (pintype "passive"))
      (node (ref "U44") (pin "3") (pinfunction "~{2O0}_3") (pintype "output"))
    )
    (net (code "193") (name "/SCL85") (class "Default")
      (node (ref "SV8") (pin "37") (pinfunction "37_37") (pintype "passive"))
      (node (ref "U44") (pin "5") (pinfunction "~{2O1}_5") (pintype "output"))
    )
    (net (code "194") (name "/SCL86") (class "Default")
      (node (ref "SV9") (pin "1") (pinfunction "1_1") (pintype "passive"))
      (node (ref "U44") (pin "7") (pinfunction "~{2O2}_7") (pintype "output"))
    )
    (net (code "195") (name "/SCL87") (class "Default")
      (node (ref "SV9") (pin "2") (pinfunction "2_2") (pintype "passive"))
      (node (ref "U44") (pin "9") (pinfunction "~{2O3}_9") (pintype "output"))
    )
    (net (code "196") (name "/SCL88") (class "Default")
      (node (ref "SV9") (pin "7") (pinfunction "7_7") (pintype "passive"))
      (node (ref "U45") (pin "18") (pinfunction "~{1O0}_18") (pintype "output"))
    )
    (net (code "197") (name "/SCL89") (class "Default")
      (node (ref "SV9") (pin "8") (pinfunction "8_8") (pintype "passive"))
      (node (ref "U45") (pin "16") (pinfunction "~{1O1}_16") (pintype "output"))
    )
    (net (code "198") (name "/SCL90") (class "Default")
      (node (ref "SV9") (pin "13") (pinfunction "13_13") (pintype "passive"))
      (node (ref "U45") (pin "14") (pinfunction "~{1O2}_14") (pintype "output"))
    )
    (net (code "199") (name "/SCL91") (class "Default")
      (node (ref "SV9") (pin "14") (pinfunction "14_14") (pintype "passive"))
      (node (ref "U45") (pin "12") (pinfunction "~{1O3}_12") (pintype "output"))
    )
    (net (code "200") (name "/SCL92") (class "Default")
      (node (ref "SV9") (pin "19") (pinfunction "19_19") (pintype "passive"))
      (node (ref "U45") (pin "3") (pinfunction "~{2O0}_3") (pintype "output"))
    )
    (net (code "201") (name "/SCL93") (class "Default")
      (node (ref "SV9") (pin "20") (pinfunction "20_20") (pintype "passive"))
      (node (ref "U45") (pin "5") (pinfunction "~{2O1}_5") (pintype "output"))
    )
    (net (code "202") (name "/SCL94") (class "Default")
      (node (ref "SV9") (pin "25") (pinfunction "25_25") (pintype "passive"))
      (node (ref "U45") (pin "7") (pinfunction "~{2O2}_7") (pintype "output"))
    )
    (net (code "203") (name "/SCL95") (class "Default")
      (node (ref "SV9") (pin "26") (pinfunction "26_26") (pintype "passive"))
      (node (ref "U45") (pin "9") (pinfunction "~{2O3}_9") (pintype "output"))
    )
    (net (code "204") (name "/SCL_A") (class "Default")
      (node (ref "R159") (pin "2") (pinfunction "2_2") (pintype "passive"))
      (node (ref "TP23") (pin "TP") (pinfunction "TP_TP") (pintype "input"))
      (node (ref "U47") (pin "2") (pinfunction "SCLA_2") (pintype "bidirectional"))
      (node (ref "U56") (pin "4") (pinfunction "A2_4") (pintype "passive"))
    )
    (net (code "205") (name "/SCL_H") (class "Default")
      (node (ref "R156") (pin "2") (pinfunction "2_2") (pintype "passive"))
      (node (ref "TP2") (pin "TP") (pinfunction "TP_TP") (pintype "input"))
      (node (ref "U$1") (pin "14") (pinfunction "P_12.2_14") (pintype "bidirectional"))
      (node (ref "U3") (pin "5") (pinfunction "SCL_5") (pintype "input"))
      (node (ref "U54") (pin "1") (pinfunction "SCL_1") (pintype "passive"))
      (node (ref "U58") (pin "1") (pinfunction "SCL_1") (pintype "passive"))
    )
    (net (code "206") (name "/SDA0") (class "Default")
      (node (ref "R19") (pin "2") (pinfunction "2_2") (pintype "passive"))
      (node (ref "SV2") (pin "19") (pinfunction "19_19") (pintype "passive"))
      (node (ref "U9") (pin "6") (pinfunction "D1_6") (pintype "passive"))
    )
    (net (code "207") (name "/SDA1") (class "Default")
      (node (ref "R18") (pin "2") (pinfunction "2_2") (pintype "passive"))
      (node (ref "SV2") (pin "20") (pinfunction "20_20") (pintype "passive"))
      (node (ref "U9") (pin "8") (pinfunction "D2_8") (pintype "passive"))
    )
    (net (code "208") (name "/SDA2") (class "Default")
      (node (ref "R17") (pin "2") (pinfunction "2_2") (pintype "passive"))
      (node (ref "SV2") (pin "25") (pinfunction "25_25") (pintype "passive"))
      (node (ref "U9") (pin "10") (pinfunction "D3_10") (pintype "passive"))
    )
    (net (code "209") (name "/SDA3") (class "Default")
      (node (ref "R16") (pin "2") (pinfunction "2_2") (pintype "passive"))
      (node (ref "SV2") (pin "26") (pinfunction "26_26") (pintype "passive"))
      (node (ref "U9") (pin "12") (pinfunction "D4_12") (pintype "passive"))
    )
    (net (code "210") (name "/SDA4") (class "Default")
      (node (ref "R15") (pin "2") (pinfunction "2_2") (pintype "passive"))
      (node (ref "SV2") (pin "31") (pinfunction "31_31") (pintype "passive"))
      (node (ref "U9") (pin "13") (pinfunction "D5_13") (pintype "passive"))
    )
    (net (code "211") (name "/SDA5") (class "Default")
      (node (ref "R14") (pin "2") (pinfunction "2_2") (pintype "passive"))
      (node (ref "SV2") (pin "32") (pinfunction "32_32") (pintype "passive"))
      (node (ref "U9") (pin "15") (pinfunction "D6_15") (pintype "passive"))
    )
    (net (code "212") (name "/SDA6") (class "Default")
      (node (ref "R13") (pin "2") (pinfunction "2_2") (pintype "passive"))
      (node (ref "SV2") (pin "37") (pinfunction "37_37") (pintype "passive"))
      (node (ref "U9") (pin "17") (pinfunction "D7_17") (pintype "passive"))
    )
    (net (code "213") (name "/SDA7") (class "Default")
      (node (ref "R12") (pin "2") (pinfunction "2_2") (pintype "passive"))
      (node (ref "SV2") (pin "38") (pinfunction "38_38") (pintype "passive"))
      (node (ref "U9") (pin "19") (pinfunction "D8_19") (pintype "passive"))
    )
    (net (code "214") (name "/SDA8") (class "Default")
      (node (ref "R27") (pin "2") (pinfunction "2_2") (pintype "passive"))
      (node (ref "SV3") (pin "3") (pinfunction "3_3") (pintype "passive"))
      (node (ref "U10") (pin "6") (pinfunction "D1_6") (pintype "passive"))
    )
    (net (code "215") (name "/SDA9") (class "Default")
      (node (ref "R26") (pin "2") (pinfunction "2_2") (pintype "passive"))
      (node (ref "SV3") (pin "4") (pinfunction "4_4") (pintype "passive"))
      (node (ref "U10") (pin "8") (pinfunction "D2_8") (pintype "passive"))
    )
    (net (code "216") (name "/SDA10") (class "Default")
      (node (ref "R25") (pin "2") (pinfunction "2_2") (pintype "passive"))
      (node (ref "SV3") (pin "9") (pinfunction "9_9") (pintype "passive"))
      (node (ref "U10") (pin "10") (pinfunction "D3_10") (pintype "passive"))
    )
    (net (code "217") (name "/SDA11") (class "Default")
      (node (ref "R24") (pin "2") (pinfunction "2_2") (pintype "passive"))
      (node (ref "SV3") (pin "10") (pinfunction "10_10") (pintype "passive"))
      (node (ref "U10") (pin "12") (pinfunction "D4_12") (pintype "passive"))
    )
    (net (code "218") (name "/SDA12") (class "Default")
      (node (ref "R23") (pin "2") (pinfunction "2_2") (pintype "passive"))
      (node (ref "SV3") (pin "15") (pinfunction "15_15") (pintype "passive"))
      (node (ref "U10") (pin "13") (pinfunction "D5_13") (pintype "passive"))
    )
    (net (code "219") (name "/SDA13") (class "Default")
      (node (ref "R22") (pin "2") (pinfunction "2_2") (pintype "passive"))
      (node (ref "SV3") (pin "16") (pinfunction "16_16") (pintype "passive"))
      (node (ref "U10") (pin "15") (pinfunction "D6_15") (pintype "passive"))
    )
    (net (code "220") (name "/SDA14") (class "Default")
      (node (ref "R21") (pin "2") (pinfunction "2_2") (pintype "passive"))
      (node (ref "SV3") (pin "21") (pinfunction "21_21") (pintype "passive"))
      (node (ref "U10") (pin "17") (pinfunction "D7_17") (pintype "passive"))
    )
    (net (code "221") (name "/SDA15") (class "Default")
      (node (ref "R20") (pin "2") (pinfunction "2_2") (pintype "passive"))
      (node (ref "SV3") (pin "22") (pinfunction "22_22") (pintype "passive"))
      (node (ref "U10") (pin "19") (pinfunction "D8_19") (pintype "passive"))
    )
    (net (code "222") (name "/SDA16") (class "Default")
      (node (ref "R77") (pin "2") (pinfunction "2_2") (pintype "passive"))
      (node (ref "SV6") (pin "4") (pinfunction "4_4") (pintype "passive"))
      (node (ref "U28") (pin "6") (pinfunction "D1_6") (pintype "passive"))
    )
    (net (code "223") (name "/SDA17") (class "Default")
      (node (ref "R76") (pin "2") (pinfunction "2_2") (pintype "passive"))
      (node (ref "SV6") (pin "9") (pinfunction "9_9") (pintype "passive"))
      (node (ref "U28") (pin "8") (pinfunction "D2_8") (pintype "passive"))
    )
    (net (code "224") (name "/SDA18") (class "Default")
      (node (ref "R75") (pin "2") (pinfunction "2_2") (pintype "passive"))
      (node (ref "SV6") (pin "10") (pinfunction "10_10") (pintype "passive"))
      (node (ref "U28") (pin "10") (pinfunction "D3_10") (pintype "passive"))
    )
    (net (code "225") (name "/SDA19") (class "Default")
      (node (ref "R74") (pin "2") (pinfunction "2_2") (pintype "passive"))
      (node (ref "SV6") (pin "15") (pinfunction "15_15") (pintype "passive"))
      (node (ref "U28") (pin "12") (pinfunction "D4_12") (pintype "passive"))
    )
    (net (code "226") (name "/SDA20") (class "Default")
      (node (ref "R73") (pin "2") (pinfunction "2_2") (pintype "passive"))
      (node (ref "SV6") (pin "16") (pinfunction "16_16") (pintype "passive"))
      (node (ref "U28") (pin "13") (pinfunction "D5_13") (pintype "passive"))
    )
    (net (code "227") (name "/SDA21") (class "Default")
      (node (ref "R72") (pin "2") (pinfunction "2_2") (pintype "passive"))
      (node (ref "SV6") (pin "21") (pinfunction "21_21") (pintype "passive"))
      (node (ref "U28") (pin "15") (pinfunction "D6_15") (pintype "passive"))
    )
    (net (code "228") (name "/SDA22") (class "Default")
      (node (ref "R71") (pin "2") (pinfunction "2_2") (pintype "passive"))
      (node (ref "SV6") (pin "22") (pinfunction "22_22") (pintype "passive"))
      (node (ref "U28") (pin "17") (pinfunction "D7_17") (pintype "passive"))
    )
    (net (code "229") (name "/SDA23") (class "Default")
      (node (ref "R70") (pin "2") (pinfunction "2_2") (pintype "passive"))
      (node (ref "SV6") (pin "27") (pinfunction "27_27") (pintype "passive"))
      (node (ref "U28") (pin "19") (pinfunction "D8_19") (pintype "passive"))
    )
    (net (code "230") (name "/SDA24") (class "Default")
      (node (ref "R85") (pin "2") (pinfunction "2_2") (pintype "passive"))
      (node (ref "SV6") (pin "28") (pinfunction "28_28") (pintype "passive"))
      (node (ref "U29") (pin "6") (pinfunction "D1_6") (pintype "passive"))
    )
    (net (code "231") (name "/SDA25") (class "Default")
      (node (ref "R84") (pin "2") (pinfunction "2_2") (pintype "passive"))
      (node (ref "SV6") (pin "33") (pinfunction "33_33") (pintype "passive"))
      (node (ref "U29") (pin "8") (pinfunction "D2_8") (pintype "passive"))
    )
    (net (code "232") (name "/SDA26") (class "Default")
      (node (ref "R83") (pin "2") (pinfunction "2_2") (pintype "passive"))
      (node (ref "SV6") (pin "34") (pinfunction "34_34") (pintype "passive"))
      (node (ref "U29") (pin "10") (pinfunction "D3_10") (pintype "passive"))
    )
    (net (code "233") (name "/SDA27") (class "Default")
      (node (ref "R82") (pin "2") (pinfunction "2_2") (pintype "passive"))
      (node (ref "SV6") (pin "39") (pinfunction "39_39") (pintype "passive"))
      (node (ref "U29") (pin "12") (pinfunction "D4_12") (pintype "passive"))
    )
    (net (code "234") (name "/SDA28") (class "Default")
      (node (ref "R81") (pin "2") (pinfunction "2_2") (pintype "passive"))
      (node (ref "SV7") (pin "3") (pinfunction "3_3") (pintype "passive"))
      (node (ref "U29") (pin "13") (pinfunction "D5_13") (pintype "passive"))
    )
    (net (code "235") (name "/SDA29") (class "Default")
      (node (ref "R80") (pin "2") (pinfunction "2_2") (pintype "passive"))
      (node (ref "SV7") (pin "4") (pinfunction "4_4") (pintype "passive"))
      (node (ref "U29") (pin "15") (pinfunction "D6_15") (pintype "passive"))
    )
    (net (code "236") (name "/SDA30") (class "Default")
      (node (ref "R79") (pin "2") (pinfunction "2_2") (pintype "passive"))
      (node (ref "SV7") (pin "9") (pinfunction "9_9") (pintype "passive"))
      (node (ref "U29") (pin "17") (pinfunction "D7_17") (pintype "passive"))
    )
    (net (code "237") (name "/SDA31") (class "Default")
      (node (ref "R78") (pin "2") (pinfunction "2_2") (pintype "passive"))
      (node (ref "SV7") (pin "10") (pinfunction "10_10") (pintype "passive"))
      (node (ref "U29") (pin "19") (pinfunction "D8_19") (pintype "passive"))
    )
    (net (code "238") (name "/SDA32") (class "Default")
      (node (ref "R35") (pin "2") (pinfunction "2_2") (pintype "passive"))
      (node (ref "SV3") (pin "27") (pinfunction "27_27") (pintype "passive"))
      (node (ref "U12") (pin "6") (pinfunction "D1_6") (pintype "passive"))
    )
    (net (code "239") (name "/SDA33") (class "Default")
      (node (ref "R34") (pin "2") (pinfunction "2_2") (pintype "passive"))
      (node (ref "SV3") (pin "28") (pinfunction "28_28") (pintype "passive"))
      (node (ref "U12") (pin "8") (pinfunction "D2_8") (pintype "passive"))
    )
    (net (code "240") (name "/SDA34") (class "Default")
      (node (ref "R33") (pin "2") (pinfunction "2_2") (pintype "passive"))
      (node (ref "SV3") (pin "33") (pinfunction "33_33") (pintype "passive"))
      (node (ref "U12") (pin "10") (pinfunction "D3_10") (pintype "passive"))
    )
    (net (code "241") (name "/SDA35") (class "Default")
      (node (ref "R32") (pin "2") (pinfunction "2_2") (pintype "passive"))
      (node (ref "SV3") (pin "34") (pinfunction "34_34") (pintype "passive"))
      (node (ref "U12") (pin "12") (pinfunction "D4_12") (pintype "passive"))
    )
    (net (code "242") (name "/SDA36") (class "Default")
      (node (ref "R31") (pin "2") (pinfunction "2_2") (pintype "passive"))
      (node (ref "SV3") (pin "39") (pinfunction "39_39") (pintype "passive"))
      (node (ref "U12") (pin "13") (pinfunction "D5_13") (pintype "passive"))
    )
    (net (code "243") (name "/SDA37") (class "Default")
      (node (ref "R30") (pin "2") (pinfunction "2_2") (pintype "passive"))
      (node (ref "SV4") (pin "3") (pinfunction "3_3") (pintype "passive"))
      (node (ref "U12") (pin "15") (pinfunction "D6_15") (pintype "passive"))
    )
    (net (code "244") (name "/SDA38") (class "Default")
      (node (ref "R29") (pin "2") (pinfunction "2_2") (pintype "passive"))
      (node (ref "SV4") (pin "4") (pinfunction "4_4") (pintype "passive"))
      (node (ref "U12") (pin "17") (pinfunction "D7_17") (pintype "passive"))
    )
    (net (code "245") (name "/SDA39") (class "Default")
      (node (ref "R28") (pin "2") (pinfunction "2_2") (pintype "passive"))
      (node (ref "SV4") (pin "9") (pinfunction "9_9") (pintype "passive"))
      (node (ref "U12") (pin "19") (pinfunction "D8_19") (pintype "passive"))
    )
    (net (code "246") (name "/SDA40") (class "Default")
      (node (ref "R43") (pin "2") (pinfunction "2_2") (pintype "passive"))
      (node (ref "SV4") (pin "10") (pinfunction "10_10") (pintype "passive"))
      (node (ref "U15") (pin "6") (pinfunction "D1_6") (pintype "passive"))
    )
    (net (code "247") (name "/SDA41") (class "Default")
      (node (ref "R42") (pin "2") (pinfunction "2_2") (pintype "passive"))
      (node (ref "SV4") (pin "15") (pinfunction "15_15") (pintype "passive"))
      (node (ref "U15") (pin "8") (pinfunction "D2_8") (pintype "passive"))
    )
    (net (code "248") (name "/SDA42") (class "Default")
      (node (ref "R41") (pin "2") (pinfunction "2_2") (pintype "passive"))
      (node (ref "SV4") (pin "16") (pinfunction "16_16") (pintype "passive"))
      (node (ref "U15") (pin "10") (pinfunction "D3_10") (pintype "passive"))
    )
    (net (code "249") (name "/SDA43") (class "Default")
      (node (ref "R40") (pin "2") (pinfunction "2_2") (pintype "passive"))
      (node (ref "SV4") (pin "21") (pinfunction "21_21") (pintype "passive"))
      (node (ref "U15") (pin "12") (pinfunction "D4_12") (pintype "passive"))
    )
    (net (code "250") (name "/SDA44") (class "Default")
      (node (ref "R39") (pin "2") (pinfunction "2_2") (pintype "passive"))
      (node (ref "SV4") (pin "22") (pinfunction "22_22") (pintype "passive"))
      (node (ref "U15") (pin "13") (pinfunction "D5_13") (pintype "passive"))
    )
    (net (code "251") (name "/SDA45") (class "Default")
      (node (ref "R38") (pin "2") (pinfunction "2_2") (pintype "passive"))
      (node (ref "SV4") (pin "27") (pinfunction "27_27") (pintype "passive"))
      (node (ref "U15") (pin "15") (pinfunction "D6_15") (pintype "passive"))
    )
    (net (code "252") (name "/SDA46") (class "Default")
      (node (ref "R37") (pin "2") (pinfunction "2_2") (pintype "passive"))
      (node (ref "SV4") (pin "28") (pinfunction "28_28") (pintype "passive"))
      (node (ref "U15") (pin "17") (pinfunction "D7_17") (pintype "passive"))
    )
    (net (code "253") (name "/SDA47") (class "Default")
      (node (ref "R36") (pin "2") (pinfunction "2_2") (pintype "passive"))
      (node (ref "SV4") (pin "33") (pinfunction "33_33") (pintype "passive"))
      (node (ref "U15") (pin "19") (pinfunction "D8_19") (pintype "passive"))
    )
    (net (code "254") (name "/SDA48") (class "Default")
      (node (ref "R98") (pin "2") (pinfunction "2_2") (pintype "passive"))
      (node (ref "SV7") (pin "15") (pinfunction "15_15") (pintype "passive"))
      (node (ref "U35") (pin "6") (pinfunction "D1_6") (pintype "passive"))
    )
    (net (code "255") (name "/SDA49") (class "Default")
      (node (ref "R97") (pin "2") (pinfunction "2_2") (pintype "passive"))
      (node (ref "SV7") (pin "16") (pinfunction "16_16") (pintype "passive"))
      (node (ref "U35") (pin "8") (pinfunction "D2_8") (pintype "passive"))
    )
    (net (code "256") (name "/SDA50") (class "Default")
      (node (ref "R96") (pin "2") (pinfunction "2_2") (pintype "passive"))
      (node (ref "SV7") (pin "21") (pinfunction "21_21") (pintype "passive"))
      (node (ref "U35") (pin "10") (pinfunction "D3_10") (pintype "passive"))
    )
    (net (code "257") (name "/SDA51") (class "Default")
      (node (ref "R95") (pin "2") (pinfunction "2_2") (pintype "passive"))
      (node (ref "SV7") (pin "22") (pinfunction "22_22") (pintype "passive"))
      (node (ref "U35") (pin "12") (pinfunction "D4_12") (pintype "passive"))
    )
    (net (code "258") (name "/SDA52") (class "Default")
      (node (ref "R94") (pin "2") (pinfunction "2_2") (pintype "passive"))
      (node (ref "SV7") (pin "27") (pinfunction "27_27") (pintype "passive"))
      (node (ref "U35") (pin "13") (pinfunction "D5_13") (pintype "passive"))
    )
    (net (code "259") (name "/SDA53") (class "Default")
      (node (ref "R93") (pin "2") (pinfunction "2_2") (pintype "passive"))
      (node (ref "SV7") (pin "28") (pinfunction "28_28") (pintype "passive"))
      (node (ref "U35") (pin "15") (pinfunction "D6_15") (pintype "passive"))
    )
    (net (code "260") (name "/SDA54") (class "Default")
      (node (ref "R92") (pin "2") (pinfunction "2_2") (pintype "passive"))
      (node (ref "SV7") (pin "33") (pinfunction "33_33") (pintype "passive"))
      (node (ref "U35") (pin "17") (pinfunction "D7_17") (pintype "passive"))
    )
    (net (code "261") (name "/SDA55") (class "Default")
      (node (ref "R91") (pin "2") (pinfunction "2_2") (pintype "passive"))
      (node (ref "SV7") (pin "34") (pinfunction "34_34") (pintype "passive"))
      (node (ref "U35") (pin "19") (pinfunction "D8_19") (pintype "passive"))
    )
    (net (code "262") (name "/SDA56") (class "Default")
      (node (ref "R106") (pin "2") (pinfunction "2_2") (pintype "passive"))
      (node (ref "SV7") (pin "39") (pinfunction "39_39") (pintype "passive"))
      (node (ref "U36") (pin "6") (pinfunction "D1_6") (pintype "passive"))
    )
    (net (code "263") (name "/SDA57") (class "Default")
      (node (ref "R105") (pin "2") (pinfunction "2_2") (pintype "passive"))
      (node (ref "SV8") (pin "3") (pinfunction "3_3") (pintype "passive"))
      (node (ref "U36") (pin "8") (pinfunction "D2_8") (pintype "passive"))
    )
    (net (code "264") (name "/SDA58") (class "Default")
      (node (ref "R104") (pin "2") (pinfunction "2_2") (pintype "passive"))
      (node (ref "SV8") (pin "4") (pinfunction "4_4") (pintype "passive"))
      (node (ref "U36") (pin "10") (pinfunction "D3_10") (pintype "passive"))
    )
    (net (code "265") (name "/SDA59") (class "Default")
      (node (ref "R103") (pin "2") (pinfunction "2_2") (pintype "passive"))
      (node (ref "SV8") (pin "9") (pinfunction "9_9") (pintype "passive"))
      (node (ref "U36") (pin "12") (pinfunction "D4_12") (pintype "passive"))
    )
    (net (code "266") (name "/SDA60") (class "Default")
      (node (ref "R102") (pin "2") (pinfunction "2_2") (pintype "passive"))
      (node (ref "SV8") (pin "10") (pinfunction "10_10") (pintype "passive"))
      (node (ref "U36") (pin "13") (pinfunction "D5_13") (pintype "passive"))
    )
    (net (code "267") (name "/SDA61") (class "Default")
      (node (ref "R101") (pin "2") (pinfunction "2_2") (pintype "passive"))
      (node (ref "SV8") (pin "15") (pinfunction "15_15") (pintype "passive"))
      (node (ref "U36") (pin "15") (pinfunction "D6_15") (pintype "passive"))
    )
    (net (code "268") (name "/SDA62") (class "Default")
      (node (ref "R100") (pin "2") (pinfunction "2_2") (pintype "passive"))
      (node (ref "SV8") (pin "16") (pinfunction "16_16") (pintype "passive"))
      (node (ref "U36") (pin "17") (pinfunction "D7_17") (pintype "passive"))
    )
    (net (code "269") (name "/SDA63") (class "Default")
      (node (ref "R99") (pin "2") (pinfunction "2_2") (pintype "passive"))
      (node (ref "SV8") (pin "21") (pinfunction "21_21") (pintype "passive"))
      (node (ref "U36") (pin "19") (pinfunction "D8_19") (pintype "passive"))
    )
    (net (code "270") (name "/SDA64") (class "Default")
      (node (ref "R56") (pin "2") (pinfunction "2_2") (pintype "passive"))
      (node (ref "SV4") (pin "34") (pinfunction "34_34") (pintype "passive"))
      (node (ref "U21") (pin "6") (pinfunction "D1_6") (pintype "passive"))
    )
    (net (code "271") (name "/SDA65") (class "Default")
      (node (ref "R55") (pin "2") (pinfunction "2_2") (pintype "passive"))
      (node (ref "SV4") (pin "39") (pinfunction "39_39") (pintype "passive"))
      (node (ref "U21") (pin "8") (pinfunction "D2_8") (pintype "passive"))
    )
    (net (code "272") (name "/SDA66") (class "Default")
      (node (ref "R54") (pin "2") (pinfunction "2_2") (pintype "passive"))
      (node (ref "SV5") (pin "3") (pinfunction "3_3") (pintype "passive"))
      (node (ref "U21") (pin "10") (pinfunction "D3_10") (pintype "passive"))
    )
    (net (code "273") (name "/SDA67") (class "Default")
      (node (ref "R53") (pin "2") (pinfunction "2_2") (pintype "passive"))
      (node (ref "SV5") (pin "4") (pinfunction "4_4") (pintype "passive"))
      (node (ref "U21") (pin "12") (pinfunction "D4_12") (pintype "passive"))
    )
    (net (code "274") (name "/SDA68") (class "Default")
      (node (ref "R52") (pin "2") (pinfunction "2_2") (pintype "passive"))
      (node (ref "SV5") (pin "9") (pinfunction "9_9") (pintype "passive"))
      (node (ref "U21") (pin "13") (pinfunction "D5_13") (pintype "passive"))
    )
    (net (code "275") (name "/SDA69") (class "Default")
      (node (ref "R51") (pin "2") (pinfunction "2_2") (pintype "passive"))
      (node (ref "SV5") (pin "10") (pinfunction "10_10") (pintype "passive"))
      (node (ref "U21") (pin "15") (pinfunction "D6_15") (pintype "passive"))
    )
    (net (code "276") (name "/SDA70") (class "Default")
      (node (ref "R50") (pin "2") (pinfunction "2_2") (pintype "passive"))
      (node (ref "SV5") (pin "15") (pinfunction "15_15") (pintype "passive"))
      (node (ref "U21") (pin "17") (pinfunction "D7_17") (pintype "passive"))
    )
    (net (code "277") (name "/SDA71") (class "Default")
      (node (ref "R49") (pin "2") (pinfunction "2_2") (pintype "passive"))
      (node (ref "SV5") (pin "16") (pinfunction "16_16") (pintype "passive"))
      (node (ref "U21") (pin "19") (pinfunction "D8_19") (pintype "passive"))
    )
    (net (code "278") (name "/SDA72") (class "Default")
      (node (ref "R64") (pin "2") (pinfunction "2_2") (pintype "passive"))
      (node (ref "SV5") (pin "21") (pinfunction "21_21") (pintype "passive"))
      (node (ref "U22") (pin "6") (pinfunction "D1_6") (pintype "passive"))
    )
    (net (code "279") (name "/SDA73") (class "Default")
      (node (ref "R63") (pin "2") (pinfunction "2_2") (pintype "passive"))
      (node (ref "SV5") (pin "22") (pinfunction "22_22") (pintype "passive"))
      (node (ref "U22") (pin "8") (pinfunction "D2_8") (pintype "passive"))
    )
    (net (code "280") (name "/SDA74") (class "Default")
      (node (ref "R62") (pin "2") (pinfunction "2_2") (pintype "passive"))
      (node (ref "SV5") (pin "27") (pinfunction "27_27") (pintype "passive"))
      (node (ref "U22") (pin "10") (pinfunction "D3_10") (pintype "passive"))
    )
    (net (code "281") (name "/SDA75") (class "Default")
      (node (ref "R61") (pin "2") (pinfunction "2_2") (pintype "passive"))
      (node (ref "SV5") (pin "28") (pinfunction "28_28") (pintype "passive"))
      (node (ref "U22") (pin "12") (pinfunction "D4_12") (pintype "passive"))
    )
    (net (code "282") (name "/SDA76") (class "Default")
      (node (ref "R60") (pin "2") (pinfunction "2_2") (pintype "passive"))
      (node (ref "SV5") (pin "33") (pinfunction "33_33") (pintype "passive"))
      (node (ref "U22") (pin "13") (pinfunction "D5_13") (pintype "passive"))
    )
    (net (code "283") (name "/SDA77") (class "Default")
      (node (ref "R59") (pin "2") (pinfunction "2_2") (pintype "passive"))
      (node (ref "SV5") (pin "34") (pinfunction "34_34") (pintype "passive"))
      (node (ref "U22") (pin "15") (pinfunction "D6_15") (pintype "passive"))
    )
    (net (code "284") (name "/SDA78") (class "Default")
      (node (ref "R58") (pin "2") (pinfunction "2_2") (pintype "passive"))
      (node (ref "SV5") (pin "39") (pinfunction "39_39") (pintype "passive"))
      (node (ref "U22") (pin "17") (pinfunction "D7_17") (pintype "passive"))
    )
    (net (code "285") (name "/SDA79") (class "Default")
      (node (ref "R57") (pin "2") (pinfunction "2_2") (pintype "passive"))
      (node (ref "SV6") (pin "3") (pinfunction "3_3") (pintype "passive"))
      (node (ref "U22") (pin "19") (pinfunction "D8_19") (pintype "passive"))
    )
    (net (code "286") (name "/SDA80") (class "Default")
      (node (ref "R119") (pin "2") (pinfunction "2_2") (pintype "passive"))
      (node (ref "SV8") (pin "22") (pinfunction "22_22") (pintype "passive"))
      (node (ref "U42") (pin "6") (pinfunction "D1_6") (pintype "passive"))
    )
    (net (code "287") (name "/SDA81") (class "Default")
      (node (ref "R118") (pin "2") (pinfunction "2_2") (pintype "passive"))
      (node (ref "SV8") (pin "27") (pinfunction "27_27") (pintype "passive"))
      (node (ref "U42") (pin "8") (pinfunction "D2_8") (pintype "passive"))
    )
    (net (code "288") (name "/SDA82") (class "Default")
      (node (ref "R117") (pin "2") (pinfunction "2_2") (pintype "passive"))
      (node (ref "SV8") (pin "28") (pinfunction "28_28") (pintype "passive"))
      (node (ref "U42") (pin "10") (pinfunction "D3_10") (pintype "passive"))
    )
    (net (code "289") (name "/SDA83") (class "Default")
      (node (ref "R116") (pin "2") (pinfunction "2_2") (pintype "passive"))
      (node (ref "SV8") (pin "33") (pinfunction "33_33") (pintype "passive"))
      (node (ref "U42") (pin "12") (pinfunction "D4_12") (pintype "passive"))
    )
    (net (code "290") (name "/SDA84") (class "Default")
      (node (ref "R115") (pin "2") (pinfunction "2_2") (pintype "passive"))
      (node (ref "SV8") (pin "34") (pinfunction "34_34") (pintype "passive"))
      (node (ref "U42") (pin "13") (pinfunction "D5_13") (pintype "passive"))
    )
    (net (code "291") (name "/SDA85") (class "Default")
      (node (ref "R114") (pin "2") (pinfunction "2_2") (pintype "passive"))
      (node (ref "SV8") (pin "39") (pinfunction "39_39") (pintype "passive"))
      (node (ref "U42") (pin "15") (pinfunction "D6_15") (pintype "passive"))
    )
    (net (code "292") (name "/SDA86") (class "Default")
      (node (ref "R113") (pin "2") (pinfunction "2_2") (pintype "passive"))
      (node (ref "SV9") (pin "3") (pinfunction "3_3") (pintype "passive"))
      (node (ref "U42") (pin "17") (pinfunction "D7_17") (pintype "passive"))
    )
    (net (code "293") (name "/SDA87") (class "Default")
      (node (ref "R112") (pin "2") (pinfunction "2_2") (pintype "passive"))
      (node (ref "SV9") (pin "4") (pinfunction "4_4") (pintype "passive"))
      (node (ref "U42") (pin "19") (pinfunction "D8_19") (pintype "passive"))
    )
    (net (code "294") (name "/SDA88") (class "Default")
      (node (ref "R127") (pin "2") (pinfunction "2_2") (pintype "passive"))
      (node (ref "SV9") (pin "9") (pinfunction "9_9") (pintype "passive"))
      (node (ref "U43") (pin "6") (pinfunction "D1_6") (pintype "passive"))
    )
    (net (code "295") (name "/SDA89") (class "Default")
      (node (ref "R126") (pin "2") (pinfunction "2_2") (pintype "passive"))
      (node (ref "SV9") (pin "10") (pinfunction "10_10") (pintype "passive"))
      (node (ref "U43") (pin "8") (pinfunction "D2_8") (pintype "passive"))
    )
    (net (code "296") (name "/SDA90") (class "Default")
      (node (ref "R125") (pin "2") (pinfunction "2_2") (pintype "passive"))
      (node (ref "SV9") (pin "15") (pinfunction "15_15") (pintype "passive"))
      (node (ref "U43") (pin "10") (pinfunction "D3_10") (pintype "passive"))
    )
    (net (code "297") (name "/SDA91") (class "Default")
      (node (ref "R124") (pin "2") (pinfunction "2_2") (pintype "passive"))
      (node (ref "SV9") (pin "16") (pinfunction "16_16") (pintype "passive"))
      (node (ref "U43") (pin "12") (pinfunction "D4_12") (pintype "passive"))
    )
    (net (code "298") (name "/SDA92") (class "Default")
      (node (ref "R123") (pin "2") (pinfunction "2_2") (pintype "passive"))
      (node (ref "SV9") (pin "21") (pinfunction "21_21") (pintype "passive"))
      (node (ref "U43") (pin "13") (pinfunction "D5_13") (pintype "passive"))
    )
    (net (code "299") (name "/SDA93") (class "Default")
      (node (ref "R122") (pin "2") (pinfunction "2_2") (pintype "passive"))
      (node (ref "SV9") (pin "22") (pinfunction "22_22") (pintype "passive"))
      (node (ref "U43") (pin "15") (pinfunction "D6_15") (pintype "passive"))
    )
    (net (code "300") (name "/SDA94") (class "Default")
      (node (ref "R121") (pin "2") (pinfunction "2_2") (pintype "passive"))
      (node (ref "SV9") (pin "27") (pinfunction "27_27") (pintype "passive"))
      (node (ref "U43") (pin "17") (pinfunction "D7_17") (pintype "passive"))
    )
    (net (code "301") (name "/SDA95") (class "Default")
      (node (ref "R120") (pin "2") (pinfunction "2_2") (pintype "passive"))
      (node (ref "SV9") (pin "28") (pinfunction "28_28") (pintype "passive"))
      (node (ref "U43") (pin "19") (pinfunction "D8_19") (pintype "passive"))
    )
    (net (code "302") (name "/SDA_H") (class "Default")
      (node (ref "R154") (pin "2") (pinfunction "2_2") (pintype "passive"))
      (node (ref "TP1") (pin "TP") (pinfunction "TP_TP") (pintype "input"))
      (node (ref "U$1") (pin "50") (pinfunction "P_3.1_50") (pintype "bidirectional"))
      (node (ref "U3") (pin "4") (pinfunction "SDA_4") (pintype "input"))
      (node (ref "U54") (pin "3") (pinfunction "SDA_3") (pintype "passive"))
      (node (ref "U58") (pin "3") (pinfunction "SDA_3") (pintype "passive"))
    )
    (net (code "303") (name "/SDA_MP0") (class "Default")
      (node (ref "R160") (pin "2") (pinfunction "2_2") (pintype "passive"))
      (node (ref "TP16") (pin "TP") (pinfunction "TP_TP") (pintype "input"))
      (node (ref "U46") (pin "3") (pinfunction "SDAA_3") (pintype "bidirectional"))
      (node (ref "U56") (pin "3") (pinfunction "A1_3") (pintype "passive"))
    )
    (net (code "304") (name "/SDA_MP0B") (class "Default")
      (node (ref "R137") (pin "2") (pinfunction "2_2") (pintype "passive"))
      (node (ref "TP22") (pin "TP") (pinfunction "TP_TP") (pintype "input"))
      (node (ref "U4") (pin "14") (pinfunction "S5_14") (pintype "passive"))
      (node (ref "U4") (pin "16") (pinfunction "S6_16") (pintype "passive"))
      (node (ref "U4") (pin "18") (pinfunction "S7_18") (pintype "passive"))
      (node (ref "U4") (pin "20") (pinfunction "S8_20") (pintype "passive"))
      (node (ref "U46") (pin "6") (pinfunction "SDAB_6") (pintype "bidirectional"))
    )
    (net (code "305") (name "/SDA_MP1") (class "Default")
      (node (ref "R172") (pin "2") (pinfunction "2_2") (pintype "passive"))
      (node (ref "TP14") (pin "TP") (pinfunction "TP_TP") (pintype "input"))
      (node (ref "U46") (pin "2") (pinfunction "SCLA_2") (pintype "bidirectional"))
      (node (ref "U56") (pin "8") (pinfunction "A6_8") (pintype "passive"))
    )
    (net (code "306") (name "/SDA_MP1B") (class "Default")
      (node (ref "R136") (pin "2") (pinfunction "2_2") (pintype "passive"))
      (node (ref "U26") (pin "14") (pinfunction "S5_14") (pintype "passive"))
      (node (ref "U26") (pin "16") (pinfunction "S6_16") (pintype "passive"))
      (node (ref "U26") (pin "18") (pinfunction "S7_18") (pintype "passive"))
      (node (ref "U26") (pin "20") (pinfunction "S8_20") (pintype "passive"))
      (node (ref "U46") (pin "7") (pinfunction "SCLB_7") (pintype "bidirectional"))
    )
    (net (code "307") (name "/SDA_MP2") (class "Default")
      (node (ref "R170") (pin "2") (pinfunction "2_2") (pintype "passive"))
      (node (ref "TP17") (pin "TP") (pinfunction "TP_TP") (pintype "input"))
      (node (ref "U48") (pin "3") (pinfunction "SDAA_3") (pintype "bidirectional"))
      (node (ref "U56") (pin "6") (pinfunction "A4_6") (pintype "passive"))
    )
    (net (code "308") (name "/SDA_MP2B") (class "Default")
      (node (ref "R141") (pin "2") (pinfunction "2_2") (pintype "passive"))
      (node (ref "TP25") (pin "TP") (pinfunction "TP_TP") (pintype "input"))
      (node (ref "U48") (pin "6") (pinfunction "SDAB_6") (pintype "bidirectional"))
      (node (ref "U8") (pin "14") (pinfunction "S5_14") (pintype "passive"))
      (node (ref "U8") (pin "16") (pinfunction "S6_16") (pintype "passive"))
      (node (ref "U8") (pin "18") (pinfunction "S7_18") (pintype "passive"))
      (node (ref "U8") (pin "20") (pinfunction "S8_20") (pintype "passive"))
    )
    (net (code "309") (name "/SDA_MP3") (class "Default")
      (node (ref "R173") (pin "2") (pinfunction "2_2") (pintype "passive"))
      (node (ref "TP13") (pin "TP") (pinfunction "TP_TP") (pintype "input"))
      (node (ref "U48") (pin "2") (pinfunction "SCLA_2") (pintype "bidirectional"))
      (node (ref "U56") (pin "9") (pinfunction "A7_9") (pintype "passive"))
    )
    (net (code "310") (name "/SDA_MP3B") (class "Default")
      (node (ref "R139") (pin "2") (pinfunction "2_2") (pintype "passive"))
      (node (ref "U33") (pin "14") (pinfunction "S5_14") (pintype "passive"))
      (node (ref "U33") (pin "16") (pinfunction "S6_16") (pintype "passive"))
      (node (ref "U33") (pin "18") (pinfunction "S7_18") (pintype "passive"))
      (node (ref "U33") (pin "20") (pinfunction "S8_20") (pintype "passive"))
      (node (ref "U48") (pin "7") (pinfunction "SCLB_7") (pintype "bidirectional"))
    )
    (net (code "311") (name "/SDA_MP4") (class "Default")
      (node (ref "R171") (pin "2") (pinfunction "2_2") (pintype "passive"))
      (node (ref "TP15") (pin "TP") (pinfunction "TP_TP") (pintype "input"))
      (node (ref "U49") (pin "3") (pinfunction "SDAA_3") (pintype "bidirectional"))
      (node (ref "U56") (pin "7") (pinfunction "A5_7") (pintype "passive"))
    )
    (net (code "312") (name "/SDA_MP4B") (class "Default")
      (node (ref "R145") (pin "2") (pinfunction "2_2") (pintype "passive"))
      (node (ref "TP27") (pin "TP") (pinfunction "TP_TP") (pintype "input"))
      (node (ref "U19") (pin "14") (pinfunction "S5_14") (pintype "passive"))
      (node (ref "U19") (pin "16") (pinfunction "S6_16") (pintype "passive"))
      (node (ref "U19") (pin "18") (pinfunction "S7_18") (pintype "passive"))
      (node (ref "U19") (pin "20") (pinfunction "S8_20") (pintype "passive"))
      (node (ref "U49") (pin "6") (pinfunction "SDAB_6") (pintype "bidirectional"))
    )
    (net (code "313") (name "/SDA_MP5") (class "Default")
      (node (ref "R174") (pin "2") (pinfunction "2_2") (pintype "passive"))
      (node (ref "TP12") (pin "TP") (pinfunction "TP_TP") (pintype "input"))
      (node (ref "U49") (pin "2") (pinfunction "SCLA_2") (pintype "bidirectional"))
      (node (ref "U56") (pin "10") (pinfunction "A8_10") (pintype "passive"))
    )
    (net (code "314") (name "/SDA_MP5B") (class "Default")
      (node (ref "R144") (pin "2") (pinfunction "2_2") (pintype "passive"))
      (node (ref "U40") (pin "14") (pinfunction "S5_14") (pintype "passive"))
      (node (ref "U40") (pin "16") (pinfunction "S6_16") (pintype "passive"))
      (node (ref "U40") (pin "18") (pinfunction "S7_18") (pintype "passive"))
      (node (ref "U40") (pin "20") (pinfunction "S8_20") (pintype "passive"))
      (node (ref "U49") (pin "7") (pinfunction "SCLB_7") (pintype "bidirectional"))
    )
    (net (code "315") (name "/SYNC") (class "Default")
      (node (ref "SYNC") (pin "TP") (pinfunction "TP_TP") (pintype "input"))
      (node (ref "U$1") (pin "13") (pinfunction "P_12.3_13") (pintype "bidirectional"))
      (node (ref "U10") (pin "24") (pinfunction "SYNC_N_24") (pintype "passive"))
      (node (ref "U11") (pin "24") (pinfunction "SYNC_N_24") (pintype "passive"))
      (node (ref "U12") (pin "24") (pinfunction "SYNC_N_24") (pintype "passive"))
      (node (ref "U15") (pin "24") (pinfunction "SYNC_N_24") (pintype "passive"))
      (node (ref "U18") (pin "24") (pinfunction "SYNC_N_24") (pintype "passive"))
      (node (ref "U19") (pin "24") (pinfunction "SYNC_N_24") (pintype "passive"))
      (node (ref "U20") (pin "24") (pinfunction "SYNC_N_24") (pintype "passive"))
      (node (ref "U21") (pin "24") (pinfunction "SYNC_N_24") (pintype "passive"))
      (node (ref "U22") (pin "24") (pinfunction "SYNC_N_24") (pintype "passive"))
      (node (ref "U25") (pin "24") (pinfunction "SYNC_N_24") (pintype "passive"))
      (node (ref "U26") (pin "24") (pinfunction "SYNC_N_24") (pintype "passive"))
      (node (ref "U27") (pin "24") (pinfunction "SYNC_N_24") (pintype "passive"))
      (node (ref "U28") (pin "24") (pinfunction "SYNC_N_24") (pintype "passive"))
      (node (ref "U29") (pin "24") (pinfunction "SYNC_N_24") (pintype "passive"))
      (node (ref "U32") (pin "24") (pinfunction "SYNC_N_24") (pintype "passive"))
      (node (ref "U33") (pin "24") (pinfunction "SYNC_N_24") (pintype "passive"))
      (node (ref "U34") (pin "24") (pinfunction "SYNC_N_24") (pintype "passive"))
      (node (ref "U35") (pin "24") (pinfunction "SYNC_N_24") (pintype "passive"))
      (node (ref "U36") (pin "24") (pinfunction "SYNC_N_24") (pintype "passive"))
      (node (ref "U39") (pin "24") (pinfunction "SYNC_N_24") (pintype "passive"))
      (node (ref "U4") (pin "24") (pinfunction "SYNC_N_24") (pintype "passive"))
      (node (ref "U40") (pin "24") (pinfunction "SYNC_N_24") (pintype "passive"))
      (node (ref "U41") (pin "24") (pinfunction "SYNC_N_24") (pintype "passive"))
      (node (ref "U42") (pin "24") (pinfunction "SYNC_N_24") (pintype "passive"))
      (node (ref "U43") (pin "24") (pinfunction "SYNC_N_24") (pintype "passive"))
      (node (ref "U5") (pin "24") (pinfunction "SYNC_N_24") (pintype "passive"))
      (node (ref "U6") (pin "24") (pinfunction "SYNC_N_24") (pintype "passive"))
      (node (ref "U7") (pin "24") (pinfunction "SYNC_N_24") (pintype "passive"))
      (node (ref "U8") (pin "24") (pinfunction "SYNC_N_24") (pintype "passive"))
      (node (ref "U9") (pin "24") (pinfunction "SYNC_N_24") (pintype "passive"))
    )
    (net (code "316") (name "GND") (class "Default")
      (node (ref "C1") (pin "2") (pinfunction "2_2") (pintype "passive"))
      (node (ref "C10") (pin "2") (pinfunction "2_2") (pintype "passive"))
      (node (ref "C11") (pin "2") (pinfunction "2_2") (pintype "passive"))
      (node (ref "C12") (pin "2") (pinfunction "2_2") (pintype "passive"))
      (node (ref "C13") (pin "2") (pinfunction "2_2") (pintype "passive"))
      (node (ref "C14") (pin "2") (pinfunction "2_2") (pintype "passive"))
      (node (ref "C15") (pin "2") (pinfunction "2_2") (pintype "passive"))
      (node (ref "C16") (pin "2") (pinfunction "2_2") (pintype "passive"))
      (node (ref "C17") (pin "2") (pinfunction "2_2") (pintype "passive"))
      (node (ref "C18") (pin "2") (pinfunction "2_2") (pintype "passive"))
      (node (ref "C19") (pin "2") (pinfunction "2_2") (pintype "passive"))
      (node (ref "C2") (pin "2") (pinfunction "2_2") (pintype "passive"))
      (node (ref "C20") (pin "2") (pinfunction "2_2") (pintype "passive"))
      (node (ref "C21") (pin "2") (pinfunction "2_2") (pintype "passive"))
      (node (ref "C24") (pin "1") (pinfunction "1_1") (pintype "passive"))
      (node (ref "C25") (pin "2") (pinfunction "2_2") (pintype "passive"))
      (node (ref "C26") (pin "2") (pinfunction "2_2") (pintype "passive"))
      (node (ref "C27") (pin "2") (pinfunction "2_2") (pintype "passive"))
      (node (ref "C28") (pin "2") (pinfunction "2_2") (pintype "passive"))
      (node (ref "C29") (pin "2") (pinfunction "2_2") (pintype "passive"))
      (node (ref "C3") (pin "2") (pinfunction "2_2") (pintype "passive"))
      (node (ref "C30") (pin "2") (pinfunction "2_2") (pintype "passive"))
      (node (ref "C31") (pin "2") (pinfunction "2_2") (pintype "passive"))
      (node (ref "C32") (pin "2") (pinfunction "2_2") (pintype "passive"))
      (node (ref "C33") (pin "2") (pinfunction "2_2") (pintype "passive"))
      (node (ref "C34") (pin "2") (pinfunction "2_2") (pintype "passive"))
      (node (ref "C35") (pin "2") (pinfunction "2_2") (pintype "passive"))
      (node (ref "C36") (pin "2") (pinfunction "2_2") (pintype "passive"))
      (node (ref "C37") (pin "2") (pinfunction "2_2") (pintype "passive"))
      (node (ref "C38") (pin "2") (pinfunction "2_2") (pintype "passive"))
      (node (ref "C39") (pin "2") (pinfunction "2_2") (pintype "passive"))
      (node (ref "C4") (pin "2") (pinfunction "2_2") (pintype "passive"))
      (node (ref "C40") (pin "2") (pinfunction "2_2") (pintype "passive"))
      (node (ref "C41") (pin "2") (pinfunction "2_2") (pintype "passive"))
      (node (ref "C42") (pin "2") (pinfunction "2_2") (pintype "passive"))
      (node (ref "C43") (pin "2") (pinfunction "2_2") (pintype "passive"))
      (node (ref "C44") (pin "2") (pinfunction "2_2") (pintype "passive"))
      (node (ref "C45") (pin "2") (pinfunction "2_2") (pintype "passive"))
      (node (ref "C46") (pin "2") (pinfunction "2_2") (pintype "passive"))
      (node (ref "C47") (pin "2") (pinfunction "2_2") (pintype "passive"))
      (node (ref "C48") (pin "2") (pinfunction "2_2") (pintype "passive"))
      (node (ref "C49") (pin "2") (pinfunction "2_2") (pintype "passive"))
      (node (ref "C5") (pin "2") (pinfunction "2_2") (pintype "passive"))
      (node (ref "C50") (pin "2") (pinfunction "2_2") (pintype "passive"))
      (node (ref "C51") (pin "2") (pinfunction "2_2") (pintype "passive"))
      (node (ref "C52") (pin "2") (pinfunction "2_2") (pintype "passive"))
      (node (ref "C53") (pin "2") (pinfunction "2_2") (pintype "passive"))
      (node (ref "C54") (pin "2") (pinfunction "2_2") (pintype "passive"))
      (node (ref "C55") (pin "2") (pinfunction "2_2") (pintype "passive"))
      (node (ref "C56") (pin "2") (pinfunction "2_2") (pintype "passive"))
      (node (ref "C57") (pin "2") (pinfunction "2_2") (pintype "passive"))
      (node (ref "C58") (pin "2") (pinfunction "2_2") (pintype "passive"))
      (node (ref "C59") (pin "2") (pinfunction "2_2") (pintype "passive"))
      (node (ref "C6") (pin "2") (pinfunction "2_2") (pintype "passive"))
      (node (ref "C60") (pin "2") (pinfunction "2_2") (pintype "passive"))
      (node (ref "C61") (pin "2") (pinfunction "2_2") (pintype "passive"))
      (node (ref "C62") (pin "2") (pinfunction "2_2") (pintype "passive"))
      (node (ref "C63") (pin "2") (pinfunction "2_2") (pintype "passive"))
      (node (ref "C64") (pin "2") (pinfunction "2_2") (pintype "passive"))
      (node (ref "C65") (pin "2") (pinfunction "2_2") (pintype "passive"))
      (node (ref "C66") (pin "2") (pinfunction "2_2") (pintype "passive"))
      (node (ref "C67") (pin "1") (pinfunction "1_1") (pintype "passive"))
      (node (ref "C7") (pin "2") (pinfunction "2_2") (pintype "passive"))
      (node (ref "C8") (pin "2") (pinfunction "2_2") (pintype "passive"))
      (node (ref "C9") (pin "2") (pinfunction "2_2") (pintype "passive"))
      (node (ref "R1") (pin "2") (pinfunction "2_2") (pintype "passive"))
      (node (ref "R131") (pin "1") (pinfunction "1_1") (pintype "passive"))
      (node (ref "R_LDO1") (pin "2") (pinfunction "2_2") (pintype "passive"))
      (node (ref "R_LDO2") (pin "2") (pinfunction "2_2") (pintype "passive"))
      (node (ref "SV1") (pin "1") (pinfunction "1_1") (pintype "passive"))
      (node (ref "SV1") (pin "2") (pinfunction "2_2") (pintype "passive"))
      (node (ref "SV1") (pin "3") (pinfunction "3_3") (pintype "passive"))
      (node (ref "SV1") (pin "4") (pinfunction "4_4") (pintype "passive"))
      (node (ref "SV2") (pin "11") (pinfunction "11_11") (pintype "passive"))
      (node (ref "SV2") (pin "12") (pinfunction "12_12") (pintype "passive"))
      (node (ref "SV2") (pin "13") (pinfunction "13_13") (pintype "passive"))
      (node (ref "SV2") (pin "14") (pinfunction "14_14") (pintype "passive"))
      (node (ref "SV2") (pin "15") (pinfunction "15_15") (pintype "passive"))
      (node (ref "SV2") (pin "16") (pinfunction "16_16") (pintype "passive"))
      (node (ref "SV2") (pin "5") (pinfunction "5_5") (pintype "passive"))
      (node (ref "SV2") (pin "6") (pinfunction "6_6") (pintype "passive"))
      (node (ref "SV3") (pin "40") (pinfunction "40_40") (pintype "passive"))
      (node (ref "SV4") (pin "40") (pinfunction "40_40") (pintype "passive"))
      (node (ref "SV5") (pin "40") (pinfunction "40_40") (pintype "passive"))
      (node (ref "SV6") (pin "40") (pinfunction "40_40") (pintype "passive"))
      (node (ref "SV7") (pin "40") (pinfunction "40_40") (pintype "passive"))
      (node (ref "SV8") (pin "40") (pinfunction "40_40") (pintype "passive"))
      (node (ref "SV9") (pin "31") (pinfunction "31_31") (pintype "passive"))
      (node (ref "SV9") (pin "32") (pinfunction "32_32") (pintype "passive"))
      (node (ref "SV9") (pin "33") (pinfunction "33_33") (pintype "passive"))
      (node (ref "SV9") (pin "34") (pinfunction "34_34") (pintype "passive"))
      (node (ref "SV9") (pin "35") (pinfunction "35_35") (pintype "passive"))
      (node (ref "SV9") (pin "36") (pinfunction "36_36") (pintype "passive"))
      (node (ref "U$1") (pin "25") (pinfunction "GND3_25") (pintype "bidirectional"))
      (node (ref "U$1") (pin "28") (pinfunction "GND1_28") (pintype "bidirectional"))
      (node (ref "U$1") (pin "52") (pinfunction "GND2_52") (pintype "bidirectional"))
      (node (ref "U10") (pin "21") (pinfunction "VSS_21") (pintype "power_in"))
      (node (ref "U10") (pin "4") (pinfunction "GND_4") (pintype "passive"))
      (node (ref "U11") (pin "21") (pinfunction "VSS_21") (pintype "power_in"))
      (node (ref "U11") (pin "4") (pinfunction "GND_4") (pintype "passive"))
      (node (ref "U12") (pin "21") (pinfunction "VSS_21") (pintype "power_in"))
      (node (ref "U12") (pin "4") (pinfunction "GND_4") (pintype "passive"))
      (node (ref "U13") (pin "1") (pinfunction "~{1OE}_1") (pintype "bidirectional"))
      (node (ref "U13") (pin "10") (pinfunction "GND_10") (pintype "power_in"))
      (node (ref "U13") (pin "19") (pinfunction "~{2OE}_19") (pintype "bidirectional"))
      (node (ref "U14") (pin "1") (pinfunction "~{1OE}_1") (pintype "bidirectional"))
      (node (ref "U14") (pin "10") (pinfunction "GND_10") (pintype "power_in"))
      (node (ref "U14") (pin "19") (pinfunction "~{2OE}_19") (pintype "bidirectional"))
      (node (ref "U15") (pin "21") (pinfunction "VSS_21") (pintype "power_in"))
      (node (ref "U15") (pin "4") (pinfunction "GND_4") (pintype "passive"))
      (node (ref "U16") (pin "1") (pinfunction "~{1OE}_1") (pintype "bidirectional"))
      (node (ref "U16") (pin "10") (pinfunction "GND_10") (pintype "power_in"))
      (node (ref "U16") (pin "19") (pinfunction "~{2OE}_19") (pintype "bidirectional"))
      (node (ref "U17") (pin "1") (pinfunction "~{1OE}_1") (pintype "bidirectional"))
      (node (ref "U17") (pin "10") (pinfunction "GND_10") (pintype "power_in"))
      (node (ref "U17") (pin "19") (pinfunction "~{2OE}_19") (pintype "bidirectional"))
      (node (ref "U18") (pin "21") (pinfunction "VSS_21") (pintype "power_in"))
      (node (ref "U18") (pin "4") (pinfunction "GND_4") (pintype "passive"))
      (node (ref "U19") (pin "21") (pinfunction "VSS_21") (pintype "power_in"))
      (node (ref "U19") (pin "4") (pinfunction "GND_4") (pintype "passive"))
      (node (ref "U20") (pin "21") (pinfunction "VSS_21") (pintype "power_in"))
      (node (ref "U20") (pin "4") (pinfunction "GND_4") (pintype "passive"))
      (node (ref "U21") (pin "21") (pinfunction "VSS_21") (pintype "power_in"))
      (node (ref "U21") (pin "4") (pinfunction "GND_4") (pintype "passive"))
      (node (ref "U22") (pin "21") (pinfunction "VSS_21") (pintype "power_in"))
      (node (ref "U22") (pin "4") (pinfunction "GND_4") (pintype "passive"))
      (node (ref "U23") (pin "1") (pinfunction "~{1OE}_1") (pintype "bidirectional"))
      (node (ref "U23") (pin "10") (pinfunction "GND_10") (pintype "power_in"))
      (node (ref "U23") (pin "19") (pinfunction "~{2OE}_19") (pintype "bidirectional"))
      (node (ref "U24") (pin "1") (pinfunction "~{1OE}_1") (pintype "bidirectional"))
      (node (ref "U24") (pin "10") (pinfunction "GND_10") (pintype "power_in"))
      (node (ref "U24") (pin "19") (pinfunction "~{2OE}_19") (pintype "bidirectional"))
      (node (ref "U25") (pin "21") (pinfunction "VSS_21") (pintype "power_in"))
      (node (ref "U25") (pin "4") (pinfunction "GND_4") (pintype "passive"))
      (node (ref "U26") (pin "21") (pinfunction "VSS_21") (pintype "power_in"))
      (node (ref "U26") (pin "4") (pinfunction "GND_4") (pintype "passive"))
      (node (ref "U27") (pin "21") (pinfunction "VSS_21") (pintype "power_in"))
      (node (ref "U27") (pin "4") (pinfunction "GND_4") (pintype "passive"))
      (node (ref "U28") (pin "21") (pinfunction "VSS_21") (pintype "power_in"))
      (node (ref "U28") (pin "4") (pinfunction "GND_4") (pintype "passive"))
      (node (ref "U29") (pin "21") (pinfunction "VSS_21") (pintype "power_in"))
      (node (ref "U29") (pin "4") (pinfunction "GND_4") (pintype "passive"))
      (node (ref "U3") (pin "2") (pinfunction "GND_2") (pintype "power_in"))
      (node (ref "U30") (pin "1") (pinfunction "~{1OE}_1") (pintype "bidirectional"))
      (node (ref "U30") (pin "10") (pinfunction "GND_10") (pintype "power_in"))
      (node (ref "U30") (pin "19") (pinfunction "~{2OE}_19") (pintype "bidirectional"))
      (node (ref "U31") (pin "1") (pinfunction "~{1OE}_1") (pintype "bidirectional"))
      (node (ref "U31") (pin "10") (pinfunction "GND_10") (pintype "power_in"))
      (node (ref "U31") (pin "19") (pinfunction "~{2OE}_19") (pintype "bidirectional"))
      (node (ref "U32") (pin "21") (pinfunction "VSS_21") (pintype "power_in"))
      (node (ref "U32") (pin "4") (pinfunction "GND_4") (pintype "passive"))
      (node (ref "U33") (pin "21") (pinfunction "VSS_21") (pintype "power_in"))
      (node (ref "U33") (pin "4") (pinfunction "GND_4") (pintype "passive"))
      (node (ref "U34") (pin "21") (pinfunction "VSS_21") (pintype "power_in"))
      (node (ref "U34") (pin "4") (pinfunction "GND_4") (pintype "passive"))
      (node (ref "U35") (pin "21") (pinfunction "VSS_21") (pintype "power_in"))
      (node (ref "U35") (pin "4") (pinfunction "GND_4") (pintype "passive"))
      (node (ref "U36") (pin "21") (pinfunction "VSS_21") (pintype "power_in"))
      (node (ref "U36") (pin "4") (pinfunction "GND_4") (pintype "passive"))
      (node (ref "U37") (pin "1") (pinfunction "~{1OE}_1") (pintype "bidirectional"))
      (node (ref "U37") (pin "10") (pinfunction "GND_10") (pintype "power_in"))
      (node (ref "U37") (pin "19") (pinfunction "~{2OE}_19") (pintype "bidirectional"))
      (node (ref "U38") (pin "1") (pinfunction "~{1OE}_1") (pintype "bidirectional"))
      (node (ref "U38") (pin "10") (pinfunction "GND_10") (pintype "power_in"))
      (node (ref "U38") (pin "19") (pinfunction "~{2OE}_19") (pintype "bidirectional"))
      (node (ref "U39") (pin "21") (pinfunction "VSS_21") (pintype "power_in"))
      (node (ref "U39") (pin "4") (pinfunction "GND_4") (pintype "passive"))
      (node (ref "U4") (pin "21") (pinfunction "VSS_21") (pintype "power_in"))
      (node (ref "U4") (pin "4") (pinfunction "GND_4") (pintype "passive"))
      (node (ref "U40") (pin "21") (pinfunction "VSS_21") (pintype "power_in"))
      (node (ref "U40") (pin "4") (pinfunction "GND_4") (pintype "passive"))
      (node (ref "U41") (pin "21") (pinfunction "VSS_21") (pintype "power_in"))
      (node (ref "U41") (pin "4") (pinfunction "GND_4") (pintype "passive"))
      (node (ref "U42") (pin "21") (pinfunction "VSS_21") (pintype "power_in"))
      (node (ref "U42") (pin "4") (pinfunction "GND_4") (pintype "passive"))
      (node (ref "U43") (pin "21") (pinfunction "VSS_21") (pintype "power_in"))
      (node (ref "U43") (pin "4") (pinfunction "GND_4") (pintype "passive"))
      (node (ref "U44") (pin "1") (pinfunction "~{1OE}_1") (pintype "bidirectional"))
      (node (ref "U44") (pin "10") (pinfunction "GND_10") (pintype "power_in"))
      (node (ref "U44") (pin "19") (pinfunction "~{2OE}_19") (pintype "bidirectional"))
      (node (ref "U45") (pin "1") (pinfunction "~{1OE}_1") (pintype "bidirectional"))
      (node (ref "U45") (pin "10") (pinfunction "GND_10") (pintype "power_in"))
      (node (ref "U45") (pin "19") (pinfunction "~{2OE}_19") (pintype "bidirectional"))
      (node (ref "U46") (pin "4") (pinfunction "GND_4") (pintype "power_in"))
      (node (ref "U47") (pin "4") (pinfunction "GND_4") (pintype "power_in"))
      (node (ref "U48") (pin "4") (pinfunction "GND_4") (pintype "power_in"))
      (node (ref "U49") (pin "4") (pinfunction "GND_4") (pintype "power_in"))
      (node (ref "U5") (pin "21") (pinfunction "VSS_21") (pintype "power_in"))
      (node (ref "U5") (pin "4") (pinfunction "GND_4") (pintype "passive"))
      (node (ref "U54") (pin "21") (pinfunction "VSS_21") (pintype "power_in"))
      (node (ref "U54") (pin "22") (pinfunction "A1_22") (pintype "passive"))
      (node (ref "U54") (pin "24") (pinfunction "A0_24") (pintype "passive"))
      (node (ref "U54") (pin "4") (pinfunction "GND_4") (pintype "passive"))
      (node (ref "U56") (pin "1") (pinfunction "GND_1") (pintype "power_in"))
      (node (ref "U56") (pin "21") (pinfunction "EPAD_21") (pintype "passive"))
      (node (ref "U58") (pin "21") (pinfunction "VSS_21") (pintype "power_in"))
      (node (ref "U58") (pin "22") (pinfunction "A1_22") (pintype "passive"))
      (node (ref "U58") (pin "4") (pinfunction "GND_4") (pintype "passive"))
      (node (ref "U6") (pin "21") (pinfunction "VSS_21") (pintype "power_in"))
      (node (ref "U6") (pin "4") (pinfunction "GND_4") (pintype "passive"))
      (node (ref "U7") (pin "21") (pinfunction "VSS_21") (pintype "power_in"))
      (node (ref "U7") (pin "4") (pinfunction "GND_4") (pintype "passive"))
      (node (ref "U8") (pin "21") (pinfunction "VSS_21") (pintype "power_in"))
      (node (ref "U8") (pin "4") (pinfunction "GND_4") (pintype "passive"))
      (node (ref "U9") (pin "21") (pinfunction "VSS_21") (pintype "power_in"))
      (node (ref "U9") (pin "4") (pinfunction "GND_4") (pintype "passive"))
      (node (ref "X5") (pin "1") (pinfunction "1_1") (pintype "passive"))
      (node (ref "X5") (pin "1@1") (pinfunction "1_1@1") (pintype "passive"))
      (node (ref "X6") (pin "1") (pinfunction "1_1") (pintype "passive"))
      (node (ref "X6") (pin "1@1") (pinfunction "1_1@1") (pintype "passive"))
    )
    (net (code "317") (name "Net-(U$1-P_1.2)") (class "Default")
      (node (ref "R169") (pin "2") (pinfunction "2_2") (pintype "passive"))
      (node (ref "U$1") (pin "19") (pinfunction "P_1.2_19") (pintype "bidirectional"))
      (node (ref "U56") (pin "11") (pinfunction "B8_11") (pintype "passive"))
    )
    (net (code "318") (name "Net-(U$1-P_1.4)") (class "Default")
      (node (ref "R168") (pin "2") (pinfunction "2_2") (pintype "passive"))
      (node (ref "U$1") (pin "21") (pinfunction "P_1.4_21") (pintype "bidirectional"))
      (node (ref "U56") (pin "12") (pinfunction "B7_12") (pintype "passive"))
    )
    (net (code "319") (name "Net-(U$1-P_1.5)") (class "Default")
      (node (ref "R167") (pin "2") (pinfunction "2_2") (pintype "passive"))
      (node (ref "U$1") (pin "22") (pinfunction "P_1.5_22") (pintype "bidirectional"))
      (node (ref "U56") (pin "13") (pinfunction "B6_13") (pintype "passive"))
    )
    (net (code "320") (name "Net-(U$1-P_1.6)") (class "Default")
      (node (ref "R166") (pin "2") (pinfunction "2_2") (pintype "passive"))
      (node (ref "U$1") (pin "23") (pinfunction "P_1.6_23") (pintype "bidirectional"))
      (node (ref "U56") (pin "14") (pinfunction "B5_14") (pintype "passive"))
    )
    (net (code "321") (name "Net-(U$1-P_1.7)") (class "Default")
      (node (ref "R165") (pin "2") (pinfunction "2_2") (pintype "passive"))
      (node (ref "U$1") (pin "24") (pinfunction "P_1.7_24") (pintype "bidirectional"))
      (node (ref "U56") (pin "15") (pinfunction "B4_15") (pintype "passive"))
    )
    (net (code "322") (name "Net-(U$1-P_3.3)") (class "Default")
      (node (ref "MOSI") (pin "TP") (pinfunction "TP_TP") (pintype "input"))
      (node (ref "U$1") (pin "48") (pinfunction "P_3.3_48") (pintype "bidirectional"))
      (node (ref "U19") (pin "3") (pinfunction "DIN_3") (pintype "passive"))
      (node (ref "U26") (pin "3") (pinfunction "DIN_3") (pintype "passive"))
      (node (ref "U33") (pin "3") (pinfunction "DIN_3") (pintype "passive"))
      (node (ref "U4") (pin "3") (pinfunction "DIN_3") (pintype "passive"))
      (node (ref "U40") (pin "3") (pinfunction "DIN_3") (pintype "passive"))
      (node (ref "U8") (pin "3") (pinfunction "DIN_3") (pintype "passive"))
    )
    (net (code "323") (name "Net-(U$1-P_3.4)") (class "Default")
      (node (ref "SCK") (pin "TP") (pinfunction "TP_TP") (pintype "input"))
      (node (ref "U$1") (pin "47") (pinfunction "P_3.4_47") (pintype "bidirectional"))
      (node (ref "U10") (pin "1") (pinfunction "SCLK_1") (pintype "passive"))
      (node (ref "U11") (pin "1") (pinfunction "SCLK_1") (pintype "passive"))
      (node (ref "U12") (pin "1") (pinfunction "SCLK_1") (pintype "passive"))
      (node (ref "U15") (pin "1") (pinfunction "SCLK_1") (pintype "passive"))
      (node (ref "U18") (pin "1") (pinfunction "SCLK_1") (pintype "passive"))
      (node (ref "U19") (pin "1") (pinfunction "SCLK_1") (pintype "passive"))
      (node (ref "U20") (pin "1") (pinfunction "SCLK_1") (pintype "passive"))
      (node (ref "U21") (pin "1") (pinfunction "SCLK_1") (pintype "passive"))
      (node (ref "U22") (pin "1") (pinfunction "SCLK_1") (pintype "passive"))
      (node (ref "U25") (pin "1") (pinfunction "SCLK_1") (pintype "passive"))
      (node (ref "U26") (pin "1") (pinfunction "SCLK_1") (pintype "passive"))
      (node (ref "U27") (pin "1") (pinfunction "SCLK_1") (pintype "passive"))
      (node (ref "U28") (pin "1") (pinfunction "SCLK_1") (pintype "passive"))
      (node (ref "U29") (pin "1") (pinfunction "SCLK_1") (pintype "passive"))
      (node (ref "U32") (pin "1") (pinfunction "SCLK_1") (pintype "passive"))
      (node (ref "U33") (pin "1") (pinfunction "SCLK_1") (pintype "passive"))
      (node (ref "U34") (pin "1") (pinfunction "SCLK_1") (pintype "passive"))
      (node (ref "U35") (pin "1") (pinfunction "SCLK_1") (pintype "passive"))
      (node (ref "U36") (pin "1") (pinfunction "SCLK_1") (pintype "passive"))
      (node (ref "U39") (pin "1") (pinfunction "SCLK_1") (pintype "passive"))
      (node (ref "U4") (pin "1") (pinfunction "SCLK_1") (pintype "passive"))
      (node (ref "U40") (pin "1") (pinfunction "SCLK_1") (pintype "passive"))
      (node (ref "U41") (pin "1") (pinfunction "SCLK_1") (pintype "passive"))
      (node (ref "U42") (pin "1") (pinfunction "SCLK_1") (pintype "passive"))
      (node (ref "U43") (pin "1") (pinfunction "SCLK_1") (pintype "passive"))
      (node (ref "U5") (pin "1") (pinfunction "SCLK_1") (pintype "passive"))
      (node (ref "U6") (pin "1") (pinfunction "SCLK_1") (pintype "passive"))
      (node (ref "U7") (pin "1") (pinfunction "SCLK_1") (pintype "passive"))
      (node (ref "U8") (pin "1") (pinfunction "SCLK_1") (pintype "passive"))
      (node (ref "U9") (pin "1") (pinfunction "SCLK_1") (pintype "passive"))
    )
    (net (code "324") (name "Net-(U$1-P_12.4)") (class "Default")
      (node (ref "R162") (pin "2") (pinfunction "2_2") (pintype "passive"))
      (node (ref "U$1") (pin "12") (pinfunction "P_12.4_12") (pintype "bidirectional"))
      (node (ref "U56") (pin "17") (pinfunction "B2_17") (pintype "passive"))
    )
    (net (code "325") (name "Net-(U$1-P_12.5)") (class "Default")
      (node (ref "R161") (pin "2") (pinfunction "2_2") (pintype "passive"))
      (node (ref "U$1") (pin "11") (pinfunction "P_12.5_11") (pintype "bidirectional"))
      (node (ref "U56") (pin "18") (pinfunction "B1_18") (pintype "passive"))
    )
    (net (code "326") (name "Net-(U1-IN)") (class "Default")
      (node (ref "C1") (pin "1") (pinfunction "1_1") (pintype "passive"))
      (node (ref "C2") (pin "1") (pinfunction "1_1") (pintype "passive"))
      (node (ref "U1") (pin "3") (pinfunction "IN_3") (pintype "input"))
      (node (ref "X2") (pin "1") (pinfunction "1_1") (pintype "passive"))
      (node (ref "X2") (pin "1@1") (pinfunction "1_1@1") (pintype "passive"))
    )
    (net (code "327") (name "Net-(U1-SET)") (class "Default")
      (node (ref "C4") (pin "1") (pinfunction "1_1") (pintype "passive"))
      (node (ref "R1") (pin "1") (pinfunction "1_1") (pintype "passive"))
      (node (ref "U1") (pin "1") (pinfunction "SET_1") (pintype "input"))
    )
    (net (code "328") (name "Net-(U2-OUT)") (class "Default")
      (node (ref "C5") (pin "1") (pinfunction "1_1") (pintype "passive"))
      (node (ref "JP1") (pin "1") (pinfunction "1_1") (pintype "passive"))
      (node (ref "JP2") (pin "2") (pinfunction "2_2") (pintype "passive"))
      (node (ref "R_LDO1") (pin "1") (pinfunction "1_1") (pintype "passive"))
      (node (ref "U2") (pin "1") (pinfunction "OUT_2_1") (pintype "output"))
      (node (ref "U2") (pin "16") (pinfunction "OUT_16") (pintype "output"))
      (node (ref "U2") (pin "2") (pinfunction "OUT_3_2") (pintype "output"))
      (node (ref "U2") (pin "3") (pinfunction "OUT_4_3") (pintype "output"))
      (node (ref "U2") (pin "4") (pinfunction "OUT_5_4") (pintype "output"))
      (node (ref "U2") (pin "5") (pinfunction "OUT_6_5") (pintype "output"))
      (node (ref "U2") (pin "6") (pinfunction "OUT_7_6") (pintype "output"))
      (node (ref "U2") (pin "8") (pinfunction "OUT_8_8") (pintype "output"))
      (node (ref "U2") (pin "9") (pinfunction "OUT_9_9") (pintype "output"))
      (node (ref "U2") (pin "EPAD") (pinfunction "EPAD_EPAD") (pintype "passive"))
    )
    (net (code "329") (name "Net-(U2-SET)") (class "Default")
      (node (ref "C7") (pin "1") (pinfunction "1_1") (pintype "passive"))
      (node (ref "R2") (pin "2") (pinfunction "2_2") (pintype "passive"))
      (node (ref "U2") (pin "7") (pinfunction "SET_7") (pintype "passive"))
    )
    (net (code "330") (name "Net-(U3-VOUT)") (class "Default")
      (node (ref "R2") (pin "1") (pinfunction "1_1") (pintype "passive"))
      (node (ref "U3") (pin "1") (pinfunction "VOUT_1") (pintype "output"))
    )
    (net (code "331") (name "Net-(U4-D1)") (class "Default")
      (node (ref "U4") (pin "6") (pinfunction "D1_6") (pintype "passive"))
      (node (ref "U5") (pin "11") (pinfunction "S4_11") (pintype "passive"))
      (node (ref "U5") (pin "5") (pinfunction "S1_5") (pintype "passive"))
      (node (ref "U5") (pin "7") (pinfunction "S2_7") (pintype "passive"))
      (node (ref "U5") (pin "9") (pinfunction "S3_9") (pintype "passive"))
    )
    (net (code "332") (name "Net-(U4-D2)") (class "Default")
      (node (ref "U4") (pin "8") (pinfunction "D2_8") (pintype "passive"))
      (node (ref "U5") (pin "14") (pinfunction "S5_14") (pintype "passive"))
      (node (ref "U5") (pin "16") (pinfunction "S6_16") (pintype "passive"))
      (node (ref "U5") (pin "18") (pinfunction "S7_18") (pintype "passive"))
      (node (ref "U5") (pin "20") (pinfunction "S8_20") (pintype "passive"))
    )
    (net (code "333") (name "Net-(U4-D3)") (class "Default")
      (node (ref "U4") (pin "10") (pinfunction "D3_10") (pintype "passive"))
      (node (ref "U6") (pin "11") (pinfunction "S4_11") (pintype "passive"))
      (node (ref "U6") (pin "5") (pinfunction "S1_5") (pintype "passive"))
      (node (ref "U6") (pin "7") (pinfunction "S2_7") (pintype "passive"))
      (node (ref "U6") (pin "9") (pinfunction "S3_9") (pintype "passive"))
    )
    (net (code "334") (name "Net-(U4-D4)") (class "Default")
      (node (ref "U4") (pin "12") (pinfunction "D4_12") (pintype "passive"))
      (node (ref "U6") (pin "14") (pinfunction "S5_14") (pintype "passive"))
      (node (ref "U6") (pin "16") (pinfunction "S6_16") (pintype "passive"))
      (node (ref "U6") (pin "18") (pinfunction "S7_18") (pintype "passive"))
      (node (ref "U6") (pin "20") (pinfunction "S8_20") (pintype "passive"))
    )
    (net (code "335") (name "Net-(U4-D5)") (class "Default")
      (node (ref "U4") (pin "13") (pinfunction "D5_13") (pintype "passive"))
      (node (ref "U9") (pin "11") (pinfunction "S4_11") (pintype "passive"))
      (node (ref "U9") (pin "5") (pinfunction "S1_5") (pintype "passive"))
      (node (ref "U9") (pin "7") (pinfunction "S2_7") (pintype "passive"))
      (node (ref "U9") (pin "9") (pinfunction "S3_9") (pintype "passive"))
    )
    (net (code "336") (name "Net-(U4-D6)") (class "Default")
      (node (ref "U4") (pin "15") (pinfunction "D6_15") (pintype "passive"))
      (node (ref "U9") (pin "14") (pinfunction "S5_14") (pintype "passive"))
      (node (ref "U9") (pin "16") (pinfunction "S6_16") (pintype "passive"))
      (node (ref "U9") (pin "18") (pinfunction "S7_18") (pintype "passive"))
      (node (ref "U9") (pin "20") (pinfunction "S8_20") (pintype "passive"))
    )
    (net (code "337") (name "Net-(U4-DOUT)") (class "Default")
      (node (ref "R11") (pin "2") (pinfunction "2_2") (pintype "passive"))
      (node (ref "U4") (pin "22") (pinfunction "DOUT_22") (pintype "passive"))
      (node (ref "U5") (pin "3") (pinfunction "DIN_3") (pintype "passive"))
    )
    (net (code "338") (name "Net-(U5-DOUT)") (class "Default")
      (node (ref "R3") (pin "2") (pinfunction "2_2") (pintype "passive"))
      (node (ref "U5") (pin "22") (pinfunction "DOUT_22") (pintype "passive"))
      (node (ref "U6") (pin "3") (pinfunction "DIN_3") (pintype "passive"))
    )
    (net (code "339") (name "Net-(U6-DOUT)") (class "Default")
      (node (ref "R4") (pin "2") (pinfunction "2_2") (pintype "passive"))
      (node (ref "U6") (pin "22") (pinfunction "DOUT_22") (pintype "passive"))
      (node (ref "U9") (pin "3") (pinfunction "DIN_3") (pintype "passive"))
    )
    (net (code "340") (name "Net-(U7-DIN)") (class "Default")
      (node (ref "R10") (pin "2") (pinfunction "2_2") (pintype "passive"))
      (node (ref "U7") (pin "3") (pinfunction "DIN_3") (pintype "passive"))
      (node (ref "U8") (pin "22") (pinfunction "DOUT_22") (pintype "passive"))
    )
    (net (code "341") (name "Net-(U7-S1)") (class "Default")
      (node (ref "U7") (pin "11") (pinfunction "S4_11") (pintype "passive"))
      (node (ref "U7") (pin "5") (pinfunction "S1_5") (pintype "passive"))
      (node (ref "U7") (pin "7") (pinfunction "S2_7") (pintype "passive"))
      (node (ref "U7") (pin "9") (pinfunction "S3_9") (pintype "passive"))
      (node (ref "U8") (pin "6") (pinfunction "D1_6") (pintype "passive"))
    )
    (net (code "342") (name "Net-(U7-S5)") (class "Default")
      (node (ref "U7") (pin "14") (pinfunction "S5_14") (pintype "passive"))
      (node (ref "U7") (pin "16") (pinfunction "S6_16") (pintype "passive"))
      (node (ref "U7") (pin "18") (pinfunction "S7_18") (pintype "passive"))
      (node (ref "U7") (pin "20") (pinfunction "S8_20") (pintype "passive"))
      (node (ref "U8") (pin "8") (pinfunction "D2_8") (pintype "passive"))
    )
    (net (code "343") (name "Net-(U10-DIN)") (class "Default")
      (node (ref "R7") (pin "2") (pinfunction "2_2") (pintype "passive"))
      (node (ref "U10") (pin "3") (pinfunction "DIN_3") (pintype "passive"))
      (node (ref "U9") (pin "22") (pinfunction "DOUT_22") (pintype "passive"))
    )
    (net (code "344") (name "Net-(U10-DOUT)") (class "Default")
      (node (ref "R8") (pin "1") (pinfunction "1_1") (pintype "passive"))
      (node (ref "U10") (pin "22") (pinfunction "DOUT_22") (pintype "passive"))
    )
    (net (code "345") (name "Net-(U10-S1)") (class "Default")
      (node (ref "U10") (pin "11") (pinfunction "S4_11") (pintype "passive"))
      (node (ref "U10") (pin "5") (pinfunction "S1_5") (pintype "passive"))
      (node (ref "U10") (pin "7") (pinfunction "S2_7") (pintype "passive"))
      (node (ref "U10") (pin "9") (pinfunction "S3_9") (pintype "passive"))
      (node (ref "U4") (pin "17") (pinfunction "D7_17") (pintype "passive"))
    )
    (net (code "346") (name "Net-(U10-S5)") (class "Default")
      (node (ref "U10") (pin "14") (pinfunction "S5_14") (pintype "passive"))
      (node (ref "U10") (pin "16") (pinfunction "S6_16") (pintype "passive"))
      (node (ref "U10") (pin "18") (pinfunction "S7_18") (pintype "passive"))
      (node (ref "U10") (pin "20") (pinfunction "S8_20") (pintype "passive"))
      (node (ref "U4") (pin "19") (pinfunction "D8_19") (pintype "passive"))
    )
    (net (code "347") (name "Net-(U11-DIN)") (class "Default")
      (node (ref "R5") (pin "2") (pinfunction "2_2") (pintype "passive"))
      (node (ref "U11") (pin "3") (pinfunction "DIN_3") (pintype "passive"))
      (node (ref "U7") (pin "22") (pinfunction "DOUT_22") (pintype "passive"))
    )
    (net (code "348") (name "Net-(U11-DOUT)") (class "Default")
      (node (ref "R6") (pin "2") (pinfunction "2_2") (pintype "passive"))
      (node (ref "U11") (pin "22") (pinfunction "DOUT_22") (pintype "passive"))
      (node (ref "U12") (pin "3") (pinfunction "DIN_3") (pintype "passive"))
    )
    (net (code "349") (name "Net-(U11-S1)") (class "Default")
      (node (ref "U11") (pin "11") (pinfunction "S4_11") (pintype "passive"))
      (node (ref "U11") (pin "5") (pinfunction "S1_5") (pintype "passive"))
      (node (ref "U11") (pin "7") (pinfunction "S2_7") (pintype "passive"))
      (node (ref "U11") (pin "9") (pinfunction "S3_9") (pintype "passive"))
      (node (ref "U8") (pin "10") (pinfunction "D3_10") (pintype "passive"))
    )
    (net (code "350") (name "Net-(U11-S5)") (class "Default")
      (node (ref "U11") (pin "14") (pinfunction "S5_14") (pintype "passive"))
      (node (ref "U11") (pin "16") (pinfunction "S6_16") (pintype "passive"))
      (node (ref "U11") (pin "18") (pinfunction "S7_18") (pintype "passive"))
      (node (ref "U11") (pin "20") (pinfunction "S8_20") (pintype "passive"))
      (node (ref "U8") (pin "12") (pinfunction "D4_12") (pintype "passive"))
    )
    (net (code "351") (name "Net-(U12-DOUT)") (class "Default")
      (node (ref "R9") (pin "2") (pinfunction "2_2") (pintype "passive"))
      (node (ref "U12") (pin "22") (pinfunction "DOUT_22") (pintype "passive"))
      (node (ref "U15") (pin "3") (pinfunction "DIN_3") (pintype "passive"))
    )
    (net (code "352") (name "Net-(U12-S1)") (class "Default")
      (node (ref "U12") (pin "11") (pinfunction "S4_11") (pintype "passive"))
      (node (ref "U12") (pin "5") (pinfunction "S1_5") (pintype "passive"))
      (node (ref "U12") (pin "7") (pinfunction "S2_7") (pintype "passive"))
      (node (ref "U12") (pin "9") (pinfunction "S3_9") (pintype "passive"))
      (node (ref "U8") (pin "13") (pinfunction "D5_13") (pintype "passive"))
    )
    (net (code "353") (name "Net-(U12-S5)") (class "Default")
      (node (ref "U12") (pin "14") (pinfunction "S5_14") (pintype "passive"))
      (node (ref "U12") (pin "16") (pinfunction "S6_16") (pintype "passive"))
      (node (ref "U12") (pin "18") (pinfunction "S7_18") (pintype "passive"))
      (node (ref "U12") (pin "20") (pinfunction "S8_20") (pintype "passive"))
      (node (ref "U8") (pin "15") (pinfunction "D6_15") (pintype "passive"))
    )
    (net (code "354") (name "Net-(U15-DOUT)") (class "Default")
      (node (ref "R44") (pin "1") (pinfunction "1_1") (pintype "passive"))
      (node (ref "U15") (pin "22") (pinfunction "DOUT_22") (pintype "passive"))
    )
    (net (code "355") (name "Net-(U15-S1)") (class "Default")
      (node (ref "U15") (pin "11") (pinfunction "S4_11") (pintype "passive"))
      (node (ref "U15") (pin "5") (pinfunction "S1_5") (pintype "passive"))
      (node (ref "U15") (pin "7") (pinfunction "S2_7") (pintype "passive"))
      (node (ref "U15") (pin "9") (pinfunction "S3_9") (pintype "passive"))
      (node (ref "U8") (pin "17") (pinfunction "D7_17") (pintype "passive"))
    )
    (net (code "356") (name "Net-(U15-S5)") (class "Default")
      (node (ref "U15") (pin "14") (pinfunction "S5_14") (pintype "passive"))
      (node (ref "U15") (pin "16") (pinfunction "S6_16") (pintype "passive"))
      (node (ref "U15") (pin "18") (pinfunction "S7_18") (pintype "passive"))
      (node (ref "U15") (pin "20") (pinfunction "S8_20") (pintype "passive"))
      (node (ref "U8") (pin "19") (pinfunction "D8_19") (pintype "passive"))
    )
    (net (code "357") (name "Net-(U18-DIN)") (class "Default")
      (node (ref "R48") (pin "2") (pinfunction "2_2") (pintype "passive"))
      (node (ref "U18") (pin "3") (pinfunction "DIN_3") (pintype "passive"))
      (node (ref "U19") (pin "22") (pinfunction "DOUT_22") (pintype "passive"))
    )
    (net (code "358") (name "Net-(U18-DOUT)") (class "Default")
      (node (ref "R45") (pin "2") (pinfunction "2_2") (pintype "passive"))
      (node (ref "U18") (pin "22") (pinfunction "DOUT_22") (pintype "passive"))
      (node (ref "U20") (pin "3") (pinfunction "DIN_3") (pintype "passive"))
    )
    (net (code "359") (name "Net-(U18-S1)") (class "Default")
      (node (ref "U18") (pin "11") (pinfunction "S4_11") (pintype "passive"))
      (node (ref "U18") (pin "5") (pinfunction "S1_5") (pintype "passive"))
      (node (ref "U18") (pin "7") (pinfunction "S2_7") (pintype "passive"))
      (node (ref "U18") (pin "9") (pinfunction "S3_9") (pintype "passive"))
      (node (ref "U19") (pin "6") (pinfunction "D1_6") (pintype "passive"))
    )
    (net (code "360") (name "Net-(U18-S5)") (class "Default")
      (node (ref "U18") (pin "14") (pinfunction "S5_14") (pintype "passive"))
      (node (ref "U18") (pin "16") (pinfunction "S6_16") (pintype "passive"))
      (node (ref "U18") (pin "18") (pinfunction "S7_18") (pintype "passive"))
      (node (ref "U18") (pin "20") (pinfunction "S8_20") (pintype "passive"))
      (node (ref "U19") (pin "8") (pinfunction "D2_8") (pintype "passive"))
    )
    (net (code "361") (name "Net-(U19-D3)") (class "Default")
      (node (ref "U19") (pin "10") (pinfunction "D3_10") (pintype "passive"))
      (node (ref "U20") (pin "11") (pinfunction "S4_11") (pintype "passive"))
      (node (ref "U20") (pin "5") (pinfunction "S1_5") (pintype "passive"))
      (node (ref "U20") (pin "7") (pinfunction "S2_7") (pintype "passive"))
      (node (ref "U20") (pin "9") (pinfunction "S3_9") (pintype "passive"))
    )
    (net (code "362") (name "Net-(U19-D4)") (class "Default")
      (node (ref "U19") (pin "12") (pinfunction "D4_12") (pintype "passive"))
      (node (ref "U20") (pin "14") (pinfunction "S5_14") (pintype "passive"))
      (node (ref "U20") (pin "16") (pinfunction "S6_16") (pintype "passive"))
      (node (ref "U20") (pin "18") (pinfunction "S7_18") (pintype "passive"))
      (node (ref "U20") (pin "20") (pinfunction "S8_20") (pintype "passive"))
    )
    (net (code "363") (name "Net-(U19-D5)") (class "Default")
      (node (ref "U19") (pin "13") (pinfunction "D5_13") (pintype "passive"))
      (node (ref "U21") (pin "11") (pinfunction "S4_11") (pintype "passive"))
      (node (ref "U21") (pin "5") (pinfunction "S1_5") (pintype "passive"))
      (node (ref "U21") (pin "7") (pinfunction "S2_7") (pintype "passive"))
      (node (ref "U21") (pin "9") (pinfunction "S3_9") (pintype "passive"))
    )
    (net (code "364") (name "Net-(U19-D6)") (class "Default")
      (node (ref "U19") (pin "15") (pinfunction "D6_15") (pintype "passive"))
      (node (ref "U21") (pin "14") (pinfunction "S5_14") (pintype "passive"))
      (node (ref "U21") (pin "16") (pinfunction "S6_16") (pintype "passive"))
      (node (ref "U21") (pin "18") (pinfunction "S7_18") (pintype "passive"))
      (node (ref "U21") (pin "20") (pinfunction "S8_20") (pintype "passive"))
    )
    (net (code "365") (name "Net-(U19-D7)") (class "Default")
      (node (ref "U19") (pin "17") (pinfunction "D7_17") (pintype "passive"))
      (node (ref "U22") (pin "11") (pinfunction "S4_11") (pintype "passive"))
      (node (ref "U22") (pin "5") (pinfunction "S1_5") (pintype "passive"))
      (node (ref "U22") (pin "7") (pinfunction "S2_7") (pintype "passive"))
      (node (ref "U22") (pin "9") (pinfunction "S3_9") (pintype "passive"))
    )
    (net (code "366") (name "Net-(U19-D8)") (class "Default")
      (node (ref "U19") (pin "19") (pinfunction "D8_19") (pintype "passive"))
      (node (ref "U22") (pin "14") (pinfunction "S5_14") (pintype "passive"))
      (node (ref "U22") (pin "16") (pinfunction "S6_16") (pintype "passive"))
      (node (ref "U22") (pin "18") (pinfunction "S7_18") (pintype "passive"))
      (node (ref "U22") (pin "20") (pinfunction "S8_20") (pintype "passive"))
    )
    (net (code "367") (name "Net-(U20-DOUT)") (class "Default")
      (node (ref "R46") (pin "2") (pinfunction "2_2") (pintype "passive"))
      (node (ref "U20") (pin "22") (pinfunction "DOUT_22") (pintype "passive"))
      (node (ref "U21") (pin "3") (pinfunction "DIN_3") (pintype "passive"))
    )
    (net (code "368") (name "Net-(U21-DOUT)") (class "Default")
      (node (ref "R47") (pin "2") (pinfunction "2_2") (pintype "passive"))
      (node (ref "U21") (pin "22") (pinfunction "DOUT_22") (pintype "passive"))
      (node (ref "U22") (pin "3") (pinfunction "DIN_3") (pintype "passive"))
    )
    (net (code "369") (name "Net-(U22-DOUT)") (class "Default")
      (node (ref "R65") (pin "1") (pinfunction "1_1") (pintype "passive"))
      (node (ref "U22") (pin "22") (pinfunction "DOUT_22") (pintype "passive"))
    )
    (net (code "370") (name "Net-(U25-DIN)") (class "Default")
      (node (ref "R69") (pin "2") (pinfunction "2_2") (pintype "passive"))
      (node (ref "U25") (pin "3") (pinfunction "DIN_3") (pintype "passive"))
      (node (ref "U26") (pin "22") (pinfunction "DOUT_22") (pintype "passive"))
    )
    (net (code "371") (name "Net-(U25-DOUT)") (class "Default")
      (node (ref "R66") (pin "2") (pinfunction "2_2") (pintype "passive"))
      (node (ref "U25") (pin "22") (pinfunction "DOUT_22") (pintype "passive"))
      (node (ref "U27") (pin "3") (pinfunction "DIN_3") (pintype "passive"))
    )
    (net (code "372") (name "Net-(U25-S1)") (class "Default")
      (node (ref "U25") (pin "11") (pinfunction "S4_11") (pintype "passive"))
      (node (ref "U25") (pin "5") (pinfunction "S1_5") (pintype "passive"))
      (node (ref "U25") (pin "7") (pinfunction "S2_7") (pintype "passive"))
      (node (ref "U25") (pin "9") (pinfunction "S3_9") (pintype "passive"))
      (node (ref "U26") (pin "6") (pinfunction "D1_6") (pintype "passive"))
    )
    (net (code "373") (name "Net-(U25-S5)") (class "Default")
      (node (ref "U25") (pin "14") (pinfunction "S5_14") (pintype "passive"))
      (node (ref "U25") (pin "16") (pinfunction "S6_16") (pintype "passive"))
      (node (ref "U25") (pin "18") (pinfunction "S7_18") (pintype "passive"))
      (node (ref "U25") (pin "20") (pinfunction "S8_20") (pintype "passive"))
      (node (ref "U26") (pin "8") (pinfunction "D2_8") (pintype "passive"))
    )
    (net (code "374") (name "Net-(U26-D3)") (class "Default")
      (node (ref "U26") (pin "10") (pinfunction "D3_10") (pintype "passive"))
      (node (ref "U27") (pin "11") (pinfunction "S4_11") (pintype "passive"))
      (node (ref "U27") (pin "5") (pinfunction "S1_5") (pintype "passive"))
      (node (ref "U27") (pin "7") (pinfunction "S2_7") (pintype "passive"))
      (node (ref "U27") (pin "9") (pinfunction "S3_9") (pintype "passive"))
    )
    (net (code "375") (name "Net-(U26-D4)") (class "Default")
      (node (ref "U26") (pin "12") (pinfunction "D4_12") (pintype "passive"))
      (node (ref "U27") (pin "14") (pinfunction "S5_14") (pintype "passive"))
      (node (ref "U27") (pin "16") (pinfunction "S6_16") (pintype "passive"))
      (node (ref "U27") (pin "18") (pinfunction "S7_18") (pintype "passive"))
      (node (ref "U27") (pin "20") (pinfunction "S8_20") (pintype "passive"))
    )
    (net (code "376") (name "Net-(U26-D5)") (class "Default")
      (node (ref "U26") (pin "13") (pinfunction "D5_13") (pintype "passive"))
      (node (ref "U28") (pin "11") (pinfunction "S4_11") (pintype "passive"))
      (node (ref "U28") (pin "5") (pinfunction "S1_5") (pintype "passive"))
      (node (ref "U28") (pin "7") (pinfunction "S2_7") (pintype "passive"))
      (node (ref "U28") (pin "9") (pinfunction "S3_9") (pintype "passive"))
    )
    (net (code "377") (name "Net-(U26-D6)") (class "Default")
      (node (ref "U26") (pin "15") (pinfunction "D6_15") (pintype "passive"))
      (node (ref "U28") (pin "14") (pinfunction "S5_14") (pintype "passive"))
      (node (ref "U28") (pin "16") (pinfunction "S6_16") (pintype "passive"))
      (node (ref "U28") (pin "18") (pinfunction "S7_18") (pintype "passive"))
      (node (ref "U28") (pin "20") (pinfunction "S8_20") (pintype "passive"))
    )
    (net (code "378") (name "Net-(U26-D7)") (class "Default")
      (node (ref "U26") (pin "17") (pinfunction "D7_17") (pintype "passive"))
      (node (ref "U29") (pin "11") (pinfunction "S4_11") (pintype "passive"))
      (node (ref "U29") (pin "5") (pinfunction "S1_5") (pintype "passive"))
      (node (ref "U29") (pin "7") (pinfunction "S2_7") (pintype "passive"))
      (node (ref "U29") (pin "9") (pinfunction "S3_9") (pintype "passive"))
    )
    (net (code "379") (name "Net-(U26-D8)") (class "Default")
      (node (ref "U26") (pin "19") (pinfunction "D8_19") (pintype "passive"))
      (node (ref "U29") (pin "14") (pinfunction "S5_14") (pintype "passive"))
      (node (ref "U29") (pin "16") (pinfunction "S6_16") (pintype "passive"))
      (node (ref "U29") (pin "18") (pinfunction "S7_18") (pintype "passive"))
      (node (ref "U29") (pin "20") (pinfunction "S8_20") (pintype "passive"))
    )
    (net (code "380") (name "Net-(U27-DOUT)") (class "Default")
      (node (ref "R67") (pin "2") (pinfunction "2_2") (pintype "passive"))
      (node (ref "U27") (pin "22") (pinfunction "DOUT_22") (pintype "passive"))
      (node (ref "U28") (pin "3") (pinfunction "DIN_3") (pintype "passive"))
    )
    (net (code "381") (name "Net-(U28-DOUT)") (class "Default")
      (node (ref "R68") (pin "2") (pinfunction "2_2") (pintype "passive"))
      (node (ref "U28") (pin "22") (pinfunction "DOUT_22") (pintype "passive"))
      (node (ref "U29") (pin "3") (pinfunction "DIN_3") (pintype "passive"))
    )
    (net (code "382") (name "Net-(U29-DOUT)") (class "Default")
      (node (ref "R86") (pin "1") (pinfunction "1_1") (pintype "passive"))
      (node (ref "U29") (pin "22") (pinfunction "DOUT_22") (pintype "passive"))
    )
    (net (code "383") (name "Net-(U32-DIN)") (class "Default")
      (node (ref "R90") (pin "2") (pinfunction "2_2") (pintype "passive"))
      (node (ref "U32") (pin "3") (pinfunction "DIN_3") (pintype "passive"))
      (node (ref "U33") (pin "22") (pinfunction "DOUT_22") (pintype "passive"))
    )
    (net (code "384") (name "Net-(U32-DOUT)") (class "Default")
      (node (ref "R87") (pin "2") (pinfunction "2_2") (pintype "passive"))
      (node (ref "U32") (pin "22") (pinfunction "DOUT_22") (pintype "passive"))
      (node (ref "U34") (pin "3") (pinfunction "DIN_3") (pintype "passive"))
    )
    (net (code "385") (name "Net-(U32-S1)") (class "Default")
      (node (ref "U32") (pin "11") (pinfunction "S4_11") (pintype "passive"))
      (node (ref "U32") (pin "5") (pinfunction "S1_5") (pintype "passive"))
      (node (ref "U32") (pin "7") (pinfunction "S2_7") (pintype "passive"))
      (node (ref "U32") (pin "9") (pinfunction "S3_9") (pintype "passive"))
      (node (ref "U33") (pin "6") (pinfunction "D1_6") (pintype "passive"))
    )
    (net (code "386") (name "Net-(U32-S5)") (class "Default")
      (node (ref "U32") (pin "14") (pinfunction "S5_14") (pintype "passive"))
      (node (ref "U32") (pin "16") (pinfunction "S6_16") (pintype "passive"))
      (node (ref "U32") (pin "18") (pinfunction "S7_18") (pintype "passive"))
      (node (ref "U32") (pin "20") (pinfunction "S8_20") (pintype "passive"))
      (node (ref "U33") (pin "8") (pinfunction "D2_8") (pintype "passive"))
    )
    (net (code "387") (name "Net-(U33-D3)") (class "Default")
      (node (ref "U33") (pin "10") (pinfunction "D3_10") (pintype "passive"))
      (node (ref "U34") (pin "11") (pinfunction "S4_11") (pintype "passive"))
      (node (ref "U34") (pin "5") (pinfunction "S1_5") (pintype "passive"))
      (node (ref "U34") (pin "7") (pinfunction "S2_7") (pintype "passive"))
      (node (ref "U34") (pin "9") (pinfunction "S3_9") (pintype "passive"))
    )
    (net (code "388") (name "Net-(U33-D4)") (class "Default")
      (node (ref "U33") (pin "12") (pinfunction "D4_12") (pintype "passive"))
      (node (ref "U34") (pin "14") (pinfunction "S5_14") (pintype "passive"))
      (node (ref "U34") (pin "16") (pinfunction "S6_16") (pintype "passive"))
      (node (ref "U34") (pin "18") (pinfunction "S7_18") (pintype "passive"))
      (node (ref "U34") (pin "20") (pinfunction "S8_20") (pintype "passive"))
    )
    (net (code "389") (name "Net-(U33-D5)") (class "Default")
      (node (ref "U33") (pin "13") (pinfunction "D5_13") (pintype "passive"))
      (node (ref "U35") (pin "11") (pinfunction "S4_11") (pintype "passive"))
      (node (ref "U35") (pin "5") (pinfunction "S1_5") (pintype "passive"))
      (node (ref "U35") (pin "7") (pinfunction "S2_7") (pintype "passive"))
      (node (ref "U35") (pin "9") (pinfunction "S3_9") (pintype "passive"))
    )
    (net (code "390") (name "Net-(U33-D6)") (class "Default")
      (node (ref "U33") (pin "15") (pinfunction "D6_15") (pintype "passive"))
      (node (ref "U35") (pin "14") (pinfunction "S5_14") (pintype "passive"))
      (node (ref "U35") (pin "16") (pinfunction "S6_16") (pintype "passive"))
      (node (ref "U35") (pin "18") (pinfunction "S7_18") (pintype "passive"))
      (node (ref "U35") (pin "20") (pinfunction "S8_20") (pintype "passive"))
    )
    (net (code "391") (name "Net-(U33-D7)") (class "Default")
      (node (ref "U33") (pin "17") (pinfunction "D7_17") (pintype "passive"))
      (node (ref "U36") (pin "11") (pinfunction "S4_11") (pintype "passive"))
      (node (ref "U36") (pin "5") (pinfunction "S1_5") (pintype "passive"))
      (node (ref "U36") (pin "7") (pinfunction "S2_7") (pintype "passive"))
      (node (ref "U36") (pin "9") (pinfunction "S3_9") (pintype "passive"))
    )
    (net (code "392") (name "Net-(U33-D8)") (class "Default")
      (node (ref "U33") (pin "19") (pinfunction "D8_19") (pintype "passive"))
      (node (ref "U36") (pin "14") (pinfunction "S5_14") (pintype "passive"))
      (node (ref "U36") (pin "16") (pinfunction "S6_16") (pintype "passive"))
      (node (ref "U36") (pin "18") (pinfunction "S7_18") (pintype "passive"))
      (node (ref "U36") (pin "20") (pinfunction "S8_20") (pintype "passive"))
    )
    (net (code "393") (name "Net-(U34-DOUT)") (class "Default")
      (node (ref "R88") (pin "2") (pinfunction "2_2") (pintype "passive"))
      (node (ref "U34") (pin "22") (pinfunction "DOUT_22") (pintype "passive"))
      (node (ref "U35") (pin "3") (pinfunction "DIN_3") (pintype "passive"))
    )
    (net (code "394") (name "Net-(U35-DOUT)") (class "Default")
      (node (ref "R89") (pin "2") (pinfunction "2_2") (pintype "passive"))
      (node (ref "U35") (pin "22") (pinfunction "DOUT_22") (pintype "passive"))
      (node (ref "U36") (pin "3") (pinfunction "DIN_3") (pintype "passive"))
    )
    (net (code "395") (name "Net-(U36-DOUT)") (class "Default")
      (node (ref "R107") (pin "1") (pinfunction "1_1") (pintype "passive"))
      (node (ref "U36") (pin "22") (pinfunction "DOUT_22") (pintype "passive"))
    )
    (net (code "396") (name "Net-(U39-DIN)") (class "Default")
      (node (ref "R111") (pin "2") (pinfunction "2_2") (pintype "passive"))
      (node (ref "U39") (pin "3") (pinfunction "DIN_3") (pintype "passive"))
      (node (ref "U40") (pin "22") (pinfunction "DOUT_22") (pintype "passive"))
    )
    (net (code "397") (name "Net-(U39-DOUT)") (class "Default")
      (node (ref "R108") (pin "2") (pinfunction "2_2") (pintype "passive"))
      (node (ref "U39") (pin "22") (pinfunction "DOUT_22") (pintype "passive"))
      (node (ref "U41") (pin "3") (pinfunction "DIN_3") (pintype "passive"))
    )
    (net (code "398") (name "Net-(U39-S1)") (class "Default")
      (node (ref "U39") (pin "11") (pinfunction "S4_11") (pintype "passive"))
      (node (ref "U39") (pin "5") (pinfunction "S1_5") (pintype "passive"))
      (node (ref "U39") (pin "7") (pinfunction "S2_7") (pintype "passive"))
      (node (ref "U39") (pin "9") (pinfunction "S3_9") (pintype "passive"))
      (node (ref "U40") (pin "6") (pinfunction "D1_6") (pintype "passive"))
    )
    (net (code "399") (name "Net-(U39-S5)") (class "Default")
      (node (ref "U39") (pin "14") (pinfunction "S5_14") (pintype "passive"))
      (node (ref "U39") (pin "16") (pinfunction "S6_16") (pintype "passive"))
      (node (ref "U39") (pin "18") (pinfunction "S7_18") (pintype "passive"))
      (node (ref "U39") (pin "20") (pinfunction "S8_20") (pintype "passive"))
      (node (ref "U40") (pin "8") (pinfunction "D2_8") (pintype "passive"))
    )
    (net (code "400") (name "Net-(U40-D3)") (class "Default")
      (node (ref "U40") (pin "10") (pinfunction "D3_10") (pintype "passive"))
      (node (ref "U41") (pin "11") (pinfunction "S4_11") (pintype "passive"))
      (node (ref "U41") (pin "5") (pinfunction "S1_5") (pintype "passive"))
      (node (ref "U41") (pin "7") (pinfunction "S2_7") (pintype "passive"))
      (node (ref "U41") (pin "9") (pinfunction "S3_9") (pintype "passive"))
    )
    (net (code "401") (name "Net-(U40-D4)") (class "Default")
      (node (ref "U40") (pin "12") (pinfunction "D4_12") (pintype "passive"))
      (node (ref "U41") (pin "14") (pinfunction "S5_14") (pintype "passive"))
      (node (ref "U41") (pin "16") (pinfunction "S6_16") (pintype "passive"))
      (node (ref "U41") (pin "18") (pinfunction "S7_18") (pintype "passive"))
      (node (ref "U41") (pin "20") (pinfunction "S8_20") (pintype "passive"))
    )
    (net (code "402") (name "Net-(U40-D5)") (class "Default")
      (node (ref "U40") (pin "13") (pinfunction "D5_13") (pintype "passive"))
      (node (ref "U42") (pin "11") (pinfunction "S4_11") (pintype "passive"))
      (node (ref "U42") (pin "5") (pinfunction "S1_5") (pintype "passive"))
      (node (ref "U42") (pin "7") (pinfunction "S2_7") (pintype "passive"))
      (node (ref "U42") (pin "9") (pinfunction "S3_9") (pintype "passive"))
    )
    (net (code "403") (name "Net-(U40-D6)") (class "Default")
      (node (ref "U40") (pin "15") (pinfunction "D6_15") (pintype "passive"))
      (node (ref "U42") (pin "14") (pinfunction "S5_14") (pintype "passive"))
      (node (ref "U42") (pin "16") (pinfunction "S6_16") (pintype "passive"))
      (node (ref "U42") (pin "18") (pinfunction "S7_18") (pintype "passive"))
      (node (ref "U42") (pin "20") (pinfunction "S8_20") (pintype "passive"))
    )
    (net (code "404") (name "Net-(U40-D7)") (class "Default")
      (node (ref "U40") (pin "17") (pinfunction "D7_17") (pintype "passive"))
      (node (ref "U43") (pin "11") (pinfunction "S4_11") (pintype "passive"))
      (node (ref "U43") (pin "5") (pinfunction "S1_5") (pintype "passive"))
      (node (ref "U43") (pin "7") (pinfunction "S2_7") (pintype "passive"))
      (node (ref "U43") (pin "9") (pinfunction "S3_9") (pintype "passive"))
    )
    (net (code "405") (name "Net-(U40-D8)") (class "Default")
      (node (ref "U40") (pin "19") (pinfunction "D8_19") (pintype "passive"))
      (node (ref "U43") (pin "14") (pinfunction "S5_14") (pintype "passive"))
      (node (ref "U43") (pin "16") (pinfunction "S6_16") (pintype "passive"))
      (node (ref "U43") (pin "18") (pinfunction "S7_18") (pintype "passive"))
      (node (ref "U43") (pin "20") (pinfunction "S8_20") (pintype "passive"))
    )
    (net (code "406") (name "Net-(U41-DOUT)") (class "Default")
      (node (ref "R109") (pin "2") (pinfunction "2_2") (pintype "passive"))
      (node (ref "U41") (pin "22") (pinfunction "DOUT_22") (pintype "passive"))
      (node (ref "U42") (pin "3") (pinfunction "DIN_3") (pintype "passive"))
    )
    (net (code "407") (name "Net-(U42-DOUT)") (class "Default")
      (node (ref "R110") (pin "2") (pinfunction "2_2") (pintype "passive"))
      (node (ref "U42") (pin "22") (pinfunction "DOUT_22") (pintype "passive"))
      (node (ref "U43") (pin "3") (pinfunction "DIN_3") (pintype "passive"))
    )
    (net (code "408") (name "Net-(U43-DOUT)") (class "Default")
      (node (ref "R128") (pin "1") (pinfunction "1_1") (pintype "passive"))
      (node (ref "U43") (pin "22") (pinfunction "DOUT_22") (pintype "passive"))
    )
    (net (code "409") (name "Net-(U54-D2)") (class "Default")
      (node (ref "U54") (pin "10") (pinfunction "D3_10") (pintype "passive"))
      (node (ref "U54") (pin "12") (pinfunction "D4_12") (pintype "passive"))
      (node (ref "U54") (pin "13") (pinfunction "D5_13") (pintype "passive"))
      (node (ref "U54") (pin "15") (pinfunction "D6_15") (pintype "passive"))
      (node (ref "U54") (pin "17") (pinfunction "D7_17") (pintype "passive"))
      (node (ref "U54") (pin "8") (pinfunction "D2_8") (pintype "passive"))
    )
    (net (code "410") (name "Net-(U56-EN)") (class "Default")
      (node (ref "C24") (pin "2") (pinfunction "2_2") (pintype "passive"))
      (node (ref "R164") (pin "2") (pinfunction "2_2") (pintype "passive"))
      (node (ref "U56") (pin "19") (pinfunction "VREF_B_19") (pintype "passive"))
      (node (ref "U56") (pin "20") (pinfunction "EN_20") (pintype "passive"))
    )
    (net (code "411") (name "Net-(U58-D1)") (class "Default")
      (node (ref "R131") (pin "2") (pinfunction "2_2") (pintype "passive"))
      (node (ref "U58") (pin "10") (pinfunction "D3_10") (pintype "passive"))
      (node (ref "U58") (pin "12") (pinfunction "D4_12") (pintype "passive"))
      (node (ref "U58") (pin "13") (pinfunction "D5_13") (pintype "passive"))
      (node (ref "U58") (pin "15") (pinfunction "D6_15") (pintype "passive"))
      (node (ref "U58") (pin "6") (pinfunction "D1_6") (pintype "passive"))
      (node (ref "U58") (pin "8") (pinfunction "D2_8") (pintype "passive"))
    )
    (net (code "412") (name "VDD") (class "Default")
      (node (ref "C10") (pin "1") (pinfunction "1_1") (pintype "passive"))
      (node (ref "C11") (pin "1") (pinfunction "1_1") (pintype "passive"))
      (node (ref "C12") (pin "1") (pinfunction "1_1") (pintype "passive"))
      (node (ref "C13") (pin "1") (pinfunction "1_1") (pintype "passive"))
      (node (ref "C14") (pin "1") (pinfunction "1_1") (pintype "passive"))
      (node (ref "C15") (pin "1") (pinfunction "1_1") (pintype "passive"))
      (node (ref "C16") (pin "1") (pinfunction "1_1") (pintype "passive"))
      (node (ref "C17") (pin "1") (pinfunction "1_1") (pintype "passive"))
      (node (ref "C26") (pin "1") (pinfunction "1_1") (pintype "passive"))
      (node (ref "C29") (pin "1") (pinfunction "1_1") (pintype "passive"))
      (node (ref "C30") (pin "1") (pinfunction "1_1") (pintype "passive"))
      (node (ref "C35") (pin "1") (pinfunction "1_1") (pintype "passive"))
      (node (ref "C36") (pin "1") (pinfunction "1_1") (pintype "passive"))
      (node (ref "C41") (pin "1") (pinfunction "1_1") (pintype "passive"))
      (node (ref "C42") (pin "1") (pinfunction "1_1") (pintype "passive"))
      (node (ref "C47") (pin "1") (pinfunction "1_1") (pintype "passive"))
      (node (ref "C48") (pin "1") (pinfunction "1_1") (pintype "passive"))
      (node (ref "C53") (pin "1") (pinfunction "1_1") (pintype "passive"))
      (node (ref "C54") (pin "1") (pinfunction "1_1") (pintype "passive"))
      (node (ref "C6") (pin "1") (pinfunction "1_1") (pintype "passive"))
      (node (ref "C8") (pin "1") (pinfunction "1_1") (pintype "passive"))
      (node (ref "C9") (pin "1") (pinfunction "1_1") (pintype "passive"))
      (node (ref "JP1") (pin "2") (pinfunction "2_2") (pintype "passive"))
      (node (ref "R100") (pin "1") (pinfunction "1_1") (pintype "passive"))
      (node (ref "R101") (pin "1") (pinfunction "1_1") (pintype "passive"))
      (node (ref "R102") (pin "1") (pinfunction "1_1") (pintype "passive"))
      (node (ref "R103") (pin "1") (pinfunction "1_1") (pintype "passive"))
      (node (ref "R104") (pin "1") (pinfunction "1_1") (pintype "passive"))
      (node (ref "R105") (pin "1") (pinfunction "1_1") (pintype "passive"))
      (node (ref "R106") (pin "1") (pinfunction "1_1") (pintype "passive"))
      (node (ref "R112") (pin "1") (pinfunction "1_1") (pintype "passive"))
      (node (ref "R113") (pin "1") (pinfunction "1_1") (pintype "passive"))
      (node (ref "R114") (pin "1") (pinfunction "1_1") (pintype "passive"))
      (node (ref "R115") (pin "1") (pinfunction "1_1") (pintype "passive"))
      (node (ref "R116") (pin "1") (pinfunction "1_1") (pintype "passive"))
      (node (ref "R117") (pin "1") (pinfunction "1_1") (pintype "passive"))
      (node (ref "R118") (pin "1") (pinfunction "1_1") (pintype "passive"))
      (node (ref "R119") (pin "1") (pinfunction "1_1") (pintype "passive"))
      (node (ref "R12") (pin "1") (pinfunction "1_1") (pintype "passive"))
      (node (ref "R120") (pin "1") (pinfunction "1_1") (pintype "passive"))
      (node (ref "R121") (pin "1") (pinfunction "1_1") (pintype "passive"))
      (node (ref "R122") (pin "1") (pinfunction "1_1") (pintype "passive"))
      (node (ref "R123") (pin "1") (pinfunction "1_1") (pintype "passive"))
      (node (ref "R124") (pin "1") (pinfunction "1_1") (pintype "passive"))
      (node (ref "R125") (pin "1") (pinfunction "1_1") (pintype "passive"))
      (node (ref "R126") (pin "1") (pinfunction "1_1") (pintype "passive"))
      (node (ref "R127") (pin "1") (pinfunction "1_1") (pintype "passive"))
      (node (ref "R13") (pin "1") (pinfunction "1_1") (pintype "passive"))
      (node (ref "R133") (pin "1") (pinfunction "1_1") (pintype "passive"))
      (node (ref "R136") (pin "1") (pinfunction "1_1") (pintype "passive"))
      (node (ref "R137") (pin "1") (pinfunction "1_1") (pintype "passive"))
      (node (ref "R139") (pin "1") (pinfunction "1_1") (pintype "passive"))
      (node (ref "R14") (pin "1") (pinfunction "1_1") (pintype "passive"))
      (node (ref "R141") (pin "1") (pinfunction "1_1") (pintype "passive"))
      (node (ref "R144") (pin "1") (pinfunction "1_1") (pintype "passive"))
      (node (ref "R145") (pin "1") (pinfunction "1_1") (pintype "passive"))
      (node (ref "R15") (pin "1") (pinfunction "1_1") (pintype "passive"))
      (node (ref "R158") (pin "1") (pinfunction "1_1") (pintype "passive"))
      (node (ref "R159") (pin "1") (pinfunction "1_1") (pintype "passive"))
      (node (ref "R16") (pin "1") (pinfunction "1_1") (pintype "passive"))
      (node (ref "R160") (pin "1") (pinfunction "1_1") (pintype "passive"))
      (node (ref "R17") (pin "1") (pinfunction "1_1") (pintype "passive"))
      (node (ref "R170") (pin "1") (pinfunction "1_1") (pintype "passive"))
      (node (ref "R171") (pin "1") (pinfunction "1_1") (pintype "passive"))
      (node (ref "R172") (pin "1") (pinfunction "1_1") (pintype "passive"))
      (node (ref "R173") (pin "1") (pinfunction "1_1") (pintype "passive"))
      (node (ref "R174") (pin "1") (pinfunction "1_1") (pintype "passive"))
      (node (ref "R18") (pin "1") (pinfunction "1_1") (pintype "passive"))
      (node (ref "R19") (pin "1") (pinfunction "1_1") (pintype "passive"))
      (node (ref "R20") (pin "1") (pinfunction "1_1") (pintype "passive"))
      (node (ref "R21") (pin "1") (pinfunction "1_1") (pintype "passive"))
      (node (ref "R22") (pin "1") (pinfunction "1_1") (pintype "passive"))
      (node (ref "R23") (pin "1") (pinfunction "1_1") (pintype "passive"))
      (node (ref "R24") (pin "1") (pinfunction "1_1") (pintype "passive"))
      (node (ref "R25") (pin "1") (pinfunction "1_1") (pintype "passive"))
      (node (ref "R26") (pin "1") (pinfunction "1_1") (pintype "passive"))
      (node (ref "R27") (pin "1") (pinfunction "1_1") (pintype "passive"))
      (node (ref "R28") (pin "1") (pinfunction "1_1") (pintype "passive"))
      (node (ref "R29") (pin "1") (pinfunction "1_1") (pintype "passive"))
      (node (ref "R30") (pin "1") (pinfunction "1_1") (pintype "passive"))
      (node (ref "R31") (pin "1") (pinfunction "1_1") (pintype "passive"))
      (node (ref "R32") (pin "1") (pinfunction "1_1") (pintype "passive"))
      (node (ref "R33") (pin "1") (pinfunction "1_1") (pintype "passive"))
      (node (ref "R34") (pin "1") (pinfunction "1_1") (pintype "passive"))
      (node (ref "R35") (pin "1") (pinfunction "1_1") (pintype "passive"))
      (node (ref "R36") (pin "1") (pinfunction "1_1") (pintype "passive"))
      (node (ref "R37") (pin "1") (pinfunction "1_1") (pintype "passive"))
      (node (ref "R38") (pin "1") (pinfunction "1_1") (pintype "passive"))
      (node (ref "R39") (pin "1") (pinfunction "1_1") (pintype "passive"))
      (node (ref "R40") (pin "1") (pinfunction "1_1") (pintype "passive"))
      (node (ref "R41") (pin "1") (pinfunction "1_1") (pintype "passive"))
      (node (ref "R42") (pin "1") (pinfunction "1_1") (pintype "passive"))
      (node (ref "R43") (pin "1") (pinfunction "1_1") (pintype "passive"))
      (node (ref "R49") (pin "1") (pinfunction "1_1") (pintype "passive"))
      (node (ref "R50") (pin "1") (pinfunction "1_1") (pintype "passive"))
      (node (ref "R51") (pin "1") (pinfunction "1_1") (pintype "passive"))
      (node (ref "R52") (pin "1") (pinfunction "1_1") (pintype "passive"))
      (node (ref "R53") (pin "1") (pinfunction "1_1") (pintype "passive"))
      (node (ref "R54") (pin "1") (pinfunction "1_1") (pintype "passive"))
      (node (ref "R55") (pin "1") (pinfunction "1_1") (pintype "passive"))
      (node (ref "R56") (pin "1") (pinfunction "1_1") (pintype "passive"))
      (node (ref "R57") (pin "1") (pinfunction "1_1") (pintype "passive"))
      (node (ref "R58") (pin "1") (pinfunction "1_1") (pintype "passive"))
      (node (ref "R59") (pin "1") (pinfunction "1_1") (pintype "passive"))
      (node (ref "R60") (pin "1") (pinfunction "1_1") (pintype "passive"))
      (node (ref "R61") (pin "1") (pinfunction "1_1") (pintype "passive"))
      (node (ref "R62") (pin "1") (pinfunction "1_1") (pintype "passive"))
      (node (ref "R63") (pin "1") (pinfunction "1_1") (pintype "passive"))
      (node (ref "R64") (pin "1") (pinfunction "1_1") (pintype "passive"))
      (node (ref "R70") (pin "1") (pinfunction "1_1") (pintype "passive"))
      (node (ref "R71") (pin "1") (pinfunction "1_1") (pintype "passive"))
      (node (ref "R72") (pin "1") (pinfunction "1_1") (pintype "passive"))
      (node (ref "R73") (pin "1") (pinfunction "1_1") (pintype "passive"))
      (node (ref "R74") (pin "1") (pinfunction "1_1") (pintype "passive"))
      (node (ref "R75") (pin "1") (pinfunction "1_1") (pintype "passive"))
      (node (ref "R76") (pin "1") (pinfunction "1_1") (pintype "passive"))
      (node (ref "R77") (pin "1") (pinfunction "1_1") (pintype "passive"))
      (node (ref "R78") (pin "1") (pinfunction "1_1") (pintype "passive"))
      (node (ref "R79") (pin "1") (pinfunction "1_1") (pintype "passive"))
      (node (ref "R80") (pin "1") (pinfunction "1_1") (pintype "passive"))
      (node (ref "R81") (pin "1") (pinfunction "1_1") (pintype "passive"))
      (node (ref "R82") (pin "1") (pinfunction "1_1") (pintype "passive"))
      (node (ref "R83") (pin "1") (pinfunction "1_1") (pintype "passive"))
      (node (ref "R84") (pin "1") (pinfunction "1_1") (pintype "passive"))
      (node (ref "R85") (pin "1") (pinfunction "1_1") (pintype "passive"))
      (node (ref "R91") (pin "1") (pinfunction "1_1") (pintype "passive"))
      (node (ref "R92") (pin "1") (pinfunction "1_1") (pintype "passive"))
      (node (ref "R93") (pin "1") (pinfunction "1_1") (pintype "passive"))
      (node (ref "R94") (pin "1") (pinfunction "1_1") (pintype "passive"))
      (node (ref "R95") (pin "1") (pinfunction "1_1") (pintype "passive"))
      (node (ref "R96") (pin "1") (pinfunction "1_1") (pintype "passive"))
      (node (ref "R97") (pin "1") (pinfunction "1_1") (pintype "passive"))
      (node (ref "R98") (pin "1") (pinfunction "1_1") (pintype "passive"))
      (node (ref "R99") (pin "1") (pinfunction "1_1") (pintype "passive"))
      (node (ref "SV2") (pin "10") (pinfunction "10_10") (pintype "passive"))
      (node (ref "SV2") (pin "7") (pinfunction "7_7") (pintype "passive"))
      (node (ref "SV2") (pin "8") (pinfunction "8_8") (pintype "passive"))
      (node (ref "SV2") (pin "9") (pinfunction "9_9") (pintype "passive"))
      (node (ref "U13") (pin "20") (pinfunction "VCC_20") (pintype "power_in"))
      (node (ref "U14") (pin "20") (pinfunction "VCC_20") (pintype "power_in"))
      (node (ref "U16") (pin "20") (pinfunction "VCC_20") (pintype "power_in"))
      (node (ref "U17") (pin "20") (pinfunction "VCC_20") (pintype "power_in"))
      (node (ref "U23") (pin "20") (pinfunction "VCC_20") (pintype "power_in"))
      (node (ref "U24") (pin "20") (pinfunction "VCC_20") (pintype "power_in"))
      (node (ref "U30") (pin "20") (pinfunction "VCC_20") (pintype "power_in"))
      (node (ref "U31") (pin "20") (pinfunction "VCC_20") (pintype "power_in"))
      (node (ref "U37") (pin "20") (pinfunction "VCC_20") (pintype "power_in"))
      (node (ref "U38") (pin "20") (pinfunction "VCC_20") (pintype "power_in"))
      (node (ref "U44") (pin "20") (pinfunction "VCC_20") (pintype "power_in"))
      (node (ref "U45") (pin "20") (pinfunction "VCC_20") (pintype "power_in"))
      (node (ref "U46") (pin "1") (pinfunction "VCCA_1") (pintype "power_in"))
      (node (ref "U46") (pin "5") (pinfunction "EN_5") (pintype "input"))
      (node (ref "U46") (pin "8") (pinfunction "VCCB_8") (pintype "power_in"))
      (node (ref "U47") (pin "1") (pinfunction "VCCA_1") (pintype "power_in"))
      (node (ref "U47") (pin "5") (pinfunction "EN_5") (pintype "input"))
      (node (ref "U47") (pin "8") (pinfunction "VCCB_8") (pintype "power_in"))
      (node (ref "U48") (pin "1") (pinfunction "VCCA_1") (pintype "power_in"))
      (node (ref "U48") (pin "5") (pinfunction "EN_5") (pintype "input"))
      (node (ref "U48") (pin "8") (pinfunction "VCCB_8") (pintype "power_in"))
      (node (ref "U49") (pin "1") (pinfunction "VCCA_1") (pintype "power_in"))
      (node (ref "U49") (pin "5") (pinfunction "EN_5") (pintype "input"))
      (node (ref "U49") (pin "8") (pinfunction "VCCB_8") (pintype "power_in"))
      (node (ref "U56") (pin "2") (pinfunction "VREF_A_2") (pintype "passive"))
      (node (ref "VDD") (pin "TP") (pinfunction "TP_TP") (pintype "input"))
      (node (ref "X3") (pin "1") (pinfunction "1_1") (pintype "passive"))
      (node (ref "X3") (pin "1@1") (pinfunction "1_1@1") (pintype "passive"))
    )
    (net (code "413") (name "unconnected-(U$1-GND7-Pad68)") (class "Default")
      (node (ref "U$1") (pin "68") (pinfunction "GND7_68") (pintype "bidirectional"))
    )
    (net (code "414") (name "unconnected-(U$1-P_0.0-Pad37)") (class "Default")
      (node (ref "U$1") (pin "37") (pinfunction "P_0.0_37") (pintype "bidirectional"))
    )
    (net (code "415") (name "unconnected-(U$1-P_0.1-Pad36)") (class "Default")
      (node (ref "U$1") (pin "36") (pinfunction "P_0.1_36") (pintype "bidirectional"))
    )
    (net (code "416") (name "unconnected-(U$1-P_0.2-Pad35)") (class "Default")
      (node (ref "U$1") (pin "35") (pinfunction "P_0.2_35") (pintype "bidirectional"))
    )
    (net (code "417") (name "unconnected-(U$1-P_0.3-Pad34)") (class "Default")
      (node (ref "U$1") (pin "34") (pinfunction "P_0.3_34") (pintype "bidirectional"))
    )
    (net (code "418") (name "unconnected-(U$1-P_0.4-Pad33)") (class "Default")
      (node (ref "U$1") (pin "33") (pinfunction "P_0.4_33") (pintype "bidirectional"))
    )
    (net (code "419") (name "unconnected-(U$1-P_0.5-Pad32)") (class "Default")
      (node (ref "U$1") (pin "32") (pinfunction "P_0.5_32") (pintype "bidirectional"))
    )
    (net (code "420") (name "unconnected-(U$1-P_0.6-Pad31)") (class "Default")
      (node (ref "U$1") (pin "31") (pinfunction "P_0.6_31") (pintype "bidirectional"))
    )
    (net (code "421") (name "unconnected-(U$1-P_0.7-Pad30)") (class "Default")
      (node (ref "U$1") (pin "30") (pinfunction "P_0.7_30") (pintype "bidirectional"))
    )
    (net (code "422") (name "unconnected-(U$1-P_1.0-Pad17)") (class "Default")
      (node (ref "U$1") (pin "17") (pinfunction "P_1.0_17") (pintype "bidirectional"))
    )
    (net (code "423") (name "unconnected-(U$1-P_1.1-Pad18)") (class "Default")
      (node (ref "U$1") (pin "18") (pinfunction "P_1.1_18") (pintype "bidirectional"))
    )
    (net (code "424") (name "unconnected-(U$1-P_1.3-Pad20)") (class "Default")
      (node (ref "U$1") (pin "20") (pinfunction "P_1.3_20") (pintype "bidirectional"))
    )
    (net (code "425") (name "unconnected-(U$1-P_2.0-Pad1)") (class "Default")
      (node (ref "U$1") (pin "1") (pinfunction "P_2.0_1") (pintype "bidirectional"))
    )
    (net (code "426") (name "unconnected-(U$1-P_2.1-Pad2)") (class "Default")
      (node (ref "U$1") (pin "2") (pinfunction "P_2.1_2") (pintype "bidirectional"))
    )
    (net (code "427") (name "unconnected-(U$1-P_2.2-Pad3)") (class "Default")
      (node (ref "U$1") (pin "3") (pinfunction "P_2.2_3") (pintype "bidirectional"))
    )
    (net (code "428") (name "unconnected-(U$1-P_2.3-Pad4)") (class "Default")
      (node (ref "U$1") (pin "4") (pinfunction "P_2.3_4") (pintype "bidirectional"))
    )
    (net (code "429") (name "unconnected-(U$1-P_2.4-Pad5)") (class "Default")
      (node (ref "U$1") (pin "5") (pinfunction "P_2.4_5") (pintype "bidirectional"))
    )
    (net (code "430") (name "unconnected-(U$1-P_2.5-Pad6)") (class "Default")
      (node (ref "U$1") (pin "6") (pinfunction "P_2.5_6") (pintype "bidirectional"))
    )
    (net (code "431") (name "unconnected-(U$1-P_2.6-Pad7)") (class "Default")
      (node (ref "U$1") (pin "7") (pinfunction "P_2.6_7") (pintype "bidirectional"))
    )
    (net (code "432") (name "unconnected-(U$1-P_2.7-Pad8)") (class "Default")
      (node (ref "U$1") (pin "8") (pinfunction "P_2.7_8") (pintype "bidirectional"))
    )
    (net (code "433") (name "unconnected-(U$1-P_3.2-Pad49)") (class "Default")
      (node (ref "U$1") (pin "49") (pinfunction "P_3.2_49") (pintype "bidirectional"))
    )
    (net (code "434") (name "unconnected-(U$1-P_3.5-Pad46)") (class "Default")
      (node (ref "U$1") (pin "46") (pinfunction "P_3.5_46") (pintype "bidirectional"))
    )
    (net (code "435") (name "unconnected-(U$1-P_3.6-Pad45)") (class "Default")
      (node (ref "U$1") (pin "45") (pinfunction "P_3.6_45") (pintype "bidirectional"))
    )
    (net (code "436") (name "unconnected-(U$1-P_3.7-Pad44)") (class "Default")
      (node (ref "U$1") (pin "44") (pinfunction "P_3.7_44") (pintype "bidirectional"))
    )
    (net (code "437") (name "unconnected-(U$1-P_12.0-Pad16)") (class "Default")
      (node (ref "U$1") (pin "16") (pinfunction "P_12.0_16") (pintype "bidirectional"))
    )
    (net (code "438") (name "unconnected-(U$1-P_12.1-Pad15)") (class "Default")
      (node (ref "U$1") (pin "15") (pinfunction "P_12.1_15") (pintype "bidirectional"))
    )
    (net (code "439") (name "unconnected-(U$1-P_12.6-Pad10)") (class "Default")
      (node (ref "U$1") (pin "10") (pinfunction "P_12.6_10") (pintype "bidirectional"))
    )
    (net (code "440") (name "unconnected-(U$1-P_12.7-Pad9)") (class "Default")
      (node (ref "U$1") (pin "9") (pinfunction "P_12.7_9") (pintype "bidirectional"))
    )
    (net (code "441") (name "unconnected-(U$1-P_15.0-Pad43)") (class "Default")
      (node (ref "U$1") (pin "43") (pinfunction "P_15.0_43") (pintype "bidirectional"))
    )
    (net (code "442") (name "unconnected-(U$1-P_15.1-Pad42)") (class "Default")
      (node (ref "U$1") (pin "42") (pinfunction "P_15.1_42") (pintype "bidirectional"))
    )
    (net (code "443") (name "unconnected-(U$1-P_15.2-Pad41)") (class "Default")
      (node (ref "U$1") (pin "41") (pinfunction "P_15.2_41") (pintype "bidirectional"))
    )
    (net (code "444") (name "unconnected-(U$1-P_15.3-Pad40)") (class "Default")
      (node (ref "U$1") (pin "40") (pinfunction "P_15.3_40") (pintype "bidirectional"))
    )
    (net (code "445") (name "unconnected-(U$1-P_15.4-Pad39)") (class "Default")
      (node (ref "U$1") (pin "39") (pinfunction "P_15.4_39") (pintype "bidirectional"))
    )
    (net (code "446") (name "unconnected-(U$1-P_15.5-Pad38)") (class "Default")
      (node (ref "U$1") (pin "38") (pinfunction "P_15.5_38") (pintype "bidirectional"))
    )
    (net (code "447") (name "unconnected-(U$1-RST1-Pad29)") (class "Default")
      (node (ref "U$1") (pin "29") (pinfunction "RST1_29") (pintype "bidirectional"))
    )
    (net (code "448") (name "unconnected-(U$1-RST3-Pad69)") (class "Default")
      (node (ref "U$1") (pin "69") (pinfunction "RST3_69") (pintype "bidirectional"))
    )
    (net (code "449") (name "unconnected-(U$1-SWDCLK2-Pad70)") (class "Default")
      (node (ref "U$1") (pin "70") (pinfunction "SWDCLK2_70") (pintype "bidirectional"))
    )
    (net (code "450") (name "unconnected-(U$1-SWDIO2-Pad71)") (class "Default")
      (node (ref "U$1") (pin "71") (pinfunction "SWDIO2_71") (pintype "bidirectional"))
    )
    (net (code "451") (name "unconnected-(U$1-VTARG2-Pad67)") (class "Default")
      (node (ref "U$1") (pin "67") (pinfunction "VTARG2_67") (pintype "bidirectional"))
    )
    (net (code "452") (name "unconnected-(U47-SDAA-Pad3)") (class "Default")
      (node (ref "U47") (pin "3") (pinfunction "SDAA_3") (pintype "bidirectional"))
    )
    (net (code "453") (name "unconnected-(U47-SDAB-Pad6)") (class "Default")
      (node (ref "U47") (pin "6") (pinfunction "SDAB_6") (pintype "bidirectional"))
    )
    (net (code "454") (name "unconnected-(U54-D8-Pad19)") (class "Default")
      (node (ref "U54") (pin "19") (pinfunction "D8_19") (pintype "passive"))
    )
    (net (code "455") (name "unconnected-(U54-S8-Pad20)") (class "Default")
      (node (ref "U54") (pin "20") (pinfunction "S8_20") (pintype "passive"))
    )
    (net (code "456") (name "unconnected-(U58-D7-Pad17)") (class "Default")
      (node (ref "U58") (pin "17") (pinfunction "D7_17") (pintype "passive"))
    )
    (net (code "457") (name "unconnected-(U58-D8-Pad19)") (class "Default")
      (node (ref "U58") (pin "19") (pinfunction "D8_19") (pintype "passive"))
    )
    (net (code "458") (name "unconnected-(U58-S7-Pad18)") (class "Default")
      (node (ref "U58") (pin "18") (pinfunction "S7_18") (pintype "passive"))
    )
    (net (code "459") (name "unconnected-(U58-S8-Pad20)") (class "Default")
      (node (ref "U58") (pin "20") (pinfunction "S8_20") (pintype "passive"))
    )
  )
)
